# BaseBoard5.net
KiCad netlist of a schematic drawn in EAGLE
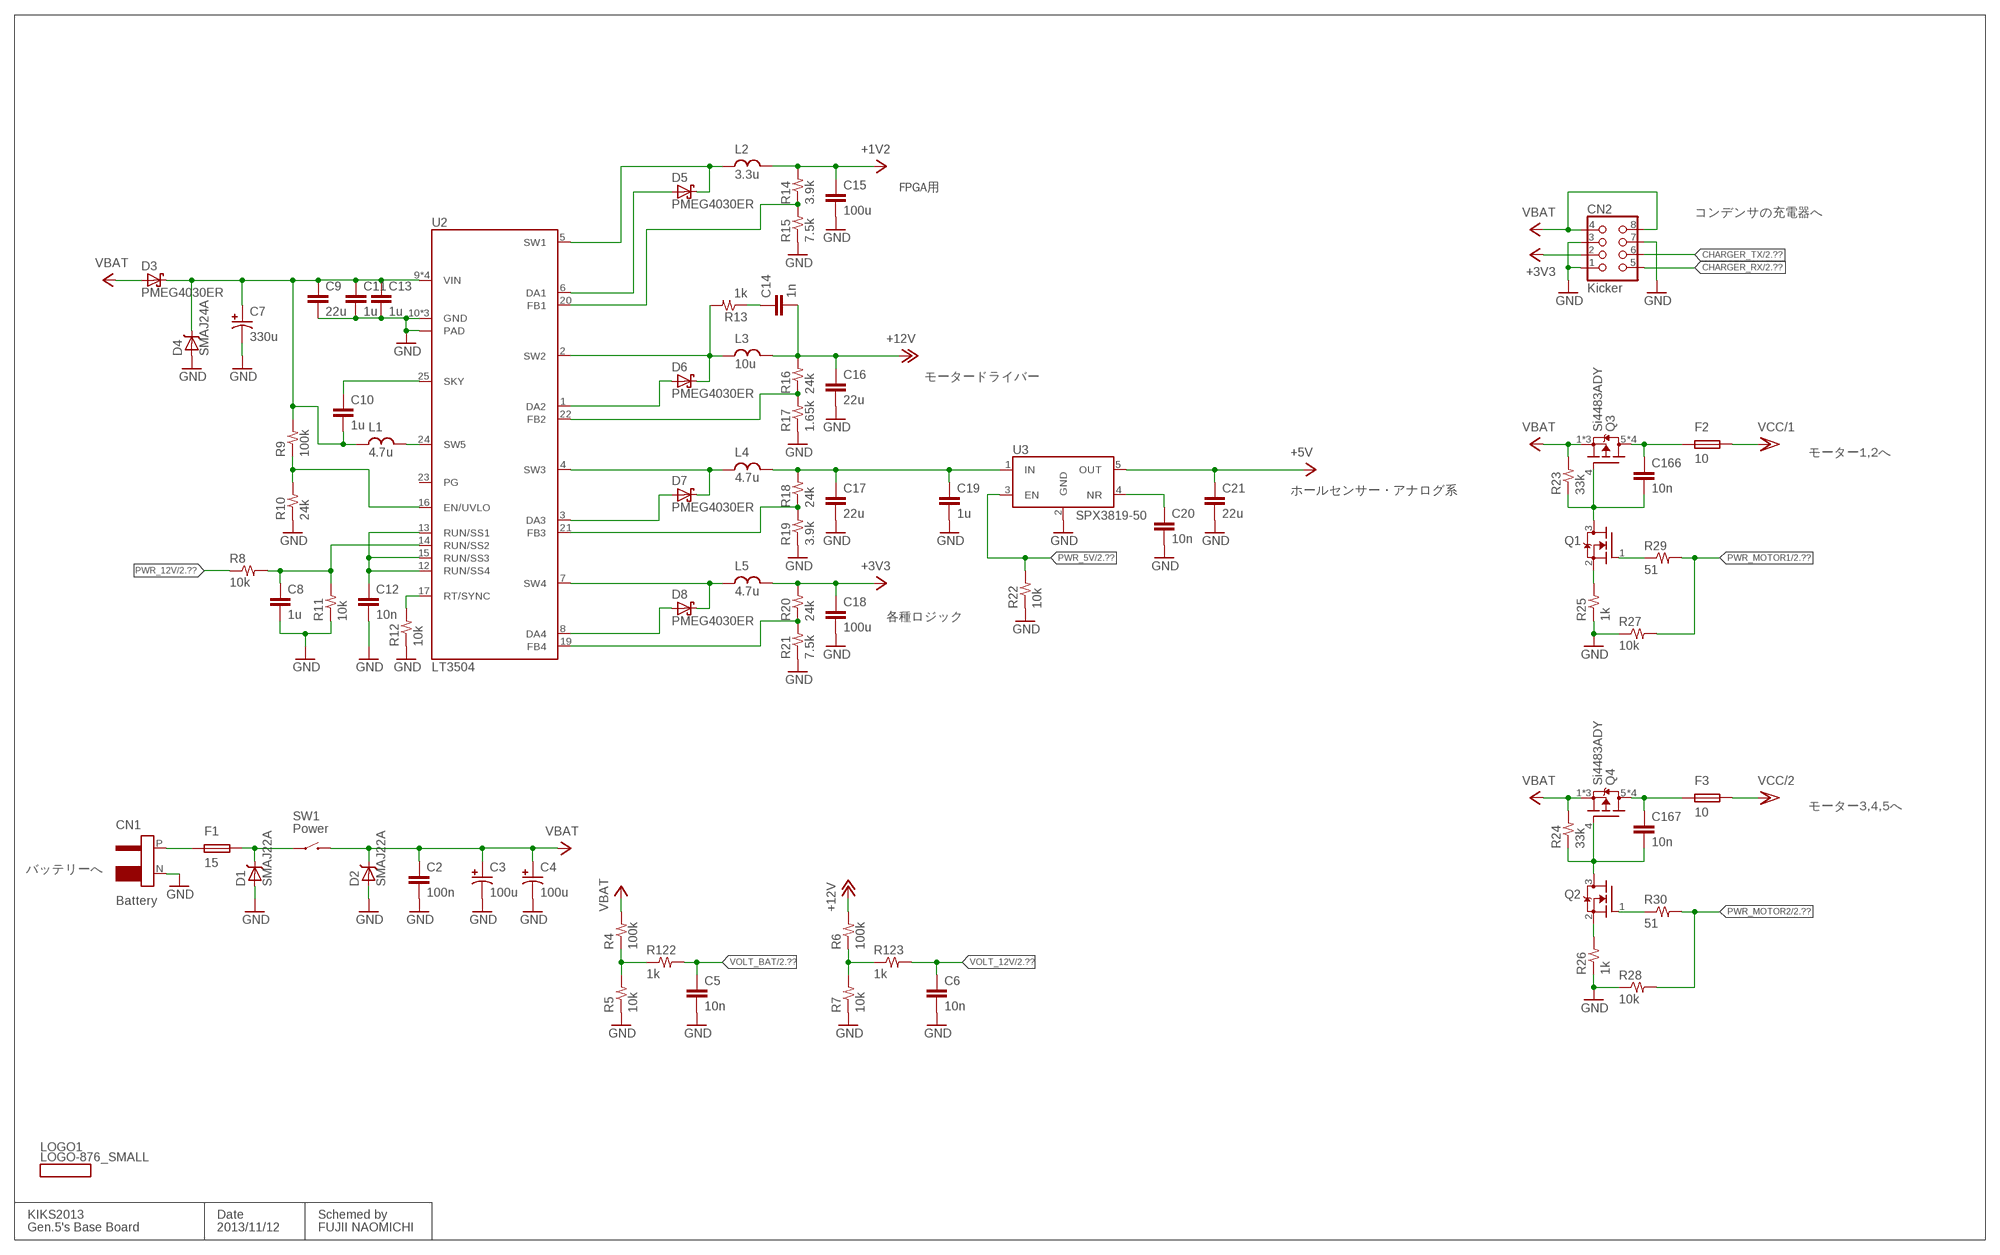
[diagram p0: schematic, sheet 1]
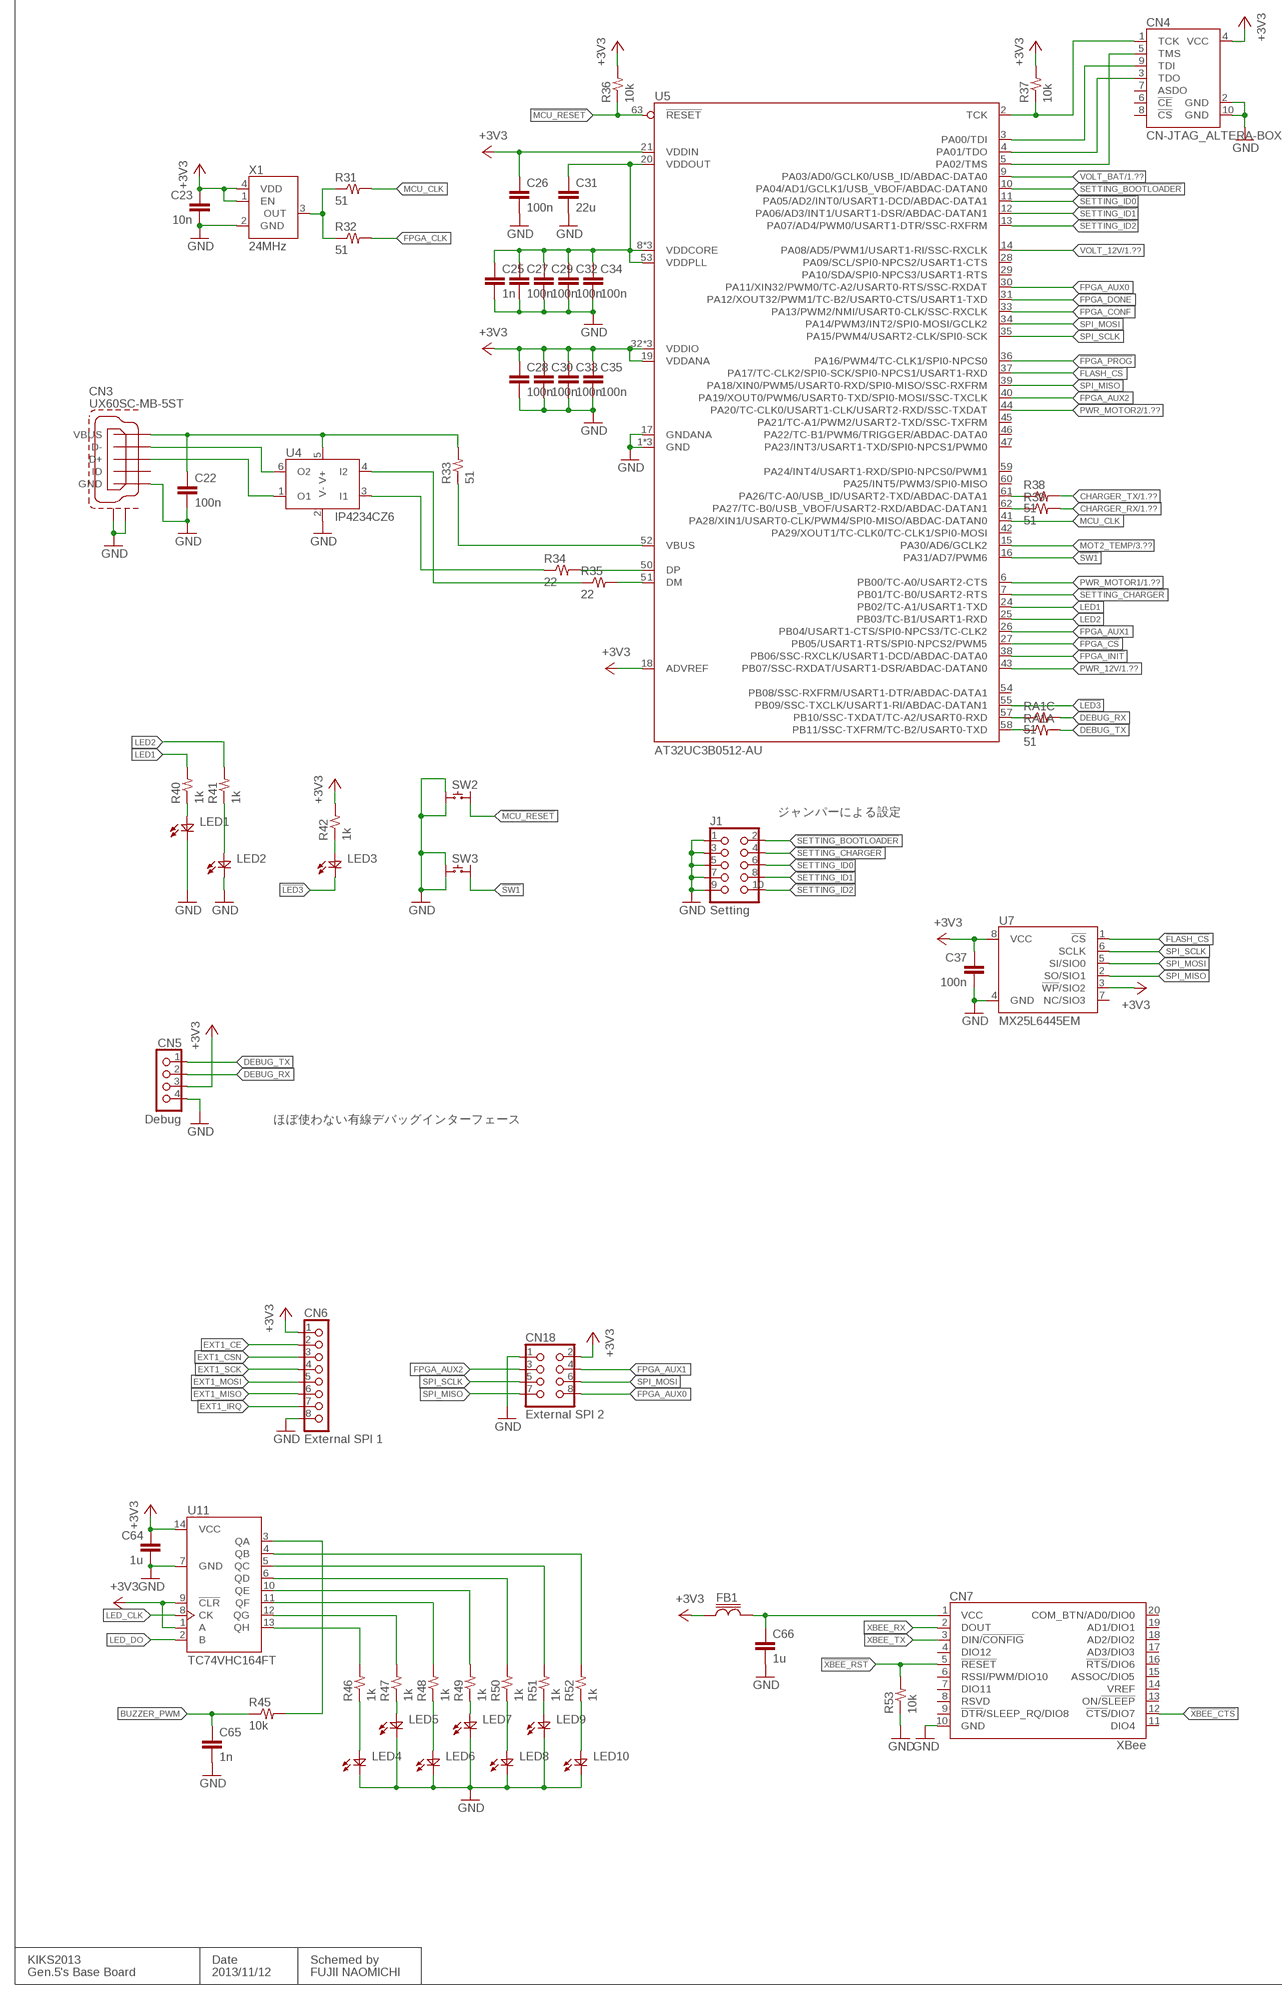
[diagram p1: schematic, sheet 2, part 1 of 2]
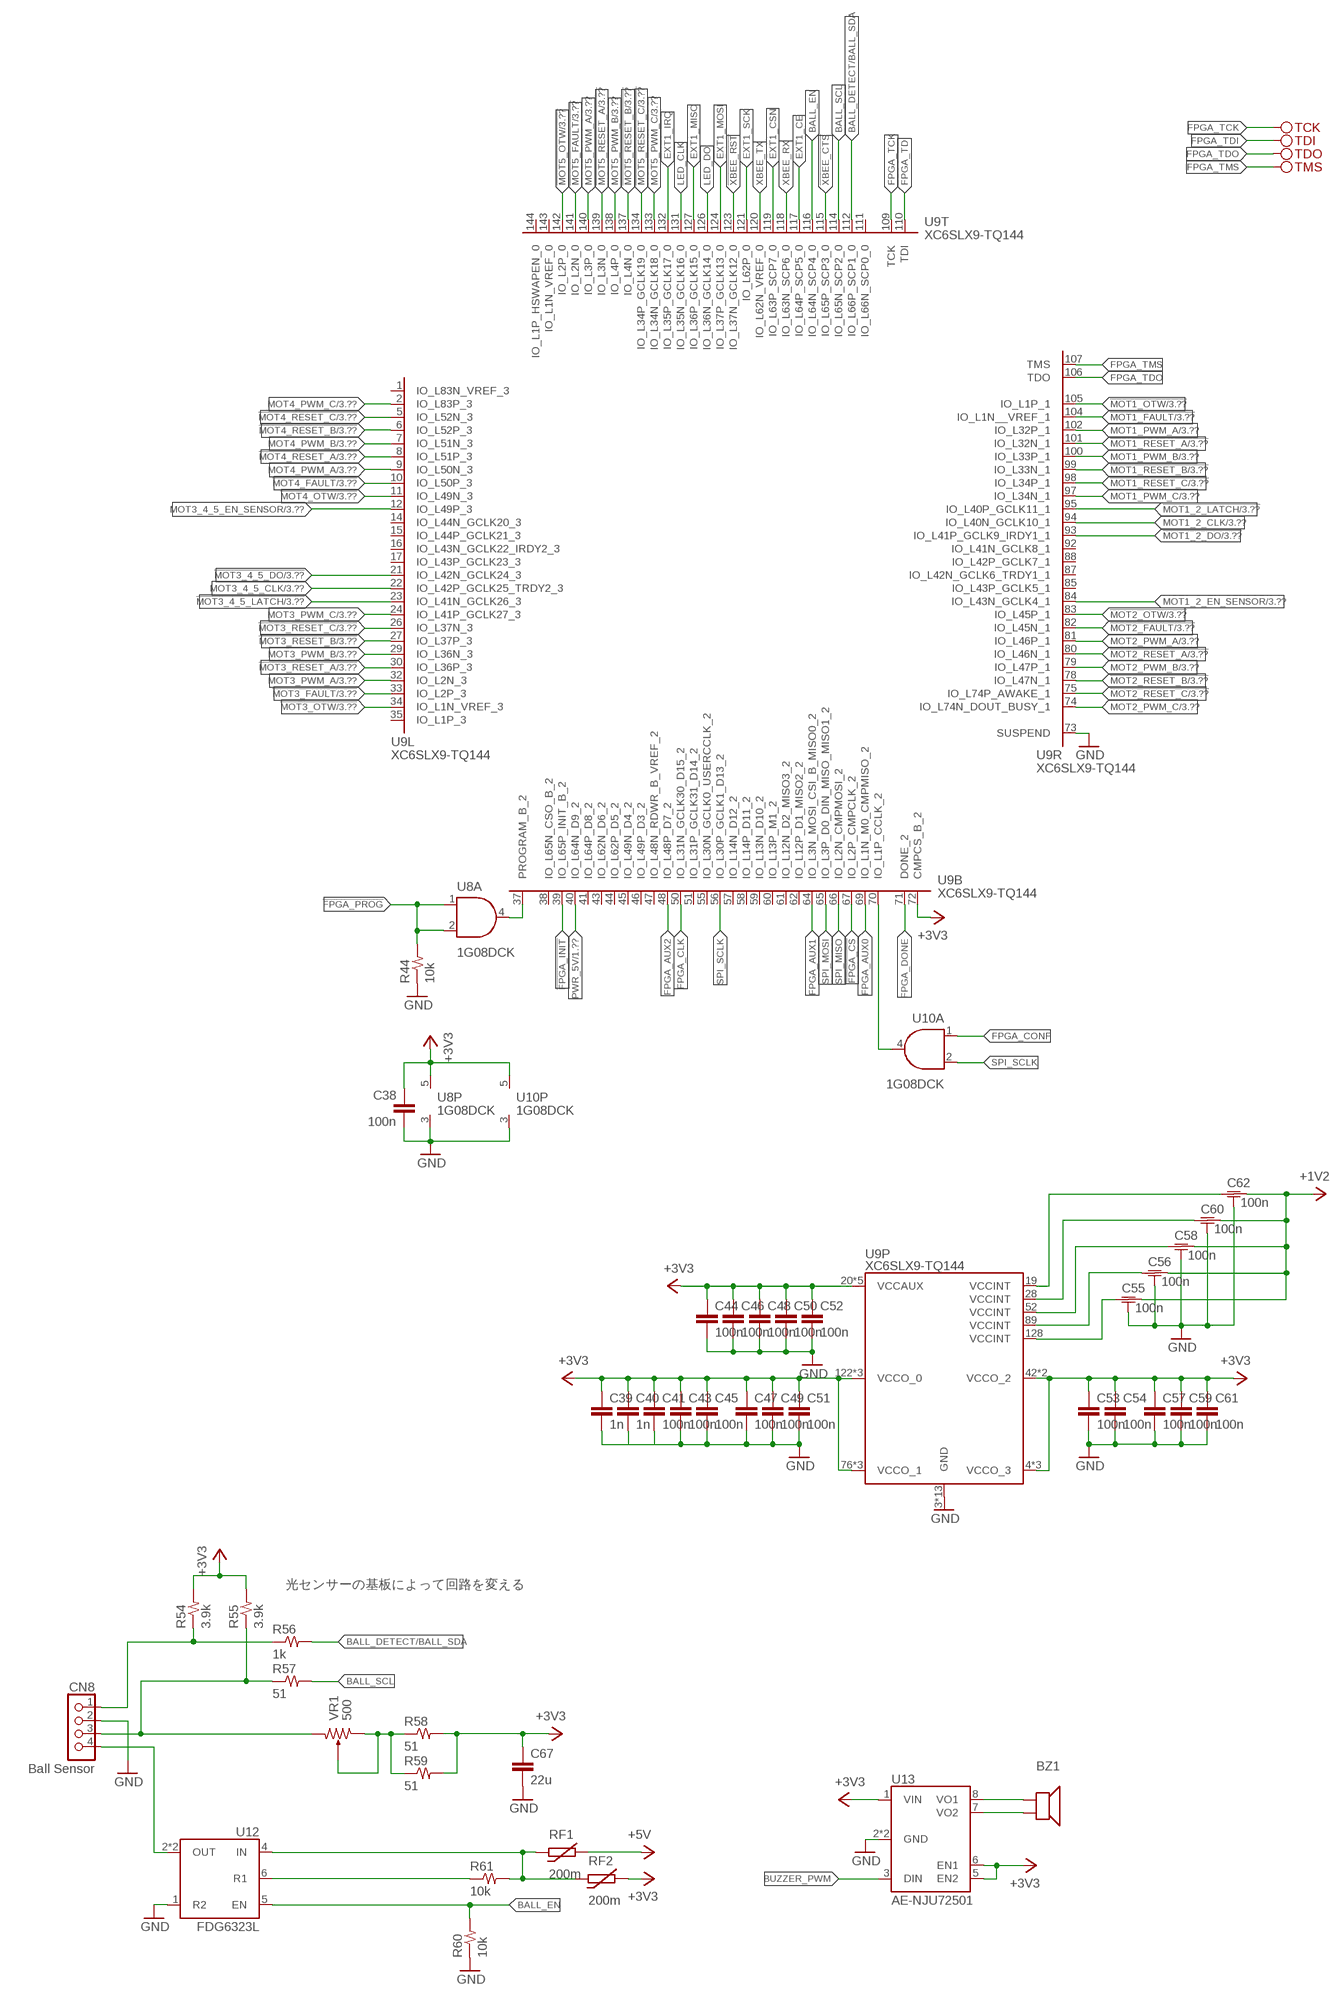
[diagram p2: schematic, sheet 2, part 2 of 2]
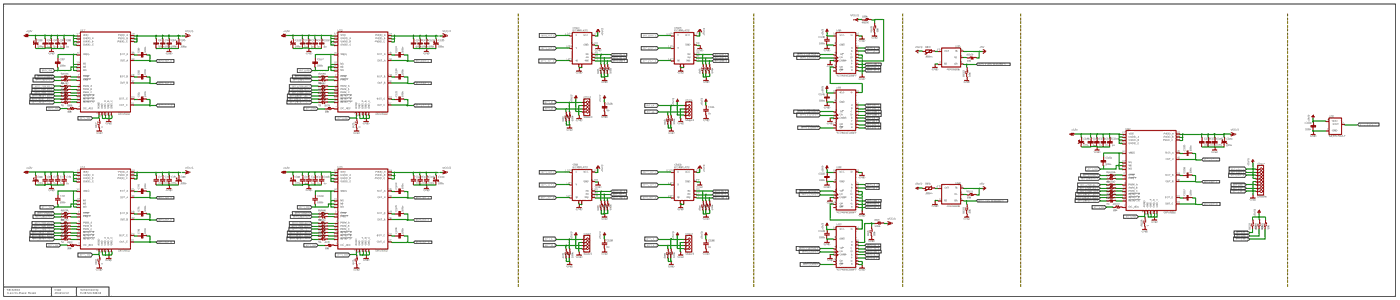
[diagram p3: schematic, sheet 3, overview]
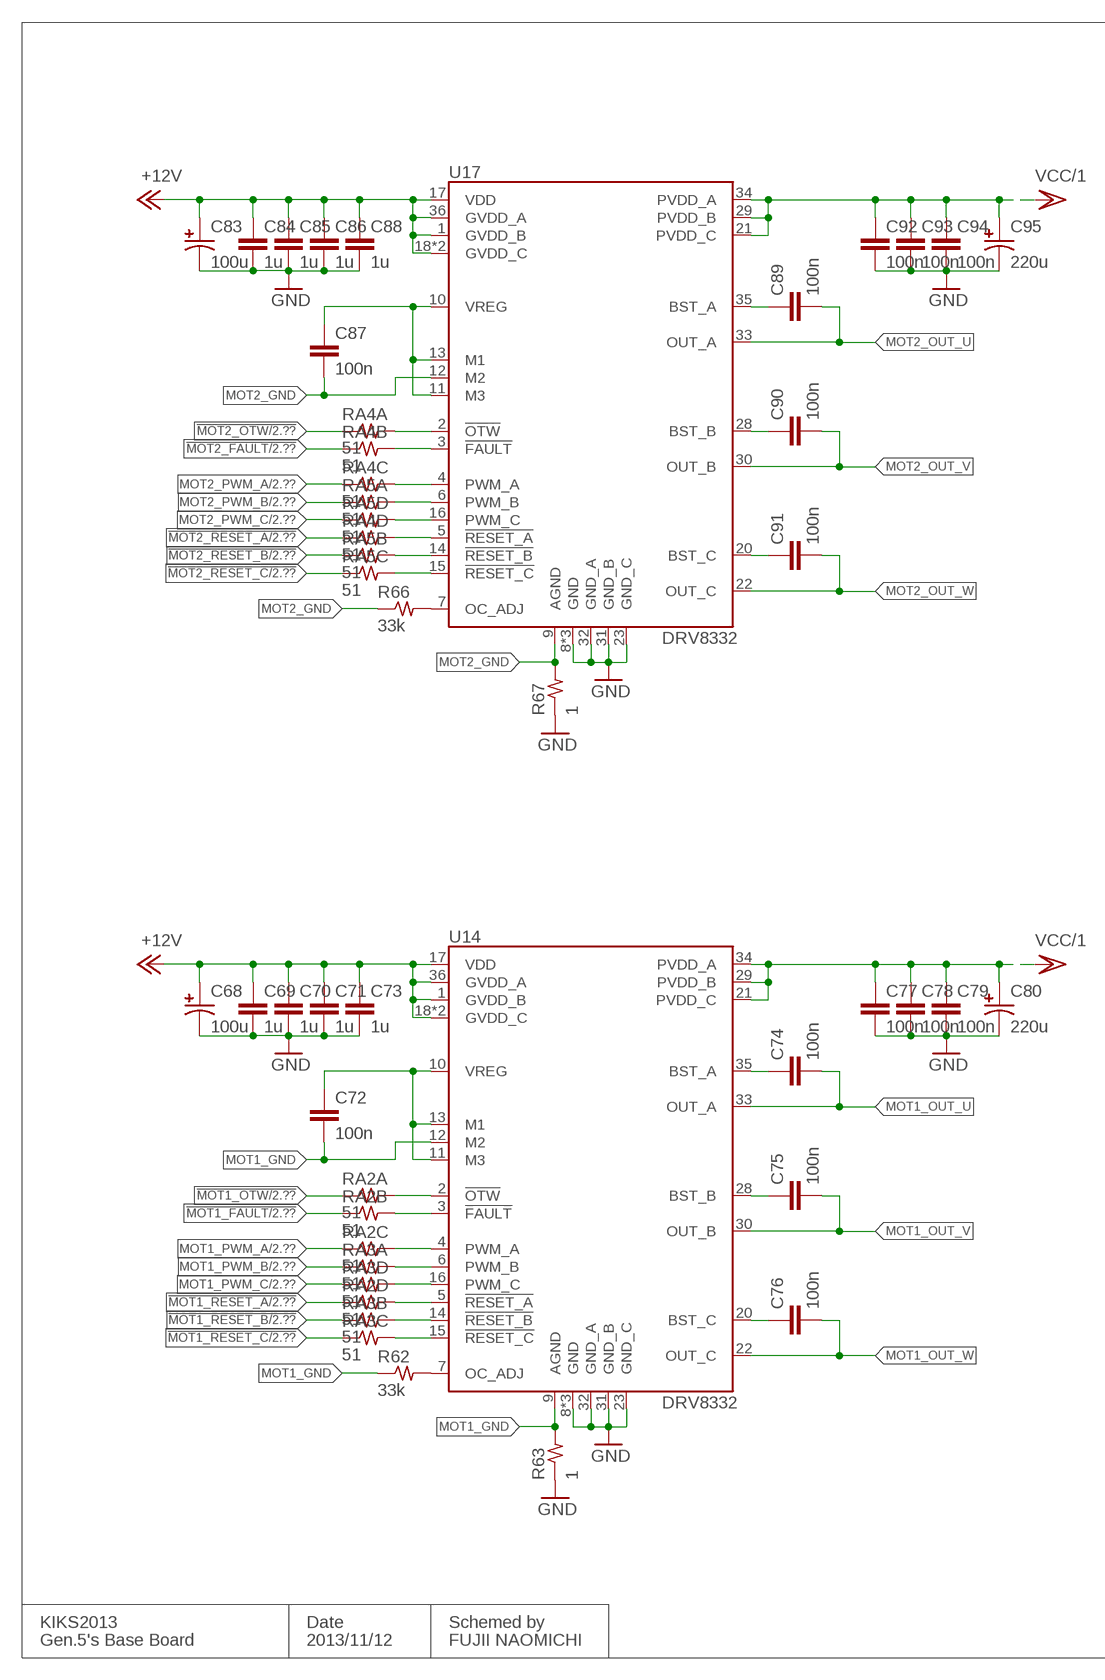
[diagram p4: schematic, sheet 3, part 1 of 4]
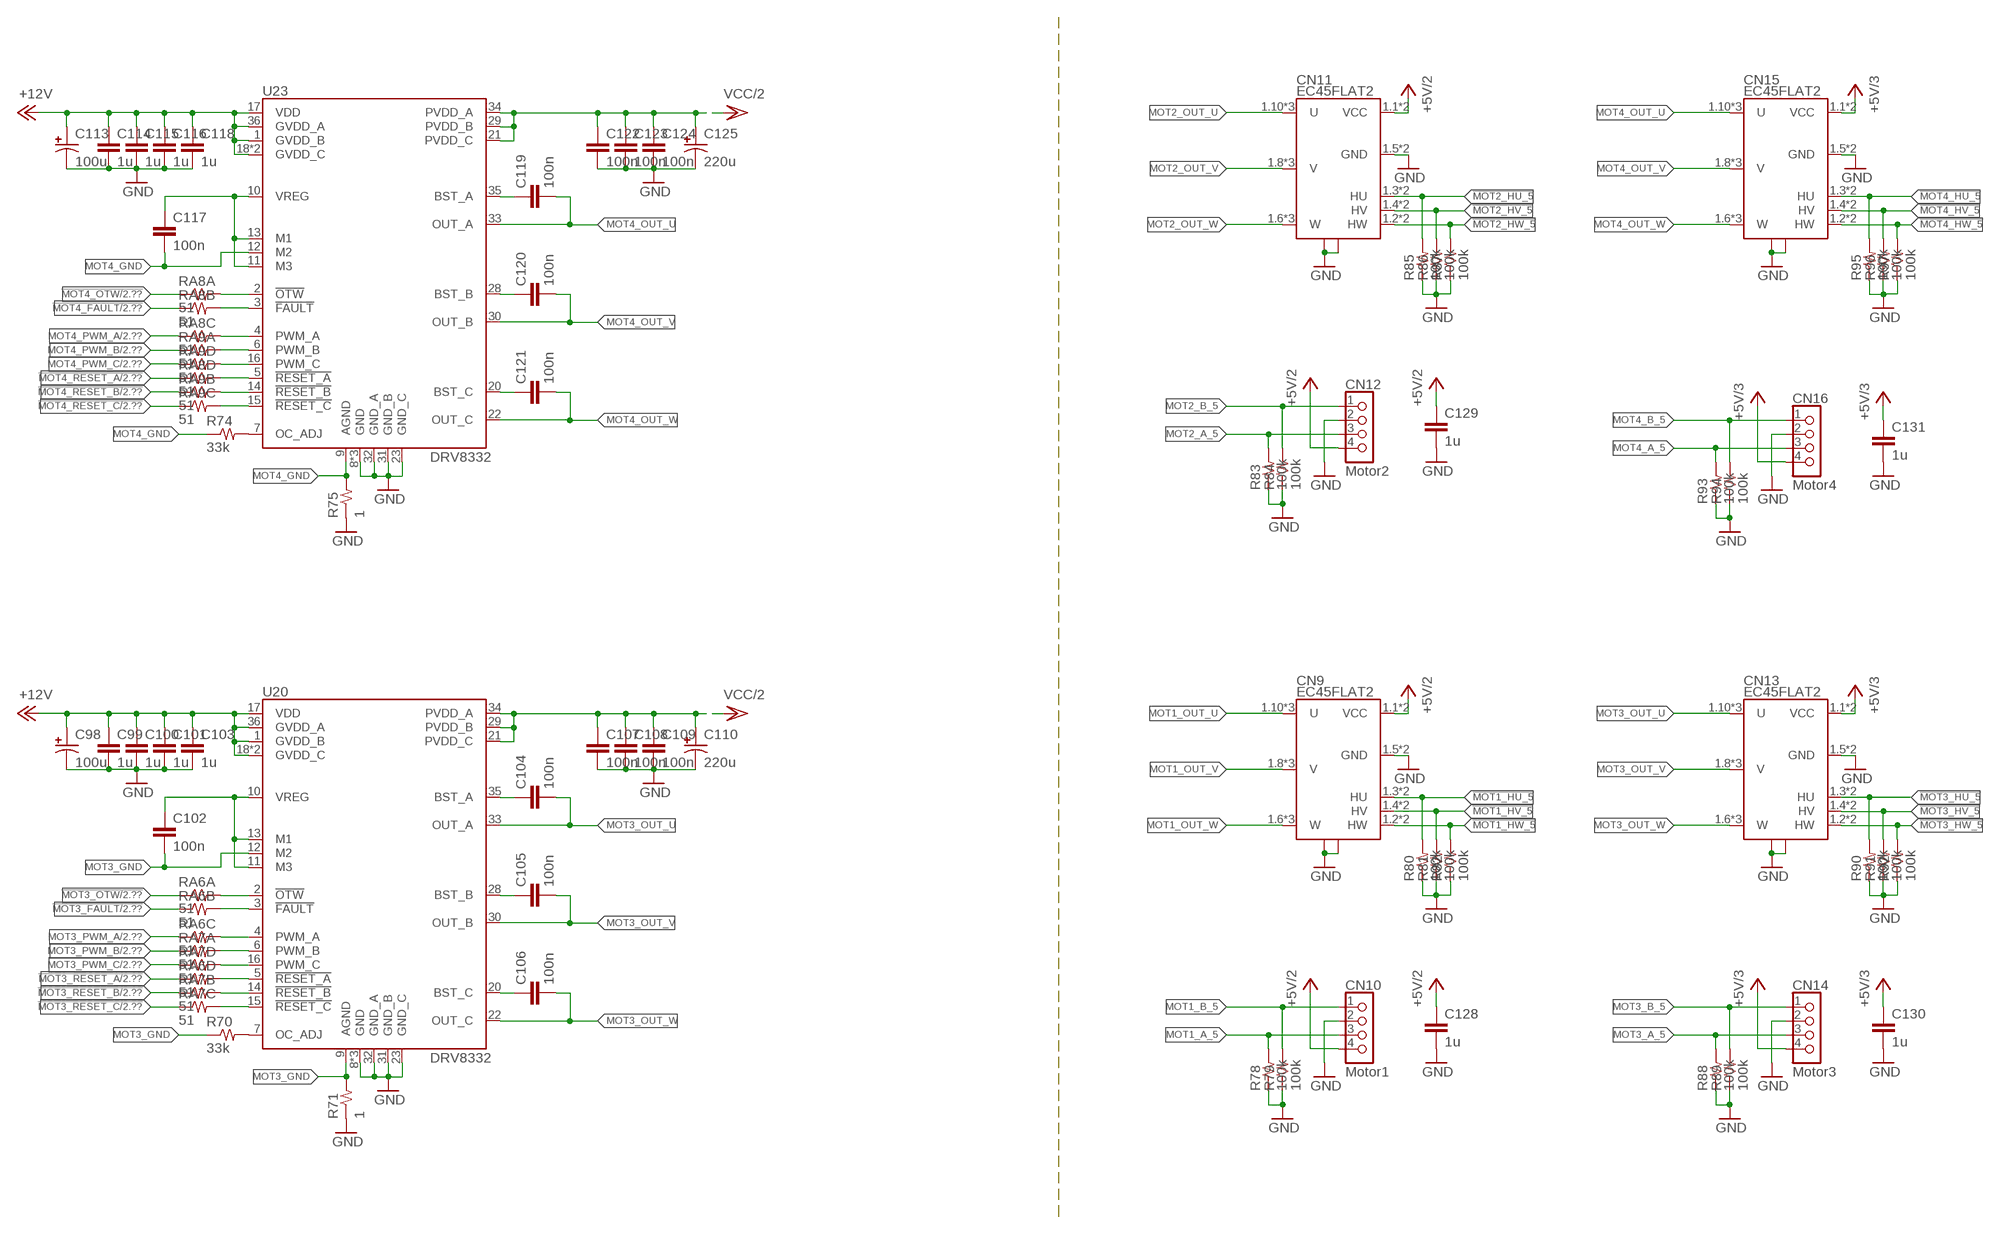
[diagram p5: schematic, sheet 3, part 2 of 4]
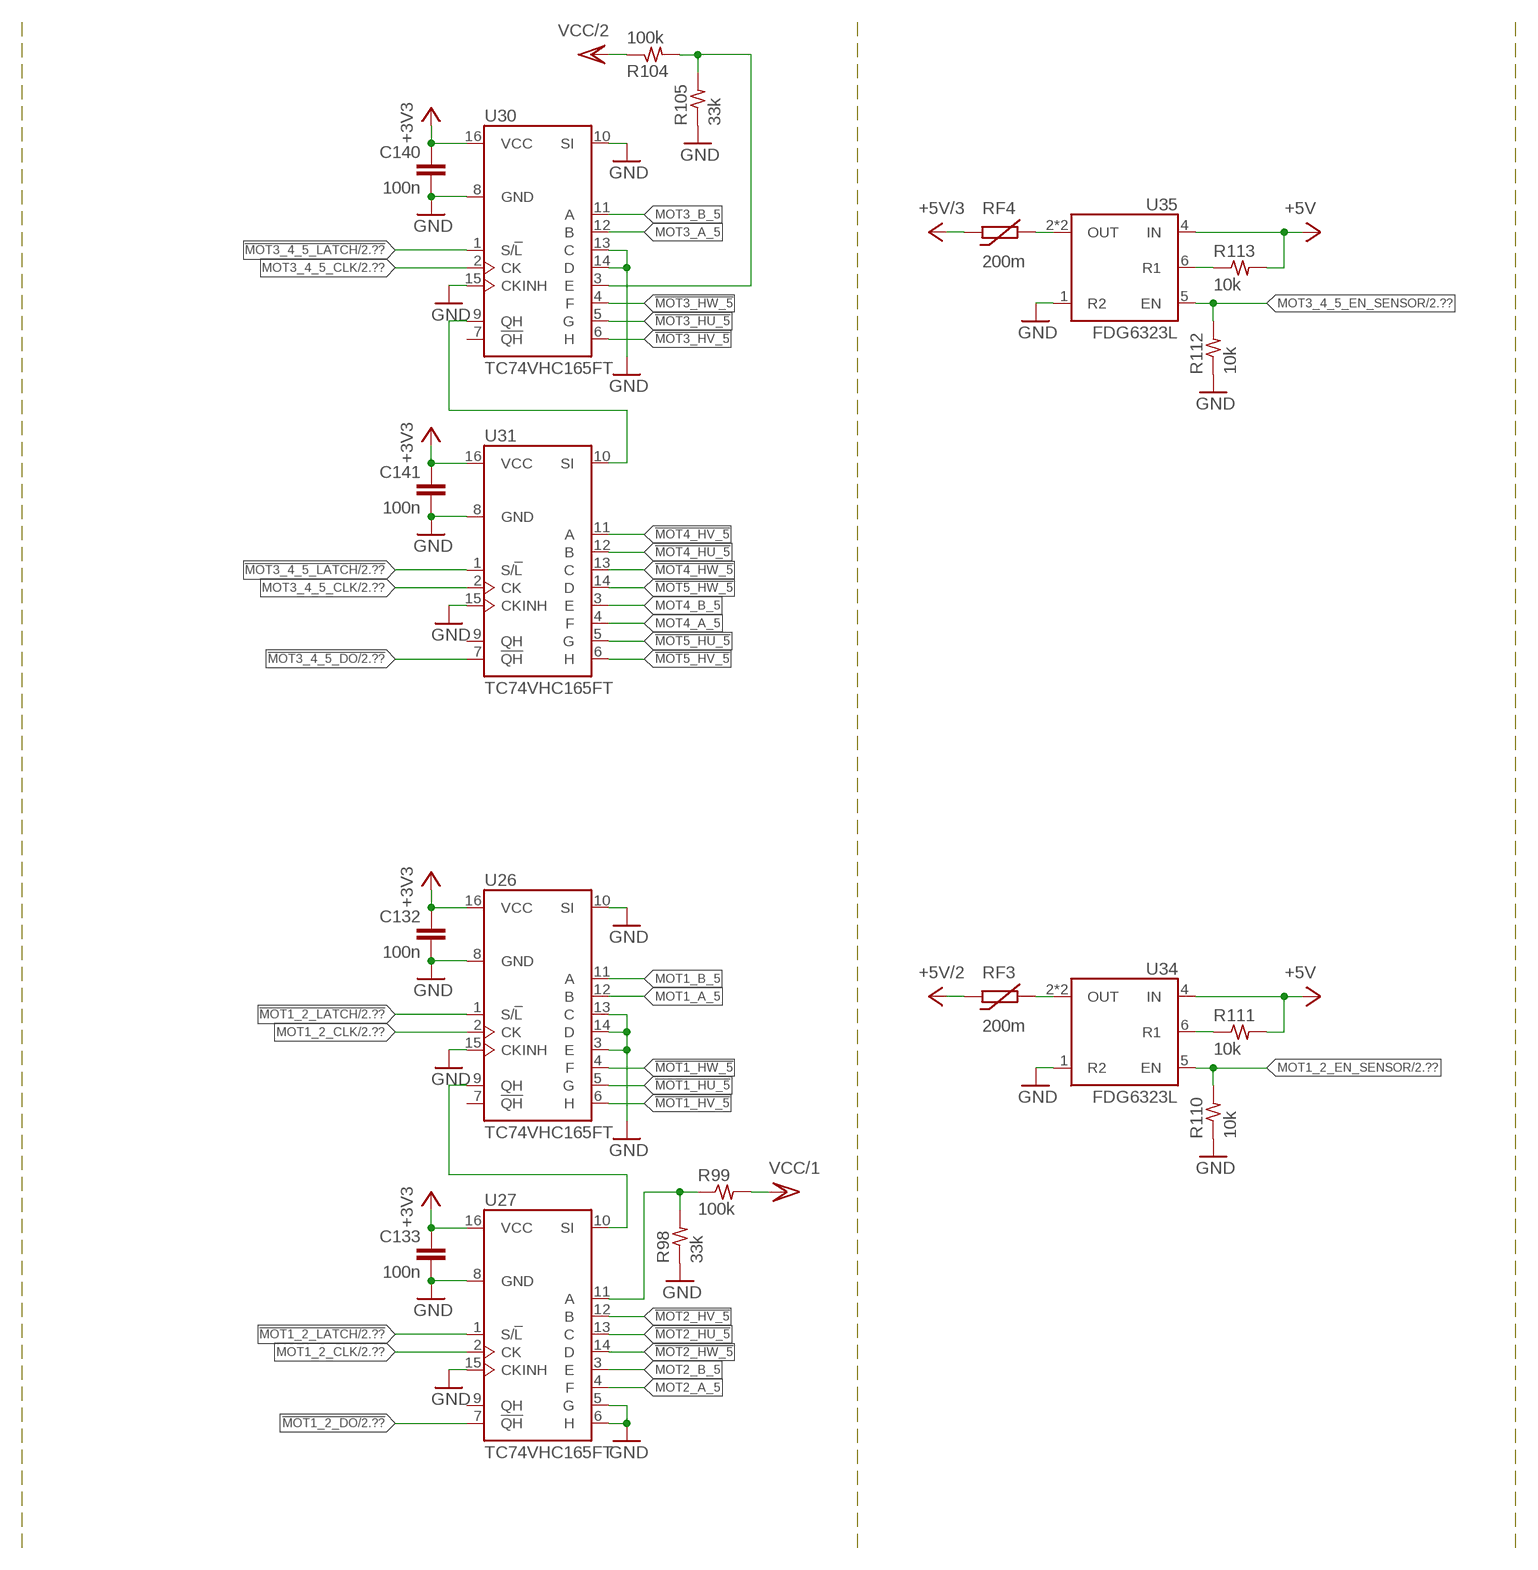
[diagram p6: schematic, sheet 3, part 3 of 4]
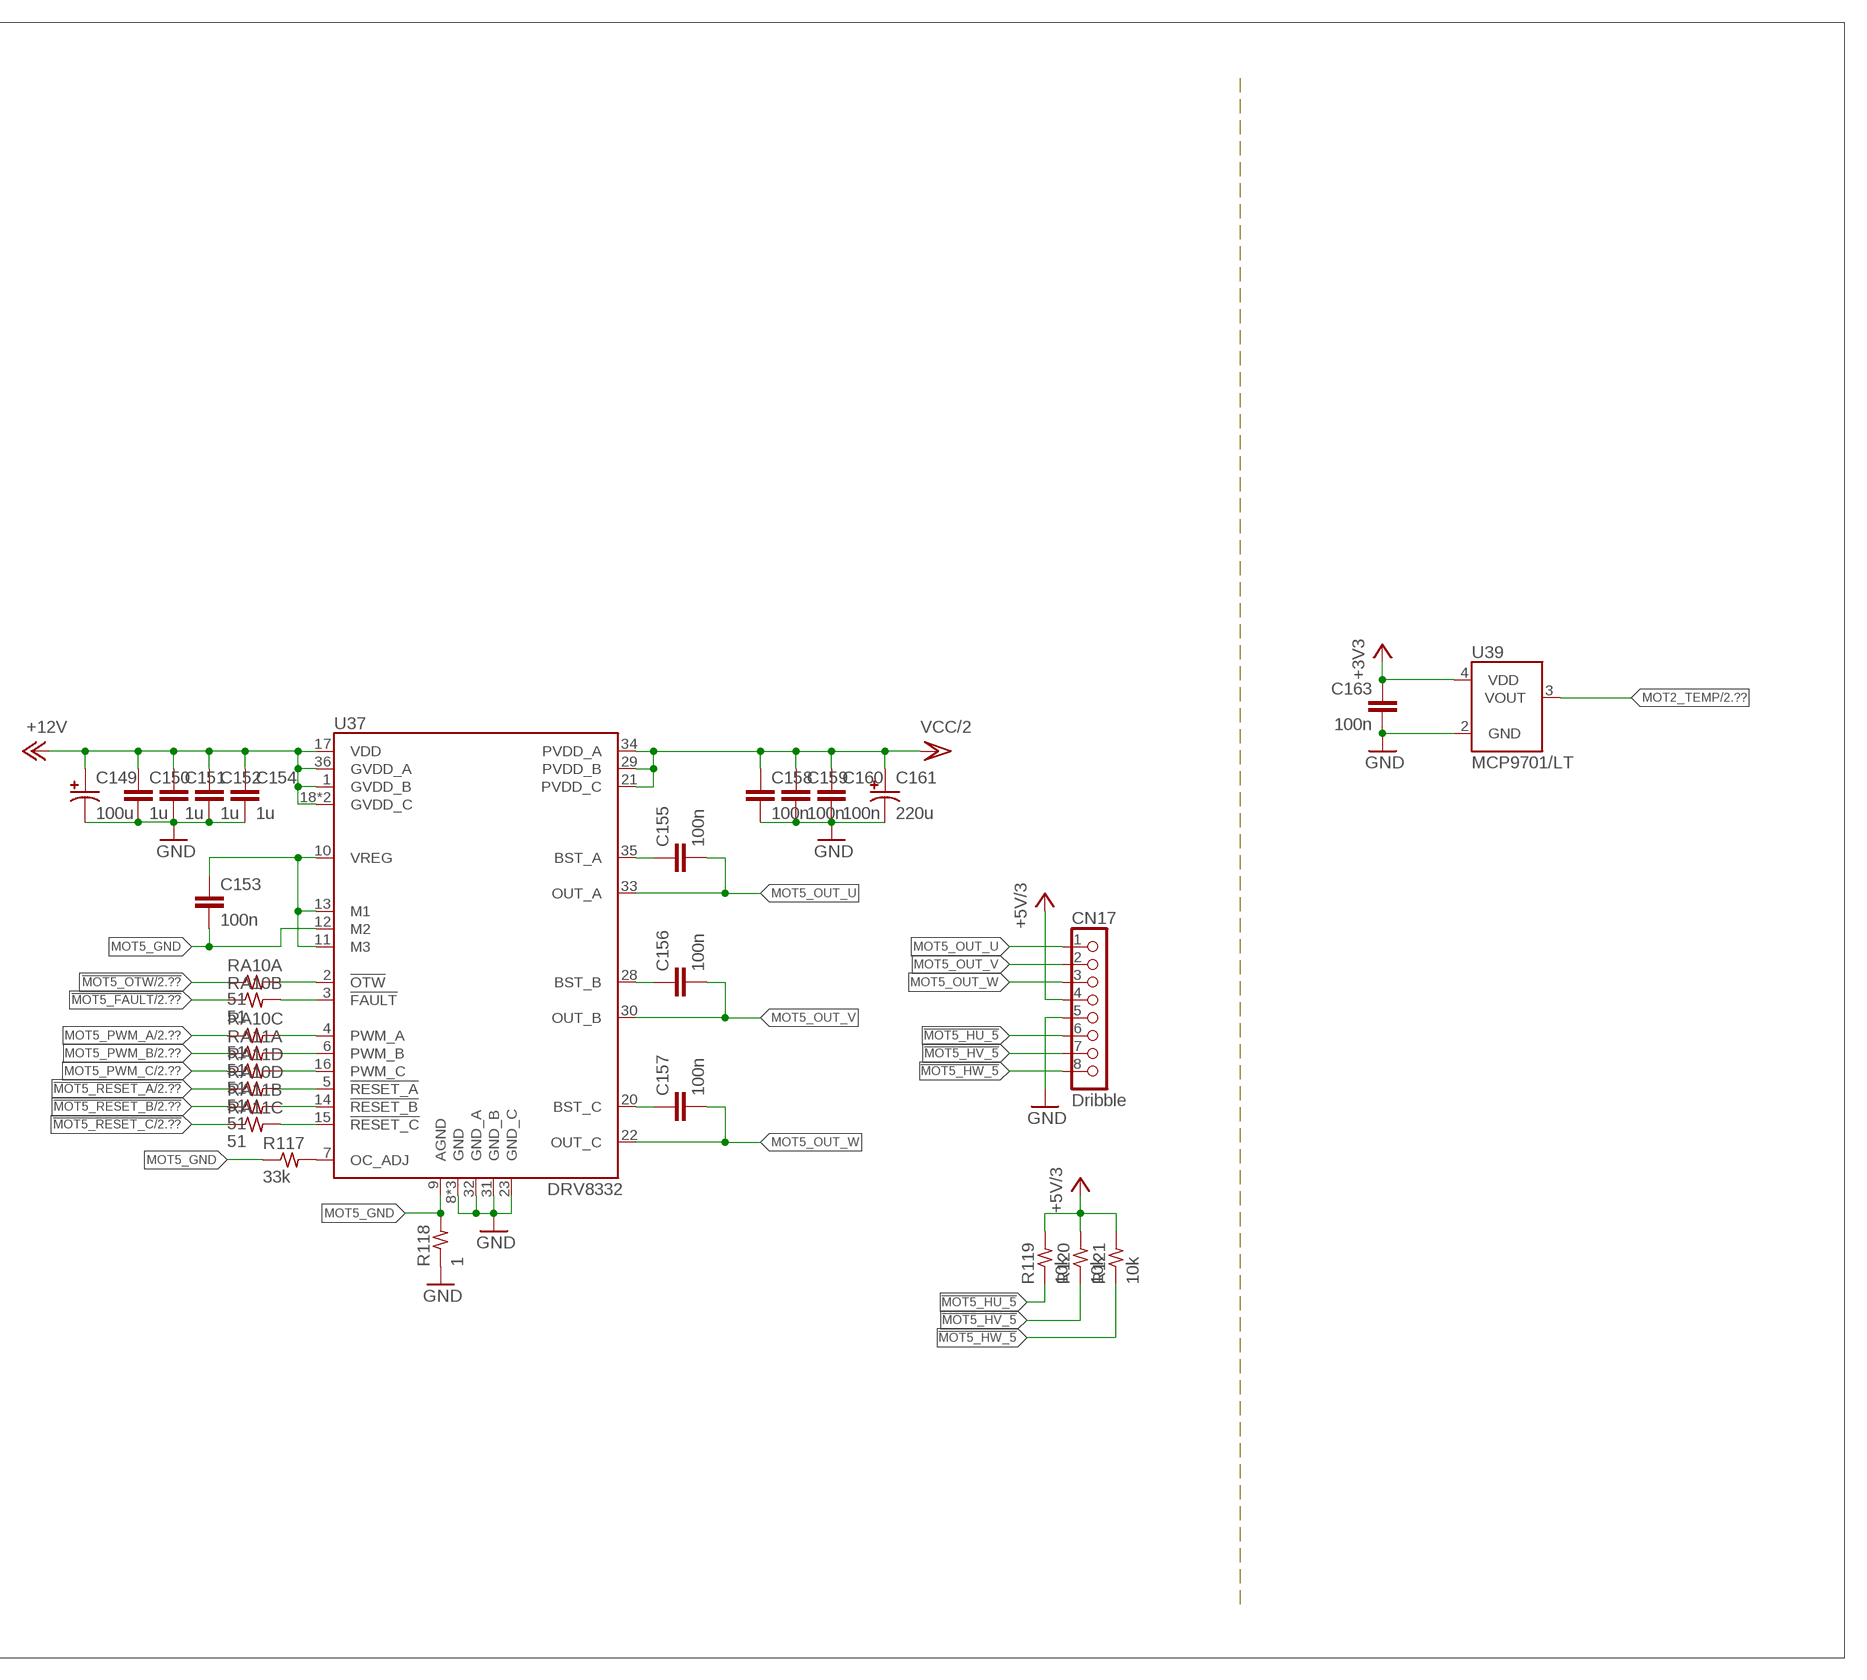
[diagram p7: schematic, sheet 3, part 4 of 4]

(export (version "E")
  (design (tool "Eeschema 10.0.6"))
  (components
    (comp (ref "BZ1")
      (value "PKLCS1212E4001")
      (footprint "eagle-import:PKLCS1212")
      (libsource (lib "eagle-import") (part "PKLCS1212E4001"))
    )
    (comp (ref "C22")
      (value "100n")
      (footprint "eagle-import:1005")
      (libsource (lib "eagle-import") (part "C1005"))
    )
    (comp (ref "C23")
      (value "10n")
      (footprint "eagle-import:1005")
      (libsource (lib "eagle-import") (part "C1005"))
    )
    (comp (ref "C25")
      (value "1n")
      (footprint "eagle-import:1005")
      (libsource (lib "eagle-import") (part "C1005"))
    )
    (comp (ref "C26")
      (value "100n")
      (footprint "eagle-import:1005")
      (libsource (lib "eagle-import") (part "C1005"))
    )
    (comp (ref "C27")
      (value "100n")
      (footprint "eagle-import:1005")
      (libsource (lib "eagle-import") (part "C1005"))
    )
    (comp (ref "C28")
      (value "100n")
      (footprint "eagle-import:1005")
      (libsource (lib "eagle-import") (part "C1005"))
    )
    (comp (ref "C29")
      (value "100n")
      (footprint "eagle-import:1005")
      (libsource (lib "eagle-import") (part "C1005"))
    )
    (comp (ref "C30")
      (value "100n")
      (footprint "eagle-import:1005")
      (libsource (lib "eagle-import") (part "C1005"))
    )
    (comp (ref "C31")
      (value "22u")
      (footprint "eagle-import:2012")
      (libsource (lib "eagle-import") (part "C2012"))
    )
    (comp (ref "C32")
      (value "100n")
      (footprint "eagle-import:1005")
      (libsource (lib "eagle-import") (part "C1005"))
    )
    (comp (ref "C33")
      (value "100n")
      (footprint "eagle-import:1005")
      (libsource (lib "eagle-import") (part "C1005"))
    )
    (comp (ref "C34")
      (value "100n")
      (footprint "eagle-import:1005")
      (libsource (lib "eagle-import") (part "C1005"))
    )
    (comp (ref "C35")
      (value "100n")
      (footprint "eagle-import:1005")
      (libsource (lib "eagle-import") (part "C1005"))
    )
    (comp (ref "C37")
      (value "100n")
      (footprint "eagle-import:1005")
      (libsource (lib "eagle-import") (part "C1005"))
    )
    (comp (ref "C38")
      (value "100n")
      (footprint "eagle-import:1005")
      (libsource (lib "eagle-import") (part "C1005"))
    )
    (comp (ref "C39")
      (value "1n")
      (footprint "eagle-import:1005")
      (libsource (lib "eagle-import") (part "C1005"))
    )
    (comp (ref "C40")
      (value "1n")
      (footprint "eagle-import:1005")
      (libsource (lib "eagle-import") (part "C1005"))
    )
    (comp (ref "C41")
      (value "100n")
      (footprint "eagle-import:1005")
      (libsource (lib "eagle-import") (part "C1005"))
    )
    (comp (ref "C43")
      (value "100n")
      (footprint "eagle-import:1005")
      (libsource (lib "eagle-import") (part "C1005"))
    )
    (comp (ref "C44")
      (value "100n")
      (footprint "eagle-import:1005")
      (libsource (lib "eagle-import") (part "C1005"))
    )
    (comp (ref "C45")
      (value "100n")
      (footprint "eagle-import:1005")
      (libsource (lib "eagle-import") (part "C1005"))
    )
    (comp (ref "C46")
      (value "100n")
      (footprint "eagle-import:1005")
      (libsource (lib "eagle-import") (part "C1005"))
    )
    (comp (ref "C47")
      (value "100n")
      (footprint "eagle-import:1005")
      (libsource (lib "eagle-import") (part "C1005"))
    )
    (comp (ref "C48")
      (value "100n")
      (footprint "eagle-import:1005")
      (libsource (lib "eagle-import") (part "C1005"))
    )
    (comp (ref "C49")
      (value "100n")
      (footprint "eagle-import:1005")
      (libsource (lib "eagle-import") (part "C1005"))
    )
    (comp (ref "C50")
      (value "100n")
      (footprint "eagle-import:1005")
      (libsource (lib "eagle-import") (part "C1005"))
    )
    (comp (ref "C51")
      (value "100n")
      (footprint "eagle-import:1005")
      (libsource (lib "eagle-import") (part "C1005"))
    )
    (comp (ref "C52")
      (value "100n")
      (footprint "eagle-import:1005")
      (libsource (lib "eagle-import") (part "C1005"))
    )
    (comp (ref "C53")
      (value "100n")
      (footprint "eagle-import:1005")
      (libsource (lib "eagle-import") (part "C1005"))
    )
    (comp (ref "C54")
      (value "100n")
      (footprint "eagle-import:1005")
      (libsource (lib "eagle-import") (part "C1005"))
    )
    (comp (ref "C55")
      (value "100n")
      (footprint "eagle-import:NFM18")
      (libsource (lib "eagle-import") (part "CT1608"))
    )
    (comp (ref "C56")
      (value "100n")
      (footprint "eagle-import:NFM18")
      (libsource (lib "eagle-import") (part "CT1608"))
    )
    (comp (ref "C57")
      (value "100n")
      (footprint "eagle-import:1005")
      (libsource (lib "eagle-import") (part "C1005"))
    )
    (comp (ref "C58")
      (value "100n")
      (footprint "eagle-import:NFM18")
      (libsource (lib "eagle-import") (part "CT1608"))
    )
    (comp (ref "C59")
      (value "100n")
      (footprint "eagle-import:1005")
      (libsource (lib "eagle-import") (part "C1005"))
    )
    (comp (ref "C60")
      (value "100n")
      (footprint "eagle-import:NFM18")
      (libsource (lib "eagle-import") (part "CT1608"))
    )
    (comp (ref "C61")
      (value "100n")
      (footprint "eagle-import:1005")
      (libsource (lib "eagle-import") (part "C1005"))
    )
    (comp (ref "C62")
      (value "100n")
      (footprint "eagle-import:NFM18")
      (libsource (lib "eagle-import") (part "CT1608"))
    )
    (comp (ref "C64")
      (value "1u")
      (footprint "eagle-import:1005")
      (libsource (lib "eagle-import") (part "C1005"))
    )
    (comp (ref "C65")
      (value "1n")
      (footprint "eagle-import:1005")
      (libsource (lib "eagle-import") (part "C1005"))
    )
    (comp (ref "C66")
      (value "1u")
      (footprint "eagle-import:1608")
      (libsource (lib "eagle-import") (part "C1608"))
    )
    (comp (ref "C67")
      (value "22u")
      (footprint "eagle-import:2012")
      (libsource (lib "eagle-import") (part "C2012"))
    )
    (comp (ref "CN3")
      (value "UX60SC-MB-5ST")
      (footprint "eagle-import:UX60SC-MB-5ST")
      (libsource (lib "eagle-import") (part "UX60SC-MB-5ST"))
    )
    (comp (ref "CN4")
      (value "CN-JTAG_ALTERA-BOX")
      (footprint "eagle-import:PIN2X5-BOX")
      (libsource (lib "eagle-import") (part "CN-JTAG_ALTERA-BOX"))
    )
    (comp (ref "CN5")
      (value "Debug")
      (footprint "eagle-import:70553-0003")
      (libsource (lib "eagle-import") (part "70553-0003"))
    )
    (comp (ref "CN6")
      (value "External SPI 1")
      (footprint "eagle-import:PIN1X8")
      (libsource (lib "eagle-import") (part "PIN1X8"))
    )
    (comp (ref "CN7")
      (value "XBee")
      (footprint "eagle-import:XBEE-TH")
      (libsource (lib "eagle-import") (part "XBEE-TH"))
    )
    (comp (ref "CN8")
      (value "Ball Sensor")
      (footprint "eagle-import:53375-04")
      (libsource (lib "eagle-import") (part "53375-0410"))
    )
    (comp (ref "CN18")
      (value "External SPI 2")
      (footprint "eagle-import:PIN2X4")
      (libsource (lib "eagle-import") (part "PIN2X4"))
    )
    (comp (ref "FB1")
      (value "FB1608")
      (footprint "eagle-import:1608")
      (libsource (lib "eagle-import") (part "FB1608"))
    )
    (comp (ref "J1")
      (value "Setting")
      (footprint "eagle-import:PIN2X5-2.0")
      (libsource (lib "eagle-import") (part "PIN2X5-2.0"))
    )
    (comp (ref "LED1")
      (value "LED1608")
      (footprint "eagle-import:1608")
      (libsource (lib "eagle-import") (part "LED1608"))
    )
    (comp (ref "LED2")
      (value "LED1608")
      (footprint "eagle-import:1608")
      (libsource (lib "eagle-import") (part "LED1608"))
    )
    (comp (ref "LED3")
      (value "LED1608")
      (footprint "eagle-import:1608")
      (libsource (lib "eagle-import") (part "LED1608"))
    )
    (comp (ref "LED4")
      (value "LED1608")
      (footprint "eagle-import:1608")
      (libsource (lib "eagle-import") (part "LED1608"))
    )
    (comp (ref "LED5")
      (value "LED1608")
      (footprint "eagle-import:1608")
      (libsource (lib "eagle-import") (part "LED1608"))
    )
    (comp (ref "LED6")
      (value "LED1608")
      (footprint "eagle-import:1608")
      (libsource (lib "eagle-import") (part "LED1608"))
    )
    (comp (ref "LED7")
      (value "LED1608")
      (footprint "eagle-import:1608")
      (libsource (lib "eagle-import") (part "LED1608"))
    )
    (comp (ref "LED8")
      (value "LED1608")
      (footprint "eagle-import:1608")
      (libsource (lib "eagle-import") (part "LED1608"))
    )
    (comp (ref "LED9")
      (value "LED1608")
      (footprint "eagle-import:1608")
      (libsource (lib "eagle-import") (part "LED1608"))
    )
    (comp (ref "LED10")
      (value "LED1608")
      (footprint "eagle-import:1608")
      (libsource (lib "eagle-import") (part "LED1608"))
    )
    (comp (ref "P1")
      (value "TCK")
      (footprint "eagle-import:PAD")
      (libsource (lib "eagle-import") (part "PAD"))
    )
    (comp (ref "P2")
      (value "TDI")
      (footprint "eagle-import:PAD")
      (libsource (lib "eagle-import") (part "PAD"))
    )
    (comp (ref "P3")
      (value "TDO")
      (footprint "eagle-import:PAD")
      (libsource (lib "eagle-import") (part "PAD"))
    )
    (comp (ref "P4")
      (value "TMS")
      (footprint "eagle-import:PAD")
      (libsource (lib "eagle-import") (part "PAD"))
    )
    (comp (ref "R31")
      (value "51")
      (footprint "eagle-import:1005")
      (libsource (lib "eagle-import") (part "R1005"))
    )
    (comp (ref "R32")
      (value "51")
      (footprint "eagle-import:1005")
      (libsource (lib "eagle-import") (part "R1005"))
    )
    (comp (ref "R33")
      (value "51")
      (footprint "eagle-import:1005")
      (libsource (lib "eagle-import") (part "R1005"))
    )
    (comp (ref "R34")
      (value "22")
      (footprint "eagle-import:1005")
      (libsource (lib "eagle-import") (part "R1005"))
    )
    (comp (ref "R35")
      (value "22")
      (footprint "eagle-import:1005")
      (libsource (lib "eagle-import") (part "R1005"))
    )
    (comp (ref "R36")
      (value "10k")
      (footprint "eagle-import:1005")
      (libsource (lib "eagle-import") (part "R1005"))
    )
    (comp (ref "R37")
      (value "10k")
      (footprint "eagle-import:1005")
      (libsource (lib "eagle-import") (part "R1005"))
    )
    (comp (ref "R38")
      (value "51")
      (footprint "eagle-import:1005")
      (libsource (lib "eagle-import") (part "R1005"))
    )
    (comp (ref "R39")
      (value "51")
      (footprint "eagle-import:1005")
      (libsource (lib "eagle-import") (part "R1005"))
    )
    (comp (ref "R40")
      (value "1k")
      (footprint "eagle-import:1005")
      (libsource (lib "eagle-import") (part "R1005"))
    )
    (comp (ref "R41")
      (value "1k")
      (footprint "eagle-import:1005")
      (libsource (lib "eagle-import") (part "R1005"))
    )
    (comp (ref "R42")
      (value "1k")
      (footprint "eagle-import:1005")
      (libsource (lib "eagle-import") (part "R1005"))
    )
    (comp (ref "R44")
      (value "10k")
      (footprint "eagle-import:1005")
      (libsource (lib "eagle-import") (part "R1005"))
    )
    (comp (ref "R45")
      (value "10k")
      (footprint "eagle-import:1005")
      (libsource (lib "eagle-import") (part "R1005"))
    )
    (comp (ref "R46")
      (value "1k")
      (footprint "eagle-import:1005")
      (libsource (lib "eagle-import") (part "R1005"))
    )
    (comp (ref "R47")
      (value "1k")
      (footprint "eagle-import:1005")
      (libsource (lib "eagle-import") (part "R1005"))
    )
    (comp (ref "R48")
      (value "1k")
      (footprint "eagle-import:1005")
      (libsource (lib "eagle-import") (part "R1005"))
    )
    (comp (ref "R49")
      (value "1k")
      (footprint "eagle-import:1005")
      (libsource (lib "eagle-import") (part "R1005"))
    )
    (comp (ref "R50")
      (value "1k")
      (footprint "eagle-import:1005")
      (libsource (lib "eagle-import") (part "R1005"))
    )
    (comp (ref "R51")
      (value "1k")
      (footprint "eagle-import:1005")
      (libsource (lib "eagle-import") (part "R1005"))
    )
    (comp (ref "R52")
      (value "1k")
      (footprint "eagle-import:1005")
      (libsource (lib "eagle-import") (part "R1005"))
    )
    (comp (ref "R53")
      (value "10k")
      (footprint "eagle-import:1005")
      (libsource (lib "eagle-import") (part "R1005"))
    )
    (comp (ref "R54")
      (value "3.9k")
      (footprint "eagle-import:1608")
      (libsource (lib "eagle-import") (part "R1608"))
    )
    (comp (ref "R55")
      (value "3.9k")
      (footprint "eagle-import:1608")
      (libsource (lib "eagle-import") (part "R1608"))
    )
    (comp (ref "R56")
      (value "1k")
      (footprint "eagle-import:1005")
      (libsource (lib "eagle-import") (part "R1005"))
    )
    (comp (ref "R57")
      (value "51")
      (footprint "eagle-import:1005")
      (libsource (lib "eagle-import") (part "R1005"))
    )
    (comp (ref "R58")
      (value "51")
      (footprint "eagle-import:1005")
      (libsource (lib "eagle-import") (part "R1005"))
    )
    (comp (ref "R59")
      (value "51")
      (footprint "eagle-import:1005")
      (libsource (lib "eagle-import") (part "R1005"))
    )
    (comp (ref "R60")
      (value "10k")
      (footprint "eagle-import:1005")
      (libsource (lib "eagle-import") (part "R1005"))
    )
    (comp (ref "R61")
      (value "10k")
      (footprint "eagle-import:1005")
      (libsource (lib "eagle-import") (part "R1005"))
    )
    (comp (ref "RA1")
      (value "51")
      (footprint "eagle-import:1005-A4")
      (libsource (lib "eagle-import") (part "RA4"))
    )
    (comp (ref "RF1")
      (value "200m")
      (footprint "eagle-import:2012")
      (libsource (lib "eagle-import") (part "RF2012"))
    )
    (comp (ref "RF2")
      (value "200m")
      (footprint "eagle-import:2012")
      (libsource (lib "eagle-import") (part "RF2012"))
    )
    (comp (ref "SW2")
      (value "EVQ-P2-RECTANGLE")
      (footprint "eagle-import:EVQ-P2_P9")
      (libsource (lib "eagle-import") (part "EVQ-?P2-RECTANGLE"))
    )
    (comp (ref "SW3")
      (value "EVQ-P2-RECTANGLE")
      (footprint "eagle-import:EVQ-P2_P9")
      (libsource (lib "eagle-import") (part "EVQ-?P2-RECTANGLE"))
    )
    (comp (ref "U4")
      (value "IP4234CZ6")
      (footprint "eagle-import:SOT23-6")
      (libsource (lib "eagle-import") (part "TPD2S017"))
    )
    (comp (ref "U5")
      (value "AT32UC3B0512-AU")
      (footprint "eagle-import:QFP64-0.5")
      (libsource (lib "eagle-import") (part "AT32UC3B0512-AU"))
    )
    (comp (ref "U7")
      (value "MX25L6445EM")
      (footprint "eagle-import:SOP8W")
      (libsource (lib "eagle-import") (part "MX25L6445EM"))
    )
    (comp (ref "U8")
      (value "1G08DCK")
      (footprint "eagle-import:SC70-5")
      (libsource (lib "eagle-import") (part "1G08DCK"))
    )
    (comp (ref "U9")
      (value "XC6SLX9-TQ144")
      (footprint "eagle-import:QFP144-0.5")
      (libsource (lib "eagle-import") (part "XC6SLX9-TQ144"))
    )
    (comp (ref "U10")
      (value "1G08DCK")
      (footprint "eagle-import:SC70-5")
      (libsource (lib "eagle-import") (part "1G08DCK"))
    )
    (comp (ref "U11")
      (value "TC74VHC164FT")
      (footprint "eagle-import:TSSOP14")
      (libsource (lib "eagle-import") (part "TC74VHC164FT"))
    )
    (comp (ref "U12")
      (value "FDG6323L")
      (footprint "eagle-import:SC70-6")
      (libsource (lib "eagle-import") (part "FDG6323L"))
    )
    (comp (ref "U13")
      (value "AE-NJU72501")
      (footprint "eagle-import:AE-NJU72501")
      (libsource (lib "eagle-import") (part "AE-NJU72501"))
    )
    (comp (ref "VR1")
      (value "500")
      (footprint "eagle-import:VR")
      (libsource (lib "eagle-import") (part "VR"))
    )
    (comp (ref "X1")
      (value "24MHz")
      (footprint "eagle-import:OSC2520")
      (libsource (lib "eagle-import") (part "ASDMB"))
    )
    (comp (ref "C2")
      (value "100n")
      (footprint "eagle-import:1608")
      (libsource (lib "eagle-import") (part "C1608"))
    )
    (comp (ref "C3")
      (value "100u")
      (footprint "eagle-import:ES-6.3")
      (libsource (lib "eagle-import") (part "CPOLS-6.3"))
    )
    (comp (ref "C4")
      (value "100u")
      (footprint "eagle-import:ES-6.3")
      (libsource (lib "eagle-import") (part "CPOLS-6.3"))
    )
    (comp (ref "C5")
      (value "10n")
      (footprint "eagle-import:1005")
      (libsource (lib "eagle-import") (part "C1005"))
    )
    (comp (ref "C6")
      (value "10n")
      (footprint "eagle-import:1005")
      (libsource (lib "eagle-import") (part "C1005"))
    )
    (comp (ref "C7")
      (value "330u")
      (footprint "eagle-import:ES2-8")
      (libsource (lib "eagle-import") (part "CPOLS2-8"))
    )
    (comp (ref "C8")
      (value "1u")
      (footprint "eagle-import:1005")
      (libsource (lib "eagle-import") (part "C1005"))
    )
    (comp (ref "C9")
      (value "22u")
      (footprint "eagle-import:3225")
      (libsource (lib "eagle-import") (part "C3225"))
    )
    (comp (ref "C10")
      (value "1u")
      (footprint "eagle-import:1608")
      (libsource (lib "eagle-import") (part "C1608"))
    )
    (comp (ref "C11")
      (value "1u")
      (footprint "eagle-import:1608")
      (libsource (lib "eagle-import") (part "C1608"))
    )
    (comp (ref "C12")
      (value "10n")
      (footprint "eagle-import:1005")
      (libsource (lib "eagle-import") (part "C1005"))
    )
    (comp (ref "C13")
      (value "1u")
      (footprint "eagle-import:1608")
      (libsource (lib "eagle-import") (part "C1608"))
    )
    (comp (ref "C14")
      (value "1n")
      (footprint "eagle-import:1005")
      (libsource (lib "eagle-import") (part "C1005"))
    )
    (comp (ref "C15")
      (value "100u")
      (footprint "eagle-import:3225")
      (libsource (lib "eagle-import") (part "C3225"))
    )
    (comp (ref "C16")
      (value "22u")
      (footprint "eagle-import:3225")
      (libsource (lib "eagle-import") (part "C3225"))
    )
    (comp (ref "C17")
      (value "22u")
      (footprint "eagle-import:3216")
      (libsource (lib "eagle-import") (part "C3216"))
    )
    (comp (ref "C18")
      (value "100u")
      (footprint "eagle-import:3225")
      (libsource (lib "eagle-import") (part "C3225"))
    )
    (comp (ref "C19")
      (value "1u")
      (footprint "eagle-import:1005")
      (libsource (lib "eagle-import") (part "C1005"))
    )
    (comp (ref "C20")
      (value "10n")
      (footprint "eagle-import:1005")
      (libsource (lib "eagle-import") (part "C1005"))
    )
    (comp (ref "C21")
      (value "22u")
      (footprint "eagle-import:3216")
      (libsource (lib "eagle-import") (part "C3216"))
    )
    (comp (ref "C166")
      (value "10n")
      (footprint "eagle-import:1005")
      (libsource (lib "eagle-import") (part "C1005"))
    )
    (comp (ref "C167")
      (value "10n")
      (footprint "eagle-import:1005")
      (libsource (lib "eagle-import") (part "C1005"))
    )
    (comp (ref "CN1")
      (value "Battery")
      (footprint "eagle-import:T-CON")
      (libsource (lib "eagle-import") (part "T-CON"))
    )
    (comp (ref "CN2")
      (value "Kicker")
      (footprint "eagle-import:43045-0800")
      (libsource (lib "eagle-import") (part "43045-0800"))
    )
    (comp (ref "D1")
      (value "SMAJ22A")
      (footprint "eagle-import:DO-214AC")
      (libsource (lib "eagle-import") (part "ZENER-DO-214AC"))
    )
    (comp (ref "D2")
      (value "SMAJ22A")
      (footprint "eagle-import:DO-214AC")
      (libsource (lib "eagle-import") (part "ZENER-DO-214AC"))
    )
    (comp (ref "D3")
      (value "PMEG4030ER")
      (footprint "eagle-import:SOD123W")
      (libsource (lib "eagle-import") (part "SBD-SDO123W"))
    )
    (comp (ref "D4")
      (value "SMAJ24A")
      (footprint "eagle-import:DO-214AC")
      (libsource (lib "eagle-import") (part "ZENER-DO-214AC"))
    )
    (comp (ref "D5")
      (value "PMEG4030ER")
      (footprint "eagle-import:SOD123W")
      (libsource (lib "eagle-import") (part "SBD-SDO123W"))
    )
    (comp (ref "D6")
      (value "PMEG4030ER")
      (footprint "eagle-import:SOD123W")
      (libsource (lib "eagle-import") (part "SBD-SDO123W"))
    )
    (comp (ref "D7")
      (value "PMEG4030ER")
      (footprint "eagle-import:SOD123W")
      (libsource (lib "eagle-import") (part "SBD-SDO123W"))
    )
    (comp (ref "D8")
      (value "PMEG4030ER")
      (footprint "eagle-import:SOD123W")
      (libsource (lib "eagle-import") (part "SBD-SDO123W"))
    )
    (comp (ref "F1")
      (value "15")
      (footprint "eagle-import:3216")
      (libsource (lib "eagle-import") (part "F3216"))
    )
    (comp (ref "F2")
      (value "10")
      (footprint "eagle-import:3216")
      (libsource (lib "eagle-import") (part "F3216"))
    )
    (comp (ref "F3")
      (value "10")
      (footprint "eagle-import:3216")
      (libsource (lib "eagle-import") (part "F3216"))
    )
    (comp (ref "L1")
      (value "4.7u")
      (footprint "eagle-import:L2520")
      (libsource (lib "eagle-import") (part "L2520"))
    )
    (comp (ref "L2")
      (value "3.3u")
      (footprint "eagle-import:L2520")
      (libsource (lib "eagle-import") (part "L2520"))
    )
    (comp (ref "L3")
      (value "10u")
      (footprint "eagle-import:L4040")
      (libsource (lib "eagle-import") (part "L40"))
    )
    (comp (ref "L4")
      (value "4.7u")
      (footprint "eagle-import:L2520")
      (libsource (lib "eagle-import") (part "L2520"))
    )
    (comp (ref "L5")
      (value "4.7u")
      (footprint "eagle-import:L2520")
      (libsource (lib "eagle-import") (part "L2520"))
    )
    (comp (ref "LOGO1")
      (value "LOGO-876_SMALL")
      (footprint "eagle-import:LOGO-876_SMALL")
      (libsource (lib "eagle-import") (part "LOGO-876_SMALL"))
    )
    (comp (ref "Q1")
      (value "MOS-N-SOT23")
      (footprint "eagle-import:SOT23-3")
      (libsource (lib "eagle-import") (part "MOS-N-SOT23"))
    )
    (comp (ref "Q2")
      (value "MOS-N-SOT23")
      (footprint "eagle-import:SOT23-3")
      (libsource (lib "eagle-import") (part "MOS-N-SOT23"))
    )
    (comp (ref "Q3")
      (value "Si4483ADY")
      (footprint "eagle-import:SOP8")
      (libsource (lib "eagle-import") (part "MOS-P-SOP8"))
    )
    (comp (ref "Q4")
      (value "Si4483ADY")
      (footprint "eagle-import:SOP8")
      (libsource (lib "eagle-import") (part "MOS-P-SOP8"))
    )
    (comp (ref "R4")
      (value "100k")
      (footprint "eagle-import:1608")
      (libsource (lib "eagle-import") (part "R1608"))
    )
    (comp (ref "R5")
      (value "10k")
      (footprint "eagle-import:1608")
      (libsource (lib "eagle-import") (part "R1608"))
    )
    (comp (ref "R6")
      (value "100k")
      (footprint "eagle-import:1608")
      (libsource (lib "eagle-import") (part "R1608"))
    )
    (comp (ref "R7")
      (value "10k")
      (footprint "eagle-import:1608")
      (libsource (lib "eagle-import") (part "R1608"))
    )
    (comp (ref "R8")
      (value "10k")
      (footprint "eagle-import:1005")
      (libsource (lib "eagle-import") (part "R1005"))
    )
    (comp (ref "R9")
      (value "100k")
      (footprint "eagle-import:1608")
      (libsource (lib "eagle-import") (part "R1608"))
    )
    (comp (ref "R10")
      (value "24k")
      (footprint "eagle-import:1608")
      (libsource (lib "eagle-import") (part "R1608"))
    )
    (comp (ref "R11")
      (value "10k")
      (footprint "eagle-import:1005")
      (libsource (lib "eagle-import") (part "R1005"))
    )
    (comp (ref "R12")
      (value "10k")
      (footprint "eagle-import:1005")
      (libsource (lib "eagle-import") (part "R1005"))
    )
    (comp (ref "R13")
      (value "1k")
      (footprint "eagle-import:1005")
      (libsource (lib "eagle-import") (part "R1005"))
    )
    (comp (ref "R14")
      (value "3.9k")
      (footprint "eagle-import:1608")
      (libsource (lib "eagle-import") (part "R1608"))
    )
    (comp (ref "R15")
      (value "7.5k")
      (footprint "eagle-import:1608")
      (libsource (lib "eagle-import") (part "R1608"))
    )
    (comp (ref "R16")
      (value "24k")
      (footprint "eagle-import:1608")
      (libsource (lib "eagle-import") (part "R1608"))
    )
    (comp (ref "R17")
      (value "1.65k")
      (footprint "eagle-import:1608")
      (libsource (lib "eagle-import") (part "R1608"))
    )
    (comp (ref "R18")
      (value "24k")
      (footprint "eagle-import:1608")
      (libsource (lib "eagle-import") (part "R1608"))
    )
    (comp (ref "R19")
      (value "3.9k")
      (footprint "eagle-import:1608")
      (libsource (lib "eagle-import") (part "R1608"))
    )
    (comp (ref "R20")
      (value "24k")
      (footprint "eagle-import:1608")
      (libsource (lib "eagle-import") (part "R1608"))
    )
    (comp (ref "R21")
      (value "7.5k")
      (footprint "eagle-import:1608")
      (libsource (lib "eagle-import") (part "R1608"))
    )
    (comp (ref "R22")
      (value "10k")
      (footprint "eagle-import:1005")
      (libsource (lib "eagle-import") (part "R1005"))
    )
    (comp (ref "R23")
      (value "33k")
      (footprint "eagle-import:1005")
      (libsource (lib "eagle-import") (part "R1005"))
    )
    (comp (ref "R24")
      (value "33k")
      (footprint "eagle-import:1005")
      (libsource (lib "eagle-import") (part "R1005"))
    )
    (comp (ref "R25")
      (value "1k")
      (footprint "eagle-import:1005")
      (libsource (lib "eagle-import") (part "R1005"))
    )
    (comp (ref "R26")
      (value "1k")
      (footprint "eagle-import:1005")
      (libsource (lib "eagle-import") (part "R1005"))
    )
    (comp (ref "R27")
      (value "10k")
      (footprint "eagle-import:1005")
      (libsource (lib "eagle-import") (part "R1005"))
    )
    (comp (ref "R28")
      (value "10k")
      (footprint "eagle-import:1005")
      (libsource (lib "eagle-import") (part "R1005"))
    )
    (comp (ref "R29")
      (value "51")
      (footprint "eagle-import:1005")
      (libsource (lib "eagle-import") (part "R1005"))
    )
    (comp (ref "R30")
      (value "51")
      (footprint "eagle-import:1005")
      (libsource (lib "eagle-import") (part "R1005"))
    )
    (comp (ref "R122")
      (value "1k")
      (footprint "eagle-import:1005")
      (libsource (lib "eagle-import") (part "R1005"))
    )
    (comp (ref "R123")
      (value "1k")
      (footprint "eagle-import:1005")
      (libsource (lib "eagle-import") (part "R1005"))
    )
    (comp (ref "SW1")
      (value "Power")
      (footprint "eagle-import:SLE6_10A4")
      (libsource (lib "eagle-import") (part "SLEA46"))
    )
    (comp (ref "U2")
      (value "LT3504")
      (footprint "eagle-import:QFN28-0.5-PAD")
      (libsource (lib "eagle-import") (part "LT3504"))
    )
    (comp (ref "U3")
      (value "SPX3819-50")
      (footprint "eagle-import:SOT23-5")
      (libsource (lib "eagle-import") (part "SPX3819-50"))
    )
    (comp (ref "C68")
      (value "100u")
      (footprint "eagle-import:E2.5-6.3")
      (libsource (lib "eagle-import") (part "CPOL2.5-6.3"))
    )
    (comp (ref "C69")
      (value "1u")
      (footprint "eagle-import:1608")
      (libsource (lib "eagle-import") (part "C1608"))
    )
    (comp (ref "C70")
      (value "1u")
      (footprint "eagle-import:1608")
      (libsource (lib "eagle-import") (part "C1608"))
    )
    (comp (ref "C71")
      (value "1u")
      (footprint "eagle-import:1608")
      (libsource (lib "eagle-import") (part "C1608"))
    )
    (comp (ref "C72")
      (value "100n")
      (footprint "eagle-import:1005")
      (libsource (lib "eagle-import") (part "C1005"))
    )
    (comp (ref "C73")
      (value "1u")
      (footprint "eagle-import:1608")
      (libsource (lib "eagle-import") (part "C1608"))
    )
    (comp (ref "C74")
      (value "100n")
      (footprint "eagle-import:1608")
      (libsource (lib "eagle-import") (part "C1608"))
    )
    (comp (ref "C75")
      (value "100n")
      (footprint "eagle-import:1608")
      (libsource (lib "eagle-import") (part "C1608"))
    )
    (comp (ref "C76")
      (value "100n")
      (footprint "eagle-import:1608")
      (libsource (lib "eagle-import") (part "C1608"))
    )
    (comp (ref "C77")
      (value "100n")
      (footprint "eagle-import:1608")
      (libsource (lib "eagle-import") (part "C1608"))
    )
    (comp (ref "C78")
      (value "100n")
      (footprint "eagle-import:1608")
      (libsource (lib "eagle-import") (part "C1608"))
    )
    (comp (ref "C79")
      (value "100n")
      (footprint "eagle-import:1608")
      (libsource (lib "eagle-import") (part "C1608"))
    )
    (comp (ref "C80")
      (value "220u")
      (footprint "eagle-import:E3.5-8")
      (libsource (lib "eagle-import") (part "CPOL3.5-8"))
    )
    (comp (ref "C83")
      (value "100u")
      (footprint "eagle-import:E2.5-6.3")
      (libsource (lib "eagle-import") (part "CPOL2.5-6.3"))
    )
    (comp (ref "C84")
      (value "1u")
      (footprint "eagle-import:1608")
      (libsource (lib "eagle-import") (part "C1608"))
    )
    (comp (ref "C85")
      (value "1u")
      (footprint "eagle-import:1608")
      (libsource (lib "eagle-import") (part "C1608"))
    )
    (comp (ref "C86")
      (value "1u")
      (footprint "eagle-import:1608")
      (libsource (lib "eagle-import") (part "C1608"))
    )
    (comp (ref "C87")
      (value "100n")
      (footprint "eagle-import:1005")
      (libsource (lib "eagle-import") (part "C1005"))
    )
    (comp (ref "C88")
      (value "1u")
      (footprint "eagle-import:1608")
      (libsource (lib "eagle-import") (part "C1608"))
    )
    (comp (ref "C89")
      (value "100n")
      (footprint "eagle-import:1608")
      (libsource (lib "eagle-import") (part "C1608"))
    )
    (comp (ref "C90")
      (value "100n")
      (footprint "eagle-import:1608")
      (libsource (lib "eagle-import") (part "C1608"))
    )
    (comp (ref "C91")
      (value "100n")
      (footprint "eagle-import:1608")
      (libsource (lib "eagle-import") (part "C1608"))
    )
    (comp (ref "C92")
      (value "100n")
      (footprint "eagle-import:1608")
      (libsource (lib "eagle-import") (part "C1608"))
    )
    (comp (ref "C93")
      (value "100n")
      (footprint "eagle-import:1608")
      (libsource (lib "eagle-import") (part "C1608"))
    )
    (comp (ref "C94")
      (value "100n")
      (footprint "eagle-import:1608")
      (libsource (lib "eagle-import") (part "C1608"))
    )
    (comp (ref "C95")
      (value "220u")
      (footprint "eagle-import:E3.5-8")
      (libsource (lib "eagle-import") (part "CPOL3.5-8"))
    )
    (comp (ref "C98")
      (value "100u")
      (footprint "eagle-import:E2.5-6.3")
      (libsource (lib "eagle-import") (part "CPOL2.5-6.3"))
    )
    (comp (ref "C99")
      (value "1u")
      (footprint "eagle-import:1608")
      (libsource (lib "eagle-import") (part "C1608"))
    )
    (comp (ref "C100")
      (value "1u")
      (footprint "eagle-import:1608")
      (libsource (lib "eagle-import") (part "C1608"))
    )
    (comp (ref "C101")
      (value "1u")
      (footprint "eagle-import:1608")
      (libsource (lib "eagle-import") (part "C1608"))
    )
    (comp (ref "C102")
      (value "100n")
      (footprint "eagle-import:1005")
      (libsource (lib "eagle-import") (part "C1005"))
    )
    (comp (ref "C103")
      (value "1u")
      (footprint "eagle-import:1608")
      (libsource (lib "eagle-import") (part "C1608"))
    )
    (comp (ref "C104")
      (value "100n")
      (footprint "eagle-import:1608")
      (libsource (lib "eagle-import") (part "C1608"))
    )
    (comp (ref "C105")
      (value "100n")
      (footprint "eagle-import:1608")
      (libsource (lib "eagle-import") (part "C1608"))
    )
    (comp (ref "C106")
      (value "100n")
      (footprint "eagle-import:1608")
      (libsource (lib "eagle-import") (part "C1608"))
    )
    (comp (ref "C107")
      (value "100n")
      (footprint "eagle-import:1608")
      (libsource (lib "eagle-import") (part "C1608"))
    )
    (comp (ref "C108")
      (value "100n")
      (footprint "eagle-import:1608")
      (libsource (lib "eagle-import") (part "C1608"))
    )
    (comp (ref "C109")
      (value "100n")
      (footprint "eagle-import:1608")
      (libsource (lib "eagle-import") (part "C1608"))
    )
    (comp (ref "C110")
      (value "220u")
      (footprint "eagle-import:E3.5-8")
      (libsource (lib "eagle-import") (part "CPOL3.5-8"))
    )
    (comp (ref "C113")
      (value "100u")
      (footprint "eagle-import:E2.5-6.3")
      (libsource (lib "eagle-import") (part "CPOL2.5-6.3"))
    )
    (comp (ref "C114")
      (value "1u")
      (footprint "eagle-import:1608")
      (libsource (lib "eagle-import") (part "C1608"))
    )
    (comp (ref "C115")
      (value "1u")
      (footprint "eagle-import:1608")
      (libsource (lib "eagle-import") (part "C1608"))
    )
    (comp (ref "C116")
      (value "1u")
      (footprint "eagle-import:1608")
      (libsource (lib "eagle-import") (part "C1608"))
    )
    (comp (ref "C117")
      (value "100n")
      (footprint "eagle-import:1005")
      (libsource (lib "eagle-import") (part "C1005"))
    )
    (comp (ref "C118")
      (value "1u")
      (footprint "eagle-import:1608")
      (libsource (lib "eagle-import") (part "C1608"))
    )
    (comp (ref "C119")
      (value "100n")
      (footprint "eagle-import:1608")
      (libsource (lib "eagle-import") (part "C1608"))
    )
    (comp (ref "C120")
      (value "100n")
      (footprint "eagle-import:1608")
      (libsource (lib "eagle-import") (part "C1608"))
    )
    (comp (ref "C121")
      (value "100n")
      (footprint "eagle-import:1608")
      (libsource (lib "eagle-import") (part "C1608"))
    )
    (comp (ref "C122")
      (value "100n")
      (footprint "eagle-import:1608")
      (libsource (lib "eagle-import") (part "C1608"))
    )
    (comp (ref "C123")
      (value "100n")
      (footprint "eagle-import:1608")
      (libsource (lib "eagle-import") (part "C1608"))
    )
    (comp (ref "C124")
      (value "100n")
      (footprint "eagle-import:1608")
      (libsource (lib "eagle-import") (part "C1608"))
    )
    (comp (ref "C125")
      (value "220u")
      (footprint "eagle-import:E3.5-8")
      (libsource (lib "eagle-import") (part "CPOL3.5-8"))
    )
    (comp (ref "C128")
      (value "1u")
      (footprint "eagle-import:1005")
      (libsource (lib "eagle-import") (part "C1005"))
    )
    (comp (ref "C129")
      (value "1u")
      (footprint "eagle-import:1005")
      (libsource (lib "eagle-import") (part "C1005"))
    )
    (comp (ref "C130")
      (value "1u")
      (footprint "eagle-import:1005")
      (libsource (lib "eagle-import") (part "C1005"))
    )
    (comp (ref "C131")
      (value "1u")
      (footprint "eagle-import:1005")
      (libsource (lib "eagle-import") (part "C1005"))
    )
    (comp (ref "C132")
      (value "100n")
      (footprint "eagle-import:1005")
      (libsource (lib "eagle-import") (part "C1005"))
    )
    (comp (ref "C133")
      (value "100n")
      (footprint "eagle-import:1005")
      (libsource (lib "eagle-import") (part "C1005"))
    )
    (comp (ref "C140")
      (value "100n")
      (footprint "eagle-import:1005")
      (libsource (lib "eagle-import") (part "C1005"))
    )
    (comp (ref "C141")
      (value "100n")
      (footprint "eagle-import:1005")
      (libsource (lib "eagle-import") (part "C1005"))
    )
    (comp (ref "C149")
      (value "100u")
      (footprint "eagle-import:E2.5-6.3")
      (libsource (lib "eagle-import") (part "CPOL2.5-6.3"))
    )
    (comp (ref "C150")
      (value "1u")
      (footprint "eagle-import:1608")
      (libsource (lib "eagle-import") (part "C1608"))
    )
    (comp (ref "C151")
      (value "1u")
      (footprint "eagle-import:1608")
      (libsource (lib "eagle-import") (part "C1608"))
    )
    (comp (ref "C152")
      (value "1u")
      (footprint "eagle-import:1608")
      (libsource (lib "eagle-import") (part "C1608"))
    )
    (comp (ref "C153")
      (value "100n")
      (footprint "eagle-import:1005")
      (libsource (lib "eagle-import") (part "C1005"))
    )
    (comp (ref "C154")
      (value "1u")
      (footprint "eagle-import:1608")
      (libsource (lib "eagle-import") (part "C1608"))
    )
    (comp (ref "C155")
      (value "100n")
      (footprint "eagle-import:1608")
      (libsource (lib "eagle-import") (part "C1608"))
    )
    (comp (ref "C156")
      (value "100n")
      (footprint "eagle-import:1608")
      (libsource (lib "eagle-import") (part "C1608"))
    )
    (comp (ref "C157")
      (value "100n")
      (footprint "eagle-import:1608")
      (libsource (lib "eagle-import") (part "C1608"))
    )
    (comp (ref "C158")
      (value "100n")
      (footprint "eagle-import:1608")
      (libsource (lib "eagle-import") (part "C1608"))
    )
    (comp (ref "C159")
      (value "100n")
      (footprint "eagle-import:1608")
      (libsource (lib "eagle-import") (part "C1608"))
    )
    (comp (ref "C160")
      (value "100n")
      (footprint "eagle-import:1608")
      (libsource (lib "eagle-import") (part "C1608"))
    )
    (comp (ref "C161")
      (value "220u")
      (footprint "eagle-import:E3.5-8")
      (libsource (lib "eagle-import") (part "CPOL3.5-8"))
    )
    (comp (ref "C163")
      (value "100n")
      (footprint "eagle-import:1005")
      (libsource (lib "eagle-import") (part "C1005"))
    )
    (comp (ref "CN9")
      (value "EC45FLAT2")
      (footprint "eagle-import:MOTOR_COMPLEX2")
      (libsource (lib "eagle-import") (part "EC45FLAT2"))
    )
    (comp (ref "CN10")
      (value "Motor1")
      (footprint "eagle-import:53375-04")
      (libsource (lib "eagle-import") (part "53375-0410"))
    )
    (comp (ref "CN11")
      (value "EC45FLAT2")
      (footprint "eagle-import:MOTOR_COMPLEX2")
      (libsource (lib "eagle-import") (part "EC45FLAT2"))
    )
    (comp (ref "CN12")
      (value "Motor2")
      (footprint "eagle-import:53375-04")
      (libsource (lib "eagle-import") (part "53375-0410"))
    )
    (comp (ref "CN13")
      (value "EC45FLAT2")
      (footprint "eagle-import:MOTOR_COMPLEX2")
      (libsource (lib "eagle-import") (part "EC45FLAT2"))
    )
    (comp (ref "CN14")
      (value "Motor3")
      (footprint "eagle-import:53375-04")
      (libsource (lib "eagle-import") (part "53375-0410"))
    )
    (comp (ref "CN15")
      (value "EC45FLAT2")
      (footprint "eagle-import:MOTOR_COMPLEX2")
      (libsource (lib "eagle-import") (part "EC45FLAT2"))
    )
    (comp (ref "CN16")
      (value "Motor4")
      (footprint "eagle-import:53375-04")
      (libsource (lib "eagle-import") (part "53375-0410"))
    )
    (comp (ref "CN17")
      (value "Dribble")
      (footprint "eagle-import:PIN1X8")
      (libsource (lib "eagle-import") (part "PIN1X8"))
    )
    (comp (ref "R62")
      (value "33k")
      (footprint "eagle-import:1608")
      (libsource (lib "eagle-import") (part "R1608"))
    )
    (comp (ref "R63")
      (value "1")
      (footprint "eagle-import:1005")
      (libsource (lib "eagle-import") (part "R1005"))
    )
    (comp (ref "R66")
      (value "33k")
      (footprint "eagle-import:1608")
      (libsource (lib "eagle-import") (part "R1608"))
    )
    (comp (ref "R67")
      (value "1")
      (footprint "eagle-import:1005")
      (libsource (lib "eagle-import") (part "R1005"))
    )
    (comp (ref "R70")
      (value "33k")
      (footprint "eagle-import:1608")
      (libsource (lib "eagle-import") (part "R1608"))
    )
    (comp (ref "R71")
      (value "1")
      (footprint "eagle-import:1005")
      (libsource (lib "eagle-import") (part "R1005"))
    )
    (comp (ref "R74")
      (value "33k")
      (footprint "eagle-import:1608")
      (libsource (lib "eagle-import") (part "R1608"))
    )
    (comp (ref "R75")
      (value "1")
      (footprint "eagle-import:1005")
      (libsource (lib "eagle-import") (part "R1005"))
    )
    (comp (ref "R78")
      (value "100k")
      (footprint "eagle-import:1005")
      (libsource (lib "eagle-import") (part "R1005"))
    )
    (comp (ref "R79")
      (value "100k")
      (footprint "eagle-import:1005")
      (libsource (lib "eagle-import") (part "R1005"))
    )
    (comp (ref "R80")
      (value "100k")
      (footprint "eagle-import:1005")
      (libsource (lib "eagle-import") (part "R1005"))
    )
    (comp (ref "R81")
      (value "100k")
      (footprint "eagle-import:1005")
      (libsource (lib "eagle-import") (part "R1005"))
    )
    (comp (ref "R82")
      (value "100k")
      (footprint "eagle-import:1005")
      (libsource (lib "eagle-import") (part "R1005"))
    )
    (comp (ref "R83")
      (value "100k")
      (footprint "eagle-import:1005")
      (libsource (lib "eagle-import") (part "R1005"))
    )
    (comp (ref "R84")
      (value "100k")
      (footprint "eagle-import:1005")
      (libsource (lib "eagle-import") (part "R1005"))
    )
    (comp (ref "R85")
      (value "100k")
      (footprint "eagle-import:1005")
      (libsource (lib "eagle-import") (part "R1005"))
    )
    (comp (ref "R86")
      (value "100k")
      (footprint "eagle-import:1005")
      (libsource (lib "eagle-import") (part "R1005"))
    )
    (comp (ref "R87")
      (value "100k")
      (footprint "eagle-import:1005")
      (libsource (lib "eagle-import") (part "R1005"))
    )
    (comp (ref "R88")
      (value "100k")
      (footprint "eagle-import:1005")
      (libsource (lib "eagle-import") (part "R1005"))
    )
    (comp (ref "R89")
      (value "100k")
      (footprint "eagle-import:1005")
      (libsource (lib "eagle-import") (part "R1005"))
    )
    (comp (ref "R90")
      (value "100k")
      (footprint "eagle-import:1005")
      (libsource (lib "eagle-import") (part "R1005"))
    )
    (comp (ref "R91")
      (value "100k")
      (footprint "eagle-import:1005")
      (libsource (lib "eagle-import") (part "R1005"))
    )
    (comp (ref "R92")
      (value "100k")
      (footprint "eagle-import:1005")
      (libsource (lib "eagle-import") (part "R1005"))
    )
    (comp (ref "R93")
      (value "100k")
      (footprint "eagle-import:1005")
      (libsource (lib "eagle-import") (part "R1005"))
    )
    (comp (ref "R94")
      (value "100k")
      (footprint "eagle-import:1005")
      (libsource (lib "eagle-import") (part "R1005"))
    )
    (comp (ref "R95")
      (value "100k")
      (footprint "eagle-import:1005")
      (libsource (lib "eagle-import") (part "R1005"))
    )
    (comp (ref "R96")
      (value "100k")
      (footprint "eagle-import:1005")
      (libsource (lib "eagle-import") (part "R1005"))
    )
    (comp (ref "R97")
      (value "100k")
      (footprint "eagle-import:1005")
      (libsource (lib "eagle-import") (part "R1005"))
    )
    (comp (ref "R98")
      (value "33k")
      (footprint "eagle-import:1005")
      (libsource (lib "eagle-import") (part "R1005"))
    )
    (comp (ref "R99")
      (value "100k")
      (footprint "eagle-import:1005")
      (libsource (lib "eagle-import") (part "R1005"))
    )
    (comp (ref "R104")
      (value "100k")
      (footprint "eagle-import:1005")
      (libsource (lib "eagle-import") (part "R1005"))
    )
    (comp (ref "R105")
      (value "33k")
      (footprint "eagle-import:1005")
      (libsource (lib "eagle-import") (part "R1005"))
    )
    (comp (ref "R110")
      (value "10k")
      (footprint "eagle-import:1005")
      (libsource (lib "eagle-import") (part "R1005"))
    )
    (comp (ref "R111")
      (value "10k")
      (footprint "eagle-import:1005")
      (libsource (lib "eagle-import") (part "R1005"))
    )
    (comp (ref "R112")
      (value "10k")
      (footprint "eagle-import:1005")
      (libsource (lib "eagle-import") (part "R1005"))
    )
    (comp (ref "R113")
      (value "10k")
      (footprint "eagle-import:1005")
      (libsource (lib "eagle-import") (part "R1005"))
    )
    (comp (ref "R117")
      (value "33k")
      (footprint "eagle-import:1608")
      (libsource (lib "eagle-import") (part "R1608"))
    )
    (comp (ref "R118")
      (value "1")
      (footprint "eagle-import:1005")
      (libsource (lib "eagle-import") (part "R1005"))
    )
    (comp (ref "R119")
      (value "10k")
      (footprint "eagle-import:1005")
      (libsource (lib "eagle-import") (part "R1005"))
    )
    (comp (ref "R120")
      (value "10k")
      (footprint "eagle-import:1005")
      (libsource (lib "eagle-import") (part "R1005"))
    )
    (comp (ref "R121")
      (value "10k")
      (footprint "eagle-import:1005")
      (libsource (lib "eagle-import") (part "R1005"))
    )
    (comp (ref "RA2")
      (value "51")
      (footprint "eagle-import:1005-A4")
      (libsource (lib "eagle-import") (part "RA4"))
    )
    (comp (ref "RA3")
      (value "51")
      (footprint "eagle-import:1005-A4")
      (libsource (lib "eagle-import") (part "RA4"))
    )
    (comp (ref "RA4")
      (value "51")
      (footprint "eagle-import:1005-A4")
      (libsource (lib "eagle-import") (part "RA4"))
    )
    (comp (ref "RA5")
      (value "51")
      (footprint "eagle-import:1005-A4")
      (libsource (lib "eagle-import") (part "RA4"))
    )
    (comp (ref "RA6")
      (value "51")
      (footprint "eagle-import:1005-A4")
      (libsource (lib "eagle-import") (part "RA4"))
    )
    (comp (ref "RA7")
      (value "51")
      (footprint "eagle-import:1005-A4")
      (libsource (lib "eagle-import") (part "RA4"))
    )
    (comp (ref "RA8")
      (value "51")
      (footprint "eagle-import:1005-A4")
      (libsource (lib "eagle-import") (part "RA4"))
    )
    (comp (ref "RA9")
      (value "51")
      (footprint "eagle-import:1005-A4")
      (libsource (lib "eagle-import") (part "RA4"))
    )
    (comp (ref "RA10")
      (value "51")
      (footprint "eagle-import:1005-A4")
      (libsource (lib "eagle-import") (part "RA4"))
    )
    (comp (ref "RA11")
      (value "51")
      (footprint "eagle-import:1005-A4")
      (libsource (lib "eagle-import") (part "RA4"))
    )
    (comp (ref "RF3")
      (value "200m")
      (footprint "eagle-import:2012")
      (libsource (lib "eagle-import") (part "RF2012"))
    )
    (comp (ref "RF4")
      (value "200m")
      (footprint "eagle-import:2012")
      (libsource (lib "eagle-import") (part "RF2012"))
    )
    (comp (ref "U14")
      (value "DRV8332")
      (footprint "eagle-import:HSSOP36")
      (libsource (lib "eagle-import") (part "DRV8332"))
    )
    (comp (ref "U17")
      (value "DRV8332")
      (footprint "eagle-import:HSSOP36")
      (libsource (lib "eagle-import") (part "DRV8332"))
    )
    (comp (ref "U20")
      (value "DRV8332")
      (footprint "eagle-import:HSSOP36")
      (libsource (lib "eagle-import") (part "DRV8332"))
    )
    (comp (ref "U23")
      (value "DRV8332")
      (footprint "eagle-import:HSSOP36")
      (libsource (lib "eagle-import") (part "DRV8332"))
    )
    (comp (ref "U26")
      (value "TC74VHC165FT")
      (footprint "eagle-import:TSSOP16")
      (libsource (lib "eagle-import") (part "TC74VHC165FT"))
    )
    (comp (ref "U27")
      (value "TC74VHC165FT")
      (footprint "eagle-import:TSSOP16")
      (libsource (lib "eagle-import") (part "TC74VHC165FT"))
    )
    (comp (ref "U30")
      (value "TC74VHC165FT")
      (footprint "eagle-import:TSSOP16")
      (libsource (lib "eagle-import") (part "TC74VHC165FT"))
    )
    (comp (ref "U31")
      (value "TC74VHC165FT")
      (footprint "eagle-import:TSSOP16")
      (libsource (lib "eagle-import") (part "TC74VHC165FT"))
    )
    (comp (ref "U34")
      (value "FDG6323L")
      (footprint "eagle-import:SC70-6")
      (libsource (lib "eagle-import") (part "FDG6323L"))
    )
    (comp (ref "U35")
      (value "FDG6323L")
      (footprint "eagle-import:SC70-6")
      (libsource (lib "eagle-import") (part "FDG6323L"))
    )
    (comp (ref "U37")
      (value "DRV8332")
      (footprint "eagle-import:HSSOP36")
      (libsource (lib "eagle-import") (part "DRV8332"))
    )
    (comp (ref "U39")
      (value "MCP9701/LT")
      (footprint "eagle-import:SC70-5")
      (libsource (lib "eagle-import") (part "MCP970/LT1"))
    )
  )
  (nets
    (net (code "1") (name "+1V2") (class "Default")
      (node (ref "C15") (pin "1") (pinfunction "1_1") (pintype "passive"))
      (node (ref "C55") (pin "2") (pinfunction "2_2") (pintype "passive"))
      (node (ref "C56") (pin "2") (pinfunction "2_2") (pintype "passive"))
      (node (ref "C58") (pin "2") (pinfunction "2_2") (pintype "passive"))
      (node (ref "C60") (pin "2") (pinfunction "2_2") (pintype "passive"))
      (node (ref "C62") (pin "2") (pinfunction "2_2") (pintype "passive"))
      (node (ref "L2") (pin "2") (pinfunction "2_2") (pintype "passive"))
      (node (ref "R14") (pin "2") (pinfunction "2_2") (pintype "passive"))
    )
    (net (code "2") (name "+3V3") (class "Default")
      (node (ref "C132") (pin "1") (pinfunction "1_1") (pintype "passive"))
      (node (ref "C133") (pin "1") (pinfunction "1_1") (pintype "passive"))
      (node (ref "C140") (pin "1") (pinfunction "1_1") (pintype "passive"))
      (node (ref "C141") (pin "1") (pinfunction "1_1") (pintype "passive"))
      (node (ref "C163") (pin "1") (pinfunction "1_1") (pintype "passive"))
      (node (ref "C18") (pin "1") (pinfunction "1_1") (pintype "passive"))
      (node (ref "C23") (pin "1") (pinfunction "1_1") (pintype "passive"))
      (node (ref "C26") (pin "1") (pinfunction "1_1") (pintype "passive"))
      (node (ref "C28") (pin "1") (pinfunction "1_1") (pintype "passive"))
      (node (ref "C30") (pin "1") (pinfunction "1_1") (pintype "passive"))
      (node (ref "C33") (pin "1") (pinfunction "1_1") (pintype "passive"))
      (node (ref "C35") (pin "1") (pinfunction "1_1") (pintype "passive"))
      (node (ref "C37") (pin "1") (pinfunction "1_1") (pintype "passive"))
      (node (ref "C38") (pin "1") (pinfunction "1_1") (pintype "passive"))
      (node (ref "C39") (pin "1") (pinfunction "1_1") (pintype "passive"))
      (node (ref "C40") (pin "1") (pinfunction "1_1") (pintype "passive"))
      (node (ref "C41") (pin "1") (pinfunction "1_1") (pintype "passive"))
      (node (ref "C43") (pin "1") (pinfunction "1_1") (pintype "passive"))
      (node (ref "C44") (pin "1") (pinfunction "1_1") (pintype "passive"))
      (node (ref "C45") (pin "1") (pinfunction "1_1") (pintype "passive"))
      (node (ref "C46") (pin "1") (pinfunction "1_1") (pintype "passive"))
      (node (ref "C47") (pin "1") (pinfunction "1_1") (pintype "passive"))
      (node (ref "C48") (pin "1") (pinfunction "1_1") (pintype "passive"))
      (node (ref "C49") (pin "1") (pinfunction "1_1") (pintype "passive"))
      (node (ref "C50") (pin "1") (pinfunction "1_1") (pintype "passive"))
      (node (ref "C51") (pin "1") (pinfunction "1_1") (pintype "passive"))
      (node (ref "C52") (pin "1") (pinfunction "1_1") (pintype "passive"))
      (node (ref "C53") (pin "1") (pinfunction "1_1") (pintype "passive"))
      (node (ref "C54") (pin "1") (pinfunction "1_1") (pintype "passive"))
      (node (ref "C57") (pin "1") (pinfunction "1_1") (pintype "passive"))
      (node (ref "C59") (pin "1") (pinfunction "1_1") (pintype "passive"))
      (node (ref "C61") (pin "1") (pinfunction "1_1") (pintype "passive"))
      (node (ref "C64") (pin "1") (pinfunction "1_1") (pintype "passive"))
      (node (ref "C67") (pin "1") (pinfunction "1_1") (pintype "passive"))
      (node (ref "CN18") (pin "2") (pinfunction "2_2") (pintype "passive"))
      (node (ref "CN2") (pin "2") (pinfunction "2_2") (pintype "passive"))
      (node (ref "CN4") (pin "4") (pinfunction "VCC_4") (pintype "passive"))
      (node (ref "CN5") (pin "3") (pinfunction "3_3") (pintype "passive"))
      (node (ref "CN6") (pin "1") (pinfunction "1_1") (pintype "passive"))
      (node (ref "FB1") (pin "1") (pinfunction "1_1") (pintype "passive"))
      (node (ref "L5") (pin "2") (pinfunction "2_2") (pintype "passive"))
      (node (ref "R20") (pin "2") (pinfunction "2_2") (pintype "passive"))
      (node (ref "R36") (pin "2") (pinfunction "2_2") (pintype "passive"))
      (node (ref "R37") (pin "2") (pinfunction "2_2") (pintype "passive"))
      (node (ref "R42") (pin "2") (pinfunction "2_2") (pintype "passive"))
      (node (ref "R54") (pin "2") (pinfunction "2_2") (pintype "passive"))
      (node (ref "R55") (pin "2") (pinfunction "2_2") (pintype "passive"))
      (node (ref "R58") (pin "2") (pinfunction "2_2") (pintype "passive"))
      (node (ref "R59") (pin "2") (pinfunction "2_2") (pintype "passive"))
      (node (ref "RF2") (pin "2") (pinfunction "2_2") (pintype "passive"))
      (node (ref "U10") (pin "5") (pinfunction "VCC_5") (pintype "bidirectional"))
      (node (ref "U11") (pin "1") (pinfunction "A_1") (pintype "bidirectional"))
      (node (ref "U11") (pin "14") (pinfunction "VCC_14") (pintype "bidirectional"))
      (node (ref "U11") (pin "9") (pinfunction "~{CLR}_9") (pintype "bidirectional"))
      (node (ref "U13") (pin "1") (pinfunction "VIN_1") (pintype "bidirectional"))
      (node (ref "U13") (pin "5") (pinfunction "EN2_5") (pintype "bidirectional"))
      (node (ref "U13") (pin "6") (pinfunction "EN1_6") (pintype "bidirectional"))
      (node (ref "U26") (pin "16") (pinfunction "VCC_16") (pintype "bidirectional"))
      (node (ref "U27") (pin "16") (pinfunction "VCC_16") (pintype "bidirectional"))
      (node (ref "U30") (pin "16") (pinfunction "VCC_16") (pintype "bidirectional"))
      (node (ref "U31") (pin "16") (pinfunction "VCC_16") (pintype "bidirectional"))
      (node (ref "U39") (pin "4") (pinfunction "VDD_4") (pintype "bidirectional"))
      (node (ref "U5") (pin "18") (pinfunction "ADVREF_18") (pintype "bidirectional"))
      (node (ref "U5") (pin "19") (pinfunction "VDDANA_19") (pintype "bidirectional"))
      (node (ref "U5") (pin "21") (pinfunction "VDDIN_21") (pintype "bidirectional"))
      (node (ref "U5") (pin "32") (pinfunction "VDDIO_32") (pintype "bidirectional"))
      (node (ref "U5") (pin "48") (pinfunction "VDDIO_48") (pintype "bidirectional"))
      (node (ref "U5") (pin "64") (pinfunction "VDDIO_64") (pintype "bidirectional"))
      (node (ref "U7") (pin "3") (pinfunction "~{WP}/SIO2_3") (pintype "bidirectional"))
      (node (ref "U7") (pin "8") (pinfunction "VCC_8") (pintype "bidirectional"))
      (node (ref "U8") (pin "5") (pinfunction "VCC_5") (pintype "bidirectional"))
      (node (ref "U9") (pin "103") (pinfunction "VCCO_1_103") (pintype "bidirectional"))
      (node (ref "U9") (pin "122") (pinfunction "VCCO_0_122") (pintype "bidirectional"))
      (node (ref "U9") (pin "125") (pinfunction "VCCO_0_125") (pintype "bidirectional"))
      (node (ref "U9") (pin "129") (pinfunction "VCCAUX_129") (pintype "bidirectional"))
      (node (ref "U9") (pin "135") (pinfunction "VCCO_0_135") (pintype "bidirectional"))
      (node (ref "U9") (pin "18") (pinfunction "VCCO_3_18") (pintype "bidirectional"))
      (node (ref "U9") (pin "20") (pinfunction "VCCAUX_20") (pintype "bidirectional"))
      (node (ref "U9") (pin "31") (pinfunction "VCCO_3_31") (pintype "bidirectional"))
      (node (ref "U9") (pin "36") (pinfunction "VCCAUX_36") (pintype "bidirectional"))
      (node (ref "U9") (pin "4") (pinfunction "VCCO_3_4") (pintype "bidirectional"))
      (node (ref "U9") (pin "42") (pinfunction "VCCO_2_42") (pintype "bidirectional"))
      (node (ref "U9") (pin "53") (pinfunction "VCCAUX_53") (pintype "bidirectional"))
      (node (ref "U9") (pin "63") (pinfunction "VCCO_2_63") (pintype "bidirectional"))
      (node (ref "U9") (pin "72") (pinfunction "CMPCS_B_2_72") (pintype "bidirectional"))
      (node (ref "U9") (pin "76") (pinfunction "VCCO_1_76") (pintype "bidirectional"))
      (node (ref "U9") (pin "86") (pinfunction "VCCO_1_86") (pintype "bidirectional"))
      (node (ref "U9") (pin "90") (pinfunction "VCCAUX_90") (pintype "bidirectional"))
      (node (ref "X1") (pin "1") (pinfunction "EN_1") (pintype "bidirectional"))
      (node (ref "X1") (pin "4") (pinfunction "VDD_4") (pintype "bidirectional"))
    )
    (net (code "3") (name "+5V") (class "Default")
      (node (ref "C21") (pin "1") (pinfunction "1_1") (pintype "passive"))
      (node (ref "R111") (pin "2") (pinfunction "2_2") (pintype "passive"))
      (node (ref "R113") (pin "2") (pinfunction "2_2") (pintype "passive"))
      (node (ref "RF1") (pin "2") (pinfunction "2_2") (pintype "passive"))
      (node (ref "U3") (pin "5") (pinfunction "OUT_5") (pintype "bidirectional"))
      (node (ref "U34") (pin "4") (pinfunction "IN_4") (pintype "bidirectional"))
      (node (ref "U35") (pin "4") (pinfunction "IN_4") (pintype "bidirectional"))
    )
    (net (code "4") (name "+5V{slash}2") (class "Default")
      (node (ref "C128") (pin "1") (pinfunction "1_1") (pintype "passive"))
      (node (ref "C129") (pin "1") (pinfunction "1_1") (pintype "passive"))
      (node (ref "CN10") (pin "4") (pinfunction "4_4") (pintype "passive"))
      (node (ref "CN11") (pin "1.1") (pinfunction "VCC_1.1") (pintype "bidirectional"))
      (node (ref "CN11") (pin "2.8") (pinfunction "VCC_2.8") (pintype "bidirectional"))
      (node (ref "CN12") (pin "4") (pinfunction "4_4") (pintype "passive"))
      (node (ref "CN9") (pin "1.1") (pinfunction "VCC_1.1") (pintype "bidirectional"))
      (node (ref "CN9") (pin "2.8") (pinfunction "VCC_2.8") (pintype "bidirectional"))
      (node (ref "RF3") (pin "1") (pinfunction "1_1") (pintype "passive"))
    )
    (net (code "5") (name "+5V{slash}3") (class "Default")
      (node (ref "C130") (pin "1") (pinfunction "1_1") (pintype "passive"))
      (node (ref "C131") (pin "1") (pinfunction "1_1") (pintype "passive"))
      (node (ref "CN13") (pin "1.1") (pinfunction "VCC_1.1") (pintype "bidirectional"))
      (node (ref "CN13") (pin "2.8") (pinfunction "VCC_2.8") (pintype "bidirectional"))
      (node (ref "CN14") (pin "4") (pinfunction "4_4") (pintype "passive"))
      (node (ref "CN15") (pin "1.1") (pinfunction "VCC_1.1") (pintype "bidirectional"))
      (node (ref "CN15") (pin "2.8") (pinfunction "VCC_2.8") (pintype "bidirectional"))
      (node (ref "CN16") (pin "4") (pinfunction "4_4") (pintype "passive"))
      (node (ref "CN17") (pin "4") (pinfunction "4_4") (pintype "passive"))
      (node (ref "R119") (pin "2") (pinfunction "2_2") (pintype "passive"))
      (node (ref "R120") (pin "2") (pinfunction "2_2") (pintype "passive"))
      (node (ref "R121") (pin "2") (pinfunction "2_2") (pintype "passive"))
      (node (ref "RF4") (pin "1") (pinfunction "1_1") (pintype "passive"))
    )
    (net (code "6") (name "+12V") (class "Default")
      (node (ref "C100") (pin "1") (pinfunction "1_1") (pintype "passive"))
      (node (ref "C101") (pin "1") (pinfunction "1_1") (pintype "passive"))
      (node (ref "C103") (pin "1") (pinfunction "1_1") (pintype "passive"))
      (node (ref "C113") (pin "P") (pinfunction "P_P") (pintype "passive"))
      (node (ref "C114") (pin "1") (pinfunction "1_1") (pintype "passive"))
      (node (ref "C115") (pin "1") (pinfunction "1_1") (pintype "passive"))
      (node (ref "C116") (pin "1") (pinfunction "1_1") (pintype "passive"))
      (node (ref "C118") (pin "1") (pinfunction "1_1") (pintype "passive"))
      (node (ref "C14") (pin "2") (pinfunction "2_2") (pintype "passive"))
      (node (ref "C149") (pin "P") (pinfunction "P_P") (pintype "passive"))
      (node (ref "C150") (pin "1") (pinfunction "1_1") (pintype "passive"))
      (node (ref "C151") (pin "1") (pinfunction "1_1") (pintype "passive"))
      (node (ref "C152") (pin "1") (pinfunction "1_1") (pintype "passive"))
      (node (ref "C154") (pin "1") (pinfunction "1_1") (pintype "passive"))
      (node (ref "C16") (pin "1") (pinfunction "1_1") (pintype "passive"))
      (node (ref "C68") (pin "P") (pinfunction "P_P") (pintype "passive"))
      (node (ref "C69") (pin "1") (pinfunction "1_1") (pintype "passive"))
      (node (ref "C70") (pin "1") (pinfunction "1_1") (pintype "passive"))
      (node (ref "C71") (pin "1") (pinfunction "1_1") (pintype "passive"))
      (node (ref "C73") (pin "1") (pinfunction "1_1") (pintype "passive"))
      (node (ref "C83") (pin "P") (pinfunction "P_P") (pintype "passive"))
      (node (ref "C84") (pin "1") (pinfunction "1_1") (pintype "passive"))
      (node (ref "C85") (pin "1") (pinfunction "1_1") (pintype "passive"))
      (node (ref "C86") (pin "1") (pinfunction "1_1") (pintype "passive"))
      (node (ref "C88") (pin "1") (pinfunction "1_1") (pintype "passive"))
      (node (ref "C98") (pin "P") (pinfunction "P_P") (pintype "passive"))
      (node (ref "C99") (pin "1") (pinfunction "1_1") (pintype "passive"))
      (node (ref "L3") (pin "2") (pinfunction "2_2") (pintype "passive"))
      (node (ref "R16") (pin "2") (pinfunction "2_2") (pintype "passive"))
      (node (ref "R6") (pin "2") (pinfunction "2_2") (pintype "passive"))
      (node (ref "U14") (pin "1") (pinfunction "GVDD_B_1") (pintype "bidirectional"))
      (node (ref "U14") (pin "17") (pinfunction "VDD_17") (pintype "bidirectional"))
      (node (ref "U14") (pin "18") (pinfunction "GVDD_C_18") (pintype "bidirectional"))
      (node (ref "U14") (pin "19") (pinfunction "GVDD_C_19") (pintype "bidirectional"))
      (node (ref "U14") (pin "36") (pinfunction "GVDD_A_36") (pintype "bidirectional"))
      (node (ref "U17") (pin "1") (pinfunction "GVDD_B_1") (pintype "bidirectional"))
      (node (ref "U17") (pin "17") (pinfunction "VDD_17") (pintype "bidirectional"))
      (node (ref "U17") (pin "18") (pinfunction "GVDD_C_18") (pintype "bidirectional"))
      (node (ref "U17") (pin "19") (pinfunction "GVDD_C_19") (pintype "bidirectional"))
      (node (ref "U17") (pin "36") (pinfunction "GVDD_A_36") (pintype "bidirectional"))
      (node (ref "U20") (pin "1") (pinfunction "GVDD_B_1") (pintype "bidirectional"))
      (node (ref "U20") (pin "17") (pinfunction "VDD_17") (pintype "bidirectional"))
      (node (ref "U20") (pin "18") (pinfunction "GVDD_C_18") (pintype "bidirectional"))
      (node (ref "U20") (pin "19") (pinfunction "GVDD_C_19") (pintype "bidirectional"))
      (node (ref "U20") (pin "36") (pinfunction "GVDD_A_36") (pintype "bidirectional"))
      (node (ref "U23") (pin "1") (pinfunction "GVDD_B_1") (pintype "bidirectional"))
      (node (ref "U23") (pin "17") (pinfunction "VDD_17") (pintype "bidirectional"))
      (node (ref "U23") (pin "18") (pinfunction "GVDD_C_18") (pintype "bidirectional"))
      (node (ref "U23") (pin "19") (pinfunction "GVDD_C_19") (pintype "bidirectional"))
      (node (ref "U23") (pin "36") (pinfunction "GVDD_A_36") (pintype "bidirectional"))
      (node (ref "U37") (pin "1") (pinfunction "GVDD_B_1") (pintype "bidirectional"))
      (node (ref "U37") (pin "17") (pinfunction "VDD_17") (pintype "bidirectional"))
      (node (ref "U37") (pin "18") (pinfunction "GVDD_C_18") (pintype "bidirectional"))
      (node (ref "U37") (pin "19") (pinfunction "GVDD_C_19") (pintype "bidirectional"))
      (node (ref "U37") (pin "36") (pinfunction "GVDD_A_36") (pintype "bidirectional"))
    )
    (net (code "7") (name "BALL_DETECT{slash}BALL_SDA") (class "Default")
      (node (ref "R56") (pin "2") (pinfunction "2_2") (pintype "passive"))
      (node (ref "U9") (pin "112") (pinfunction "IO_L66P_SCP1_0_112") (pintype "bidirectional"))
    )
    (net (code "8") (name "BALL_EN") (class "Default")
      (node (ref "R60") (pin "2") (pinfunction "2_2") (pintype "passive"))
      (node (ref "U12") (pin "5") (pinfunction "EN_5") (pintype "bidirectional"))
      (node (ref "U9") (pin "116") (pinfunction "IO_L64N_SCP4_0_116") (pintype "bidirectional"))
    )
    (net (code "9") (name "BALL_SCL") (class "Default")
      (node (ref "R57") (pin "2") (pinfunction "2_2") (pintype "passive"))
      (node (ref "U9") (pin "114") (pinfunction "IO_L65N_SCP2_0_114") (pintype "bidirectional"))
    )
    (net (code "10") (name "BUZZER_PWM") (class "Default")
      (node (ref "C65") (pin "1") (pinfunction "1_1") (pintype "passive"))
      (node (ref "R45") (pin "1") (pinfunction "1_1") (pintype "passive"))
      (node (ref "U13") (pin "3") (pinfunction "DIN_3") (pintype "bidirectional"))
    )
    (net (code "11") (name "CHARGER_RX") (class "Default")
      (node (ref "CN2") (pin "5") (pinfunction "5_5") (pintype "passive"))
      (node (ref "R39") (pin "2") (pinfunction "2_2") (pintype "passive"))
    )
    (net (code "12") (name "CHARGER_TX") (class "Default")
      (node (ref "CN2") (pin "6") (pinfunction "6_6") (pintype "passive"))
      (node (ref "R38") (pin "2") (pinfunction "2_2") (pintype "passive"))
    )
    (net (code "13") (name "DEBUG_RX") (class "Default")
      (node (ref "CN5") (pin "2") (pinfunction "2_2") (pintype "passive"))
      (node (ref "RA1") (pin "C2") (pinfunction "2_C2") (pintype "passive"))
    )
    (net (code "14") (name "DEBUG_TX") (class "Default")
      (node (ref "CN5") (pin "1") (pinfunction "1_1") (pintype "passive"))
      (node (ref "RA1") (pin "A2") (pinfunction "2_A2") (pintype "passive"))
    )
    (net (code "15") (name "EXT1_CE") (class "Default")
      (node (ref "CN6") (pin "2") (pinfunction "2_2") (pintype "passive"))
      (node (ref "U9") (pin "117") (pinfunction "IO_L64P_SCP5_0_117") (pintype "bidirectional"))
    )
    (net (code "16") (name "EXT1_CSN") (class "Default")
      (node (ref "CN6") (pin "3") (pinfunction "3_3") (pintype "passive"))
      (node (ref "U9") (pin "119") (pinfunction "IO_L63P_SCP7_0_119") (pintype "bidirectional"))
    )
    (net (code "17") (name "EXT1_IRQ") (class "Default")
      (node (ref "CN6") (pin "7") (pinfunction "7_7") (pintype "passive"))
      (node (ref "U9") (pin "132") (pinfunction "IO_L35P_GCLK17_0_132") (pintype "bidirectional"))
    )
    (net (code "18") (name "EXT1_MISO") (class "Default")
      (node (ref "CN6") (pin "6") (pinfunction "6_6") (pintype "passive"))
      (node (ref "U9") (pin "127") (pinfunction "IO_L36P_GCLK15_0_127") (pintype "bidirectional"))
    )
    (net (code "19") (name "EXT1_MOSI") (class "Default")
      (node (ref "CN6") (pin "5") (pinfunction "5_5") (pintype "passive"))
      (node (ref "U9") (pin "124") (pinfunction "IO_L37P_GCLK13_0_124") (pintype "bidirectional"))
    )
    (net (code "20") (name "EXT1_SCK") (class "Default")
      (node (ref "CN6") (pin "4") (pinfunction "4_4") (pintype "passive"))
      (node (ref "U9") (pin "121") (pinfunction "IO_L62P_0_121") (pintype "bidirectional"))
    )
    (net (code "21") (name "FPGA_AUX0") (class "Default")
      (node (ref "CN18") (pin "8") (pinfunction "8_8") (pintype "passive"))
      (node (ref "U5") (pin "30") (pinfunction "PA11/XIN32/PWM0/TC-A2/USART0-RTS/SSC-RXDAT_30") (pintype "bidirectional"))
      (node (ref "U9") (pin "69") (pinfunction "IO_L1N_M0_CMPMISO_2_69") (pintype "bidirectional"))
    )
    (net (code "22") (name "FPGA_AUX1") (class "Default")
      (node (ref "CN18") (pin "4") (pinfunction "4_4") (pintype "passive"))
      (node (ref "U5") (pin "26") (pinfunction "PB04/USART1-CTS/SPI0-NPCS3/TC-CLK2_26") (pintype "bidirectional"))
      (node (ref "U9") (pin "64") (pinfunction "IO_L3N_MOSI_CSI_B_MISO0_2_64") (pintype "bidirectional"))
    )
    (net (code "23") (name "FPGA_AUX2") (class "Default")
      (node (ref "CN18") (pin "3") (pinfunction "3_3") (pintype "passive"))
      (node (ref "U5") (pin "40") (pinfunction "PA19/XOUT0/PWM6/USART0-TXD/SPI0-MOSI/SSC-TXCLK_40") (pintype "bidirectional"))
      (node (ref "U9") (pin "48") (pinfunction "IO_L48P_D7_2_48") (pintype "bidirectional"))
    )
    (net (code "24") (name "FPGA_CLK") (class "Default")
      (node (ref "R32") (pin "2") (pinfunction "2_2") (pintype "passive"))
      (node (ref "U9") (pin "50") (pinfunction "IO_L31N_GCLK30_D15_2_50") (pintype "bidirectional"))
    )
    (net (code "25") (name "FPGA_CONF") (class "Default")
      (node (ref "U10") (pin "1") (pinfunction "A_1") (pintype "bidirectional"))
      (node (ref "U5") (pin "33") (pinfunction "PA13/PWM2/NMI/USART0-CLK/SSC-RXCLK_33") (pintype "bidirectional"))
    )
    (net (code "26") (name "FPGA_DONE") (class "Default")
      (node (ref "U5") (pin "31") (pinfunction "PA12/XOUT32/PWM1/TC-B2/USART0-CTS/USART1-TXD_31") (pintype "bidirectional"))
      (node (ref "U9") (pin "71") (pinfunction "DONE_2_71") (pintype "bidirectional"))
    )
    (net (code "27") (name "FPGA_TCK") (class "Default")
      (node (ref "P1") (pin "1") (pinfunction "P$1_1") (pintype "passive"))
      (node (ref "U9") (pin "109") (pinfunction "TCK_109") (pintype "bidirectional"))
    )
    (net (code "28") (name "FPGA_TDI") (class "Default")
      (node (ref "P2") (pin "1") (pinfunction "P$1_1") (pintype "passive"))
      (node (ref "U9") (pin "110") (pinfunction "TDI_110") (pintype "bidirectional"))
    )
    (net (code "29") (name "FPGA_TDO") (class "Default")
      (node (ref "P3") (pin "1") (pinfunction "P$1_1") (pintype "passive"))
      (node (ref "U9") (pin "106") (pinfunction "TDO_106") (pintype "bidirectional"))
    )
    (net (code "30") (name "FPGA_TMS") (class "Default")
      (node (ref "P4") (pin "1") (pinfunction "P$1_1") (pintype "passive"))
      (node (ref "U9") (pin "107") (pinfunction "TMS_107") (pintype "bidirectional"))
    )
    (net (code "31") (name "GND") (class "Default")
      (node (ref "C100") (pin "2") (pinfunction "2_2") (pintype "passive"))
      (node (ref "C101") (pin "2") (pinfunction "2_2") (pintype "passive"))
      (node (ref "C103") (pin "2") (pinfunction "2_2") (pintype "passive"))
      (node (ref "C107") (pin "2") (pinfunction "2_2") (pintype "passive"))
      (node (ref "C108") (pin "2") (pinfunction "2_2") (pintype "passive"))
      (node (ref "C109") (pin "2") (pinfunction "2_2") (pintype "passive"))
      (node (ref "C11") (pin "2") (pinfunction "2_2") (pintype "passive"))
      (node (ref "C110") (pin "N") (pinfunction "N_N") (pintype "passive"))
      (node (ref "C113") (pin "N") (pinfunction "N_N") (pintype "passive"))
      (node (ref "C114") (pin "2") (pinfunction "2_2") (pintype "passive"))
      (node (ref "C115") (pin "2") (pinfunction "2_2") (pintype "passive"))
      (node (ref "C116") (pin "2") (pinfunction "2_2") (pintype "passive"))
      (node (ref "C118") (pin "2") (pinfunction "2_2") (pintype "passive"))
      (node (ref "C12") (pin "2") (pinfunction "2_2") (pintype "passive"))
      (node (ref "C122") (pin "2") (pinfunction "2_2") (pintype "passive"))
      (node (ref "C123") (pin "2") (pinfunction "2_2") (pintype "passive"))
      (node (ref "C124") (pin "2") (pinfunction "2_2") (pintype "passive"))
      (node (ref "C125") (pin "N") (pinfunction "N_N") (pintype "passive"))
      (node (ref "C128") (pin "2") (pinfunction "2_2") (pintype "passive"))
      (node (ref "C129") (pin "2") (pinfunction "2_2") (pintype "passive"))
      (node (ref "C13") (pin "2") (pinfunction "2_2") (pintype "passive"))
      (node (ref "C130") (pin "2") (pinfunction "2_2") (pintype "passive"))
      (node (ref "C131") (pin "2") (pinfunction "2_2") (pintype "passive"))
      (node (ref "C132") (pin "2") (pinfunction "2_2") (pintype "passive"))
      (node (ref "C133") (pin "2") (pinfunction "2_2") (pintype "passive"))
      (node (ref "C140") (pin "2") (pinfunction "2_2") (pintype "passive"))
      (node (ref "C141") (pin "2") (pinfunction "2_2") (pintype "passive"))
      (node (ref "C149") (pin "N") (pinfunction "N_N") (pintype "passive"))
      (node (ref "C15") (pin "2") (pinfunction "2_2") (pintype "passive"))
      (node (ref "C150") (pin "2") (pinfunction "2_2") (pintype "passive"))
      (node (ref "C151") (pin "2") (pinfunction "2_2") (pintype "passive"))
      (node (ref "C152") (pin "2") (pinfunction "2_2") (pintype "passive"))
      (node (ref "C154") (pin "2") (pinfunction "2_2") (pintype "passive"))
      (node (ref "C158") (pin "2") (pinfunction "2_2") (pintype "passive"))
      (node (ref "C159") (pin "2") (pinfunction "2_2") (pintype "passive"))
      (node (ref "C16") (pin "2") (pinfunction "2_2") (pintype "passive"))
      (node (ref "C160") (pin "2") (pinfunction "2_2") (pintype "passive"))
      (node (ref "C161") (pin "N") (pinfunction "N_N") (pintype "passive"))
      (node (ref "C163") (pin "2") (pinfunction "2_2") (pintype "passive"))
      (node (ref "C17") (pin "2") (pinfunction "2_2") (pintype "passive"))
      (node (ref "C18") (pin "2") (pinfunction "2_2") (pintype "passive"))
      (node (ref "C19") (pin "2") (pinfunction "2_2") (pintype "passive"))
      (node (ref "C2") (pin "2") (pinfunction "2_2") (pintype "passive"))
      (node (ref "C20") (pin "2") (pinfunction "2_2") (pintype "passive"))
      (node (ref "C21") (pin "2") (pinfunction "2_2") (pintype "passive"))
      (node (ref "C22") (pin "2") (pinfunction "2_2") (pintype "passive"))
      (node (ref "C23") (pin "2") (pinfunction "2_2") (pintype "passive"))
      (node (ref "C25") (pin "2") (pinfunction "2_2") (pintype "passive"))
      (node (ref "C26") (pin "2") (pinfunction "2_2") (pintype "passive"))
      (node (ref "C27") (pin "2") (pinfunction "2_2") (pintype "passive"))
      (node (ref "C28") (pin "2") (pinfunction "2_2") (pintype "passive"))
      (node (ref "C29") (pin "2") (pinfunction "2_2") (pintype "passive"))
      (node (ref "C3") (pin "N") (pinfunction "N_N") (pintype "passive"))
      (node (ref "C30") (pin "2") (pinfunction "2_2") (pintype "passive"))
      (node (ref "C31") (pin "2") (pinfunction "2_2") (pintype "passive"))
      (node (ref "C32") (pin "2") (pinfunction "2_2") (pintype "passive"))
      (node (ref "C33") (pin "2") (pinfunction "2_2") (pintype "passive"))
      (node (ref "C34") (pin "2") (pinfunction "2_2") (pintype "passive"))
      (node (ref "C35") (pin "2") (pinfunction "2_2") (pintype "passive"))
      (node (ref "C37") (pin "2") (pinfunction "2_2") (pintype "passive"))
      (node (ref "C38") (pin "2") (pinfunction "2_2") (pintype "passive"))
      (node (ref "C39") (pin "2") (pinfunction "2_2") (pintype "passive"))
      (node (ref "C4") (pin "N") (pinfunction "N_N") (pintype "passive"))
      (node (ref "C40") (pin "2") (pinfunction "2_2") (pintype "passive"))
      (node (ref "C41") (pin "2") (pinfunction "2_2") (pintype "passive"))
      (node (ref "C43") (pin "2") (pinfunction "2_2") (pintype "passive"))
      (node (ref "C44") (pin "2") (pinfunction "2_2") (pintype "passive"))
      (node (ref "C45") (pin "2") (pinfunction "2_2") (pintype "passive"))
      (node (ref "C46") (pin "2") (pinfunction "2_2") (pintype "passive"))
      (node (ref "C47") (pin "2") (pinfunction "2_2") (pintype "passive"))
      (node (ref "C48") (pin "2") (pinfunction "2_2") (pintype "passive"))
      (node (ref "C49") (pin "2") (pinfunction "2_2") (pintype "passive"))
      (node (ref "C5") (pin "2") (pinfunction "2_2") (pintype "passive"))
      (node (ref "C50") (pin "2") (pinfunction "2_2") (pintype "passive"))
      (node (ref "C51") (pin "2") (pinfunction "2_2") (pintype "passive"))
      (node (ref "C52") (pin "2") (pinfunction "2_2") (pintype "passive"))
      (node (ref "C53") (pin "2") (pinfunction "2_2") (pintype "passive"))
      (node (ref "C54") (pin "2") (pinfunction "2_2") (pintype "passive"))
      (node (ref "C55") (pin "GND") (pinfunction "GND_GND") (pintype "passive"))
      (node (ref "C56") (pin "GND") (pinfunction "GND_GND") (pintype "passive"))
      (node (ref "C57") (pin "2") (pinfunction "2_2") (pintype "passive"))
      (node (ref "C58") (pin "GND") (pinfunction "GND_GND") (pintype "passive"))
      (node (ref "C59") (pin "2") (pinfunction "2_2") (pintype "passive"))
      (node (ref "C6") (pin "2") (pinfunction "2_2") (pintype "passive"))
      (node (ref "C60") (pin "GND") (pinfunction "GND_GND") (pintype "passive"))
      (node (ref "C61") (pin "2") (pinfunction "2_2") (pintype "passive"))
      (node (ref "C62") (pin "GND") (pinfunction "GND_GND") (pintype "passive"))
      (node (ref "C64") (pin "2") (pinfunction "2_2") (pintype "passive"))
      (node (ref "C65") (pin "2") (pinfunction "2_2") (pintype "passive"))
      (node (ref "C66") (pin "2") (pinfunction "2_2") (pintype "passive"))
      (node (ref "C67") (pin "2") (pinfunction "2_2") (pintype "passive"))
      (node (ref "C68") (pin "N") (pinfunction "N_N") (pintype "passive"))
      (node (ref "C69") (pin "2") (pinfunction "2_2") (pintype "passive"))
      (node (ref "C7") (pin "N") (pinfunction "N_N") (pintype "passive"))
      (node (ref "C70") (pin "2") (pinfunction "2_2") (pintype "passive"))
      (node (ref "C71") (pin "2") (pinfunction "2_2") (pintype "passive"))
      (node (ref "C73") (pin "2") (pinfunction "2_2") (pintype "passive"))
      (node (ref "C77") (pin "2") (pinfunction "2_2") (pintype "passive"))
      (node (ref "C78") (pin "2") (pinfunction "2_2") (pintype "passive"))
      (node (ref "C79") (pin "2") (pinfunction "2_2") (pintype "passive"))
      (node (ref "C8") (pin "2") (pinfunction "2_2") (pintype "passive"))
      (node (ref "C80") (pin "N") (pinfunction "N_N") (pintype "passive"))
      (node (ref "C83") (pin "N") (pinfunction "N_N") (pintype "passive"))
      (node (ref "C84") (pin "2") (pinfunction "2_2") (pintype "passive"))
      (node (ref "C85") (pin "2") (pinfunction "2_2") (pintype "passive"))
      (node (ref "C86") (pin "2") (pinfunction "2_2") (pintype "passive"))
      (node (ref "C88") (pin "2") (pinfunction "2_2") (pintype "passive"))
      (node (ref "C9") (pin "2") (pinfunction "2_2") (pintype "passive"))
      (node (ref "C92") (pin "2") (pinfunction "2_2") (pintype "passive"))
      (node (ref "C93") (pin "2") (pinfunction "2_2") (pintype "passive"))
      (node (ref "C94") (pin "2") (pinfunction "2_2") (pintype "passive"))
      (node (ref "C95") (pin "N") (pinfunction "N_N") (pintype "passive"))
      (node (ref "C98") (pin "N") (pinfunction "N_N") (pintype "passive"))
      (node (ref "C99") (pin "2") (pinfunction "2_2") (pintype "passive"))
      (node (ref "CN1") (pin "N") (pinfunction "N_N") (pintype "passive"))
      (node (ref "CN10") (pin "2") (pinfunction "2_2") (pintype "passive"))
      (node (ref "CN11") (pin "1.5") (pinfunction "GND_1.5") (pintype "bidirectional"))
      (node (ref "CN11") (pin "2.1") (pinfunction "GND_2.1") (pintype "bidirectional"))
      (node (ref "CN11") (pin "S1") (pinfunction "S1_S1") (pintype "bidirectional"))
      (node (ref "CN11") (pin "S2") (pinfunction "S2_S2") (pintype "bidirectional"))
      (node (ref "CN12") (pin "2") (pinfunction "2_2") (pintype "passive"))
      (node (ref "CN13") (pin "1.5") (pinfunction "GND_1.5") (pintype "bidirectional"))
      (node (ref "CN13") (pin "2.1") (pinfunction "GND_2.1") (pintype "bidirectional"))
      (node (ref "CN13") (pin "S1") (pinfunction "S1_S1") (pintype "bidirectional"))
      (node (ref "CN13") (pin "S2") (pinfunction "S2_S2") (pintype "bidirectional"))
      (node (ref "CN14") (pin "2") (pinfunction "2_2") (pintype "passive"))
      (node (ref "CN15") (pin "1.5") (pinfunction "GND_1.5") (pintype "bidirectional"))
      (node (ref "CN15") (pin "2.1") (pinfunction "GND_2.1") (pintype "bidirectional"))
      (node (ref "CN15") (pin "S1") (pinfunction "S1_S1") (pintype "bidirectional"))
      (node (ref "CN15") (pin "S2") (pinfunction "S2_S2") (pintype "bidirectional"))
      (node (ref "CN16") (pin "2") (pinfunction "2_2") (pintype "passive"))
      (node (ref "CN17") (pin "5") (pinfunction "5_5") (pintype "passive"))
      (node (ref "CN18") (pin "1") (pinfunction "1_1") (pintype "passive"))
      (node (ref "CN2") (pin "1") (pinfunction "1_1") (pintype "passive"))
      (node (ref "CN2") (pin "3") (pinfunction "3_3") (pintype "passive"))
      (node (ref "CN2") (pin "7") (pinfunction "7_7") (pintype "passive"))
      (node (ref "CN3") (pin "5") (pinfunction "GND_5") (pintype "passive"))
      (node (ref "CN3") (pin "S1") (pinfunction "S1_S1") (pintype "passive"))
      (node (ref "CN3") (pin "S2") (pinfunction "S2_S2") (pintype "passive"))
      (node (ref "CN4") (pin "10") (pinfunction "GND_10") (pintype "passive"))
      (node (ref "CN4") (pin "2") (pinfunction "GND_2") (pintype "passive"))
      (node (ref "CN5") (pin "4") (pinfunction "4_4") (pintype "passive"))
      (node (ref "CN6") (pin "8") (pinfunction "8_8") (pintype "passive"))
      (node (ref "CN7") (pin "10") (pinfunction "GND_10") (pintype "bidirectional"))
      (node (ref "CN8") (pin "2") (pinfunction "2_2") (pintype "passive"))
      (node (ref "CN9") (pin "1.5") (pinfunction "GND_1.5") (pintype "bidirectional"))
      (node (ref "CN9") (pin "2.1") (pinfunction "GND_2.1") (pintype "bidirectional"))
      (node (ref "CN9") (pin "S1") (pinfunction "S1_S1") (pintype "bidirectional"))
      (node (ref "CN9") (pin "S2") (pinfunction "S2_S2") (pintype "bidirectional"))
      (node (ref "D1") (pin "A") (pinfunction "A_A") (pintype "passive"))
      (node (ref "D2") (pin "A") (pinfunction "A_A") (pintype "passive"))
      (node (ref "D4") (pin "A") (pinfunction "A_A") (pintype "passive"))
      (node (ref "J1") (pin "1") (pinfunction "1_1") (pintype "passive"))
      (node (ref "J1") (pin "3") (pinfunction "3_3") (pintype "passive"))
      (node (ref "J1") (pin "5") (pinfunction "5_5") (pintype "passive"))
      (node (ref "J1") (pin "7") (pinfunction "7_7") (pintype "passive"))
      (node (ref "J1") (pin "9") (pinfunction "9_9") (pintype "passive"))
      (node (ref "LED1") (pin "K") (pinfunction "K_K") (pintype "passive"))
      (node (ref "LED10") (pin "K") (pinfunction "K_K") (pintype "passive"))
      (node (ref "LED2") (pin "K") (pinfunction "K_K") (pintype "passive"))
      (node (ref "LED4") (pin "K") (pinfunction "K_K") (pintype "passive"))
      (node (ref "LED5") (pin "K") (pinfunction "K_K") (pintype "passive"))
      (node (ref "LED6") (pin "K") (pinfunction "K_K") (pintype "passive"))
      (node (ref "LED7") (pin "K") (pinfunction "K_K") (pintype "passive"))
      (node (ref "LED8") (pin "K") (pinfunction "K_K") (pintype "passive"))
      (node (ref "LED9") (pin "K") (pinfunction "K_K") (pintype "passive"))
      (node (ref "R10") (pin "1") (pinfunction "1_1") (pintype "passive"))
      (node (ref "R105") (pin "1") (pinfunction "1_1") (pintype "passive"))
      (node (ref "R11") (pin "1") (pinfunction "1_1") (pintype "passive"))
      (node (ref "R110") (pin "1") (pinfunction "1_1") (pintype "passive"))
      (node (ref "R112") (pin "1") (pinfunction "1_1") (pintype "passive"))
      (node (ref "R118") (pin "1") (pinfunction "1_1") (pintype "passive"))
      (node (ref "R12") (pin "1") (pinfunction "1_1") (pintype "passive"))
      (node (ref "R15") (pin "1") (pinfunction "1_1") (pintype "passive"))
      (node (ref "R17") (pin "1") (pinfunction "1_1") (pintype "passive"))
      (node (ref "R19") (pin "1") (pinfunction "1_1") (pintype "passive"))
      (node (ref "R21") (pin "1") (pinfunction "1_1") (pintype "passive"))
      (node (ref "R22") (pin "1") (pinfunction "1_1") (pintype "passive"))
      (node (ref "R25") (pin "1") (pinfunction "1_1") (pintype "passive"))
      (node (ref "R26") (pin "1") (pinfunction "1_1") (pintype "passive"))
      (node (ref "R27") (pin "1") (pinfunction "1_1") (pintype "passive"))
      (node (ref "R28") (pin "1") (pinfunction "1_1") (pintype "passive"))
      (node (ref "R44") (pin "1") (pinfunction "1_1") (pintype "passive"))
      (node (ref "R5") (pin "1") (pinfunction "1_1") (pintype "passive"))
      (node (ref "R53") (pin "1") (pinfunction "1_1") (pintype "passive"))
      (node (ref "R60") (pin "1") (pinfunction "1_1") (pintype "passive"))
      (node (ref "R63") (pin "1") (pinfunction "1_1") (pintype "passive"))
      (node (ref "R67") (pin "1") (pinfunction "1_1") (pintype "passive"))
      (node (ref "R7") (pin "1") (pinfunction "1_1") (pintype "passive"))
      (node (ref "R71") (pin "1") (pinfunction "1_1") (pintype "passive"))
      (node (ref "R75") (pin "1") (pinfunction "1_1") (pintype "passive"))
      (node (ref "R78") (pin "1") (pinfunction "1_1") (pintype "passive"))
      (node (ref "R79") (pin "1") (pinfunction "1_1") (pintype "passive"))
      (node (ref "R80") (pin "1") (pinfunction "1_1") (pintype "passive"))
      (node (ref "R81") (pin "1") (pinfunction "1_1") (pintype "passive"))
      (node (ref "R82") (pin "1") (pinfunction "1_1") (pintype "passive"))
      (node (ref "R83") (pin "1") (pinfunction "1_1") (pintype "passive"))
      (node (ref "R84") (pin "1") (pinfunction "1_1") (pintype "passive"))
      (node (ref "R85") (pin "1") (pinfunction "1_1") (pintype "passive"))
      (node (ref "R86") (pin "1") (pinfunction "1_1") (pintype "passive"))
      (node (ref "R87") (pin "1") (pinfunction "1_1") (pintype "passive"))
      (node (ref "R88") (pin "1") (pinfunction "1_1") (pintype "passive"))
      (node (ref "R89") (pin "1") (pinfunction "1_1") (pintype "passive"))
      (node (ref "R90") (pin "1") (pinfunction "1_1") (pintype "passive"))
      (node (ref "R91") (pin "1") (pinfunction "1_1") (pintype "passive"))
      (node (ref "R92") (pin "1") (pinfunction "1_1") (pintype "passive"))
      (node (ref "R93") (pin "1") (pinfunction "1_1") (pintype "passive"))
      (node (ref "R94") (pin "1") (pinfunction "1_1") (pintype "passive"))
      (node (ref "R95") (pin "1") (pinfunction "1_1") (pintype "passive"))
      (node (ref "R96") (pin "1") (pinfunction "1_1") (pintype "passive"))
      (node (ref "R97") (pin "1") (pinfunction "1_1") (pintype "passive"))
      (node (ref "R98") (pin "1") (pinfunction "1_1") (pintype "passive"))
      (node (ref "SW2") (pin "A1") (pinfunction "A1_A1") (pintype "passive"))
      (node (ref "SW2") (pin "A2") (pinfunction "A2_A2") (pintype "passive"))
      (node (ref "SW3") (pin "A1") (pinfunction "A1_A1") (pintype "passive"))
      (node (ref "SW3") (pin "A2") (pinfunction "A2_A2") (pintype "passive"))
      (node (ref "U10") (pin "3") (pinfunction "GND_3") (pintype "bidirectional"))
      (node (ref "U11") (pin "7") (pinfunction "GND_7") (pintype "bidirectional"))
      (node (ref "U12") (pin "1") (pinfunction "R2_1") (pintype "bidirectional"))
      (node (ref "U13") (pin "2") (pinfunction "GND_2") (pintype "bidirectional"))
      (node (ref "U13") (pin "4") (pinfunction "GND_4") (pintype "bidirectional"))
      (node (ref "U14") (pin "23") (pinfunction "GND_C_23") (pintype "bidirectional"))
      (node (ref "U14") (pin "24") (pinfunction "GND_24") (pintype "bidirectional"))
      (node (ref "U14") (pin "25") (pinfunction "GND_25") (pintype "bidirectional"))
      (node (ref "U14") (pin "31") (pinfunction "GND_B_31") (pintype "bidirectional"))
      (node (ref "U14") (pin "32") (pinfunction "GND_A_32") (pintype "bidirectional"))
      (node (ref "U14") (pin "8") (pinfunction "GND_8") (pintype "bidirectional"))
      (node (ref "U17") (pin "23") (pinfunction "GND_C_23") (pintype "bidirectional"))
      (node (ref "U17") (pin "24") (pinfunction "GND_24") (pintype "bidirectional"))
      (node (ref "U17") (pin "25") (pinfunction "GND_25") (pintype "bidirectional"))
      (node (ref "U17") (pin "31") (pinfunction "GND_B_31") (pintype "bidirectional"))
      (node (ref "U17") (pin "32") (pinfunction "GND_A_32") (pintype "bidirectional"))
      (node (ref "U17") (pin "8") (pinfunction "GND_8") (pintype "bidirectional"))
      (node (ref "U2") (pin "10") (pinfunction "GND_10") (pintype "bidirectional"))
      (node (ref "U2") (pin "18") (pinfunction "GND_18") (pintype "bidirectional"))
      (node (ref "U2") (pin "27") (pinfunction "GND_27") (pintype "bidirectional"))
      (node (ref "U2") (pin "PAD") (pinfunction "PAD_PAD") (pintype "bidirectional"))
      (node (ref "U20") (pin "23") (pinfunction "GND_C_23") (pintype "bidirectional"))
      (node (ref "U20") (pin "24") (pinfunction "GND_24") (pintype "bidirectional"))
      (node (ref "U20") (pin "25") (pinfunction "GND_25") (pintype "bidirectional"))
      (node (ref "U20") (pin "31") (pinfunction "GND_B_31") (pintype "bidirectional"))
      (node (ref "U20") (pin "32") (pinfunction "GND_A_32") (pintype "bidirectional"))
      (node (ref "U20") (pin "8") (pinfunction "GND_8") (pintype "bidirectional"))
      (node (ref "U23") (pin "23") (pinfunction "GND_C_23") (pintype "bidirectional"))
      (node (ref "U23") (pin "24") (pinfunction "GND_24") (pintype "bidirectional"))
      (node (ref "U23") (pin "25") (pinfunction "GND_25") (pintype "bidirectional"))
      (node (ref "U23") (pin "31") (pinfunction "GND_B_31") (pintype "bidirectional"))
      (node (ref "U23") (pin "32") (pinfunction "GND_A_32") (pintype "bidirectional"))
      (node (ref "U23") (pin "8") (pinfunction "GND_8") (pintype "bidirectional"))
      (node (ref "U26") (pin "10") (pinfunction "SI_10") (pintype "bidirectional"))
      (node (ref "U26") (pin "13") (pinfunction "C_13") (pintype "bidirectional"))
      (node (ref "U26") (pin "14") (pinfunction "D_14") (pintype "bidirectional"))
      (node (ref "U26") (pin "15") (pinfunction "CKINH_15") (pintype "bidirectional"))
      (node (ref "U26") (pin "3") (pinfunction "E_3") (pintype "bidirectional"))
      (node (ref "U26") (pin "8") (pinfunction "GND_8") (pintype "bidirectional"))
      (node (ref "U27") (pin "15") (pinfunction "CKINH_15") (pintype "bidirectional"))
      (node (ref "U27") (pin "5") (pinfunction "G_5") (pintype "bidirectional"))
      (node (ref "U27") (pin "6") (pinfunction "H_6") (pintype "bidirectional"))
      (node (ref "U27") (pin "8") (pinfunction "GND_8") (pintype "bidirectional"))
      (node (ref "U3") (pin "2") (pinfunction "GND_2") (pintype "bidirectional"))
      (node (ref "U30") (pin "10") (pinfunction "SI_10") (pintype "bidirectional"))
      (node (ref "U30") (pin "13") (pinfunction "C_13") (pintype "bidirectional"))
      (node (ref "U30") (pin "14") (pinfunction "D_14") (pintype "bidirectional"))
      (node (ref "U30") (pin "15") (pinfunction "CKINH_15") (pintype "bidirectional"))
      (node (ref "U30") (pin "8") (pinfunction "GND_8") (pintype "bidirectional"))
      (node (ref "U31") (pin "15") (pinfunction "CKINH_15") (pintype "bidirectional"))
      (node (ref "U31") (pin "8") (pinfunction "GND_8") (pintype "bidirectional"))
      (node (ref "U34") (pin "1") (pinfunction "R2_1") (pintype "bidirectional"))
      (node (ref "U35") (pin "1") (pinfunction "R2_1") (pintype "bidirectional"))
      (node (ref "U37") (pin "23") (pinfunction "GND_C_23") (pintype "bidirectional"))
      (node (ref "U37") (pin "24") (pinfunction "GND_24") (pintype "bidirectional"))
      (node (ref "U37") (pin "25") (pinfunction "GND_25") (pintype "bidirectional"))
      (node (ref "U37") (pin "31") (pinfunction "GND_B_31") (pintype "bidirectional"))
      (node (ref "U37") (pin "32") (pinfunction "GND_A_32") (pintype "bidirectional"))
      (node (ref "U37") (pin "8") (pinfunction "GND_8") (pintype "bidirectional"))
      (node (ref "U39") (pin "2") (pinfunction "GND_2") (pintype "bidirectional"))
      (node (ref "U4") (pin "2") (pinfunction "V-_2") (pintype "bidirectional"))
      (node (ref "U5") (pin "1") (pinfunction "GND_1") (pintype "bidirectional"))
      (node (ref "U5") (pin "17") (pinfunction "GNDANA_17") (pintype "bidirectional"))
      (node (ref "U5") (pin "23") (pinfunction "GND_23") (pintype "bidirectional"))
      (node (ref "U5") (pin "49") (pinfunction "GND_49") (pintype "bidirectional"))
      (node (ref "U7") (pin "4") (pinfunction "GND_4") (pintype "bidirectional"))
      (node (ref "U8") (pin "3") (pinfunction "GND_3") (pintype "bidirectional"))
      (node (ref "U9") (pin "108") (pinfunction "GND_108") (pintype "bidirectional"))
      (node (ref "U9") (pin "113") (pinfunction "GND_113") (pintype "bidirectional"))
      (node (ref "U9") (pin "13") (pinfunction "GND_13") (pintype "bidirectional"))
      (node (ref "U9") (pin "130") (pinfunction "GND_130") (pintype "bidirectional"))
      (node (ref "U9") (pin "136") (pinfunction "GND_136") (pintype "bidirectional"))
      (node (ref "U9") (pin "25") (pinfunction "GND_25") (pintype "bidirectional"))
      (node (ref "U9") (pin "3") (pinfunction "GND_3") (pintype "bidirectional"))
      (node (ref "U9") (pin "49") (pinfunction "GND_49") (pintype "bidirectional"))
      (node (ref "U9") (pin "54") (pinfunction "GND_54") (pintype "bidirectional"))
      (node (ref "U9") (pin "68") (pinfunction "GND_68") (pintype "bidirectional"))
      (node (ref "U9") (pin "73") (pinfunction "SUSPEND_73") (pintype "bidirectional"))
      (node (ref "U9") (pin "77") (pinfunction "GND_77") (pintype "bidirectional"))
      (node (ref "U9") (pin "91") (pinfunction "GND_91") (pintype "bidirectional"))
      (node (ref "U9") (pin "96") (pinfunction "GND_96") (pintype "bidirectional"))
      (node (ref "X1") (pin "2") (pinfunction "GND_2") (pintype "bidirectional"))
    )
    (net (code "32") (name "LED1") (class "Default")
      (node (ref "R40") (pin "2") (pinfunction "2_2") (pintype "passive"))
      (node (ref "U5") (pin "24") (pinfunction "PB02/TC-A1/USART1-TXD_24") (pintype "bidirectional"))
    )
    (net (code "33") (name "LED2") (class "Default")
      (node (ref "R41") (pin "2") (pinfunction "2_2") (pintype "passive"))
      (node (ref "U5") (pin "25") (pinfunction "PB03/TC-B1/USART1-RXD_25") (pintype "bidirectional"))
    )
    (net (code "34") (name "LED_CLK") (class "Default")
      (node (ref "U11") (pin "8") (pinfunction "CK_8") (pintype "bidirectional"))
      (node (ref "U9") (pin "131") (pinfunction "IO_L35N_GCLK16_0_131") (pintype "bidirectional"))
    )
    (net (code "35") (name "LED_DO") (class "Default")
      (node (ref "U11") (pin "2") (pinfunction "B_2") (pintype "bidirectional"))
      (node (ref "U9") (pin "126") (pinfunction "IO_L36N_GCLK14_0_126") (pintype "bidirectional"))
    )
    (net (code "36") (name "MCU_CLK") (class "Default")
      (node (ref "R31") (pin "2") (pinfunction "2_2") (pintype "passive"))
      (node (ref "U5") (pin "41") (pinfunction "PA28/XIN1/USART0-CLK/PWM4/SPI0-MISO/ABDAC-DATAN0_41") (pintype "bidirectional"))
    )
    (net (code "37") (name "MOT1_2_CLK") (class "Default")
      (node (ref "U26") (pin "2") (pinfunction "CK_2") (pintype "bidirectional"))
      (node (ref "U27") (pin "2") (pinfunction "CK_2") (pintype "bidirectional"))
      (node (ref "U9") (pin "94") (pinfunction "IO_L40N_GCLK10_1_94") (pintype "bidirectional"))
    )
    (net (code "38") (name "MOT1_2_EN_SENSOR") (class "Default")
      (node (ref "R110") (pin "2") (pinfunction "2_2") (pintype "passive"))
      (node (ref "U34") (pin "5") (pinfunction "EN_5") (pintype "bidirectional"))
      (node (ref "U9") (pin "84") (pinfunction "IO_L43N_GCLK4_1_84") (pintype "bidirectional"))
    )
    (net (code "39") (name "MOT1_A_5") (class "Default")
      (node (ref "CN10") (pin "3") (pinfunction "3_3") (pintype "passive"))
      (node (ref "R78") (pin "2") (pinfunction "2_2") (pintype "passive"))
      (node (ref "U26") (pin "12") (pinfunction "B_12") (pintype "bidirectional"))
    )
    (net (code "40") (name "MOT1_B_5") (class "Default")
      (node (ref "CN10") (pin "1") (pinfunction "1_1") (pintype "passive"))
      (node (ref "R79") (pin "2") (pinfunction "2_2") (pintype "passive"))
      (node (ref "U26") (pin "11") (pinfunction "A_11") (pintype "bidirectional"))
    )
    (net (code "41") (name "MOT1_GND") (class "Default")
      (node (ref "C72") (pin "2") (pinfunction "2_2") (pintype "passive"))
      (node (ref "R62") (pin "1") (pinfunction "1_1") (pintype "passive"))
      (node (ref "R63") (pin "2") (pinfunction "2_2") (pintype "passive"))
      (node (ref "U14") (pin "12") (pinfunction "M2_12") (pintype "bidirectional"))
      (node (ref "U14") (pin "9") (pinfunction "AGND_9") (pintype "bidirectional"))
    )
    (net (code "42") (name "MOT1_OUT_U") (class "Default")
      (node (ref "C74") (pin "2") (pinfunction "2_2") (pintype "passive"))
      (node (ref "CN9") (pin "1.10") (pinfunction "U_1.10") (pintype "bidirectional"))
      (node (ref "CN9") (pin "1.11") (pinfunction "U_1.11") (pintype "bidirectional"))
      (node (ref "CN9") (pin "2.5") (pinfunction "U_2.5") (pintype "bidirectional"))
      (node (ref "U14") (pin "33") (pinfunction "OUT_A_33") (pintype "bidirectional"))
    )
    (net (code "43") (name "MOT1_OUT_V") (class "Default")
      (node (ref "C75") (pin "2") (pinfunction "2_2") (pintype "passive"))
      (node (ref "CN9") (pin "1.8") (pinfunction "V_1.8") (pintype "bidirectional"))
      (node (ref "CN9") (pin "1.9") (pinfunction "V_1.9") (pintype "bidirectional"))
      (node (ref "CN9") (pin "2.6") (pinfunction "V_2.6") (pintype "bidirectional"))
      (node (ref "U14") (pin "30") (pinfunction "OUT_B_30") (pintype "bidirectional"))
    )
    (net (code "44") (name "MOT1_OUT_W") (class "Default")
      (node (ref "C76") (pin "2") (pinfunction "2_2") (pintype "passive"))
      (node (ref "CN9") (pin "1.6") (pinfunction "W_1.6") (pintype "bidirectional"))
      (node (ref "CN9") (pin "1.7") (pinfunction "W_1.7") (pintype "bidirectional"))
      (node (ref "CN9") (pin "2.7") (pinfunction "W_2.7") (pintype "bidirectional"))
      (node (ref "U14") (pin "22") (pinfunction "OUT_C_22") (pintype "bidirectional"))
    )
    (net (code "45") (name "MOT1_PWM_A") (class "Default")
      (node (ref "RA2") (pin "C1") (pinfunction "1_C1") (pintype "passive"))
      (node (ref "U9") (pin "102") (pinfunction "IO_L32P_1_102") (pintype "bidirectional"))
    )
    (net (code "46") (name "MOT1_PWM_B") (class "Default")
      (node (ref "RA3") (pin "A1") (pinfunction "1_A1") (pintype "passive"))
      (node (ref "U9") (pin "100") (pinfunction "IO_L33P_1_100") (pintype "bidirectional"))
    )
    (net (code "47") (name "MOT1_PWM_C") (class "Default")
      (node (ref "RA3") (pin "D1") (pinfunction "1_D1") (pintype "passive"))
      (node (ref "U9") (pin "97") (pinfunction "IO_L34N_1_97") (pintype "bidirectional"))
    )
    (net (code "48") (name "MOT2_A_5") (class "Default")
      (node (ref "CN12") (pin "3") (pinfunction "3_3") (pintype "passive"))
      (node (ref "R83") (pin "2") (pinfunction "2_2") (pintype "passive"))
      (node (ref "U27") (pin "4") (pinfunction "F_4") (pintype "bidirectional"))
    )
    (net (code "49") (name "MOT2_B_5") (class "Default")
      (node (ref "CN12") (pin "1") (pinfunction "1_1") (pintype "passive"))
      (node (ref "R84") (pin "2") (pinfunction "2_2") (pintype "passive"))
      (node (ref "U27") (pin "3") (pinfunction "E_3") (pintype "bidirectional"))
    )
    (net (code "50") (name "MOT2_GND") (class "Default")
      (node (ref "C87") (pin "2") (pinfunction "2_2") (pintype "passive"))
      (node (ref "R66") (pin "1") (pinfunction "1_1") (pintype "passive"))
      (node (ref "R67") (pin "2") (pinfunction "2_2") (pintype "passive"))
      (node (ref "U17") (pin "12") (pinfunction "M2_12") (pintype "bidirectional"))
      (node (ref "U17") (pin "9") (pinfunction "AGND_9") (pintype "bidirectional"))
    )
    (net (code "51") (name "MOT2_OUT_U") (class "Default")
      (node (ref "C89") (pin "2") (pinfunction "2_2") (pintype "passive"))
      (node (ref "CN11") (pin "1.10") (pinfunction "U_1.10") (pintype "bidirectional"))
      (node (ref "CN11") (pin "1.11") (pinfunction "U_1.11") (pintype "bidirectional"))
      (node (ref "CN11") (pin "2.5") (pinfunction "U_2.5") (pintype "bidirectional"))
      (node (ref "U17") (pin "33") (pinfunction "OUT_A_33") (pintype "bidirectional"))
    )
    (net (code "52") (name "MOT2_OUT_V") (class "Default")
      (node (ref "C90") (pin "2") (pinfunction "2_2") (pintype "passive"))
      (node (ref "CN11") (pin "1.8") (pinfunction "V_1.8") (pintype "bidirectional"))
      (node (ref "CN11") (pin "1.9") (pinfunction "V_1.9") (pintype "bidirectional"))
      (node (ref "CN11") (pin "2.6") (pinfunction "V_2.6") (pintype "bidirectional"))
      (node (ref "U17") (pin "30") (pinfunction "OUT_B_30") (pintype "bidirectional"))
    )
    (net (code "53") (name "MOT2_OUT_W") (class "Default")
      (node (ref "C91") (pin "2") (pinfunction "2_2") (pintype "passive"))
      (node (ref "CN11") (pin "1.6") (pinfunction "W_1.6") (pintype "bidirectional"))
      (node (ref "CN11") (pin "1.7") (pinfunction "W_1.7") (pintype "bidirectional"))
      (node (ref "CN11") (pin "2.7") (pinfunction "W_2.7") (pintype "bidirectional"))
      (node (ref "U17") (pin "22") (pinfunction "OUT_C_22") (pintype "bidirectional"))
    )
    (net (code "54") (name "MOT2_PWM_A") (class "Default")
      (node (ref "RA4") (pin "C1") (pinfunction "1_C1") (pintype "passive"))
      (node (ref "U9") (pin "81") (pinfunction "IO_L46P_1_81") (pintype "bidirectional"))
    )
    (net (code "55") (name "MOT2_PWM_B") (class "Default")
      (node (ref "RA5") (pin "A1") (pinfunction "1_A1") (pintype "passive"))
      (node (ref "U9") (pin "79") (pinfunction "IO_L47P_1_79") (pintype "bidirectional"))
    )
    (net (code "56") (name "MOT2_PWM_C") (class "Default")
      (node (ref "RA5") (pin "D1") (pinfunction "1_D1") (pintype "passive"))
      (node (ref "U9") (pin "74") (pinfunction "IO_L74N_DOUT_BUSY_1_74") (pintype "bidirectional"))
    )
    (net (code "57") (name "MOT2_TEMP") (class "Default")
      (node (ref "U39") (pin "3") (pinfunction "VOUT_3") (pintype "bidirectional"))
      (node (ref "U5") (pin "15") (pinfunction "PA30/AD6/GCLK2_15") (pintype "bidirectional"))
    )
    (net (code "58") (name "MOT3_4_5_CLK") (class "Default")
      (node (ref "U30") (pin "2") (pinfunction "CK_2") (pintype "bidirectional"))
      (node (ref "U31") (pin "2") (pinfunction "CK_2") (pintype "bidirectional"))
      (node (ref "U9") (pin "22") (pinfunction "IO_L42P_GCLK25_TRDY2_3_22") (pintype "bidirectional"))
    )
    (net (code "59") (name "MOT3_4_5_EN_SENSOR") (class "Default")
      (node (ref "R112") (pin "2") (pinfunction "2_2") (pintype "passive"))
      (node (ref "U35") (pin "5") (pinfunction "EN_5") (pintype "bidirectional"))
      (node (ref "U9") (pin "12") (pinfunction "IO_L49P_3_12") (pintype "bidirectional"))
    )
    (net (code "60") (name "MOT3_A_5") (class "Default")
      (node (ref "CN14") (pin "3") (pinfunction "3_3") (pintype "passive"))
      (node (ref "R88") (pin "2") (pinfunction "2_2") (pintype "passive"))
      (node (ref "U30") (pin "12") (pinfunction "B_12") (pintype "bidirectional"))
    )
    (net (code "61") (name "MOT3_B_5") (class "Default")
      (node (ref "CN14") (pin "1") (pinfunction "1_1") (pintype "passive"))
      (node (ref "R89") (pin "2") (pinfunction "2_2") (pintype "passive"))
      (node (ref "U30") (pin "11") (pinfunction "A_11") (pintype "bidirectional"))
    )
    (net (code "62") (name "MOT3_GND") (class "Default")
      (node (ref "C102") (pin "2") (pinfunction "2_2") (pintype "passive"))
      (node (ref "R70") (pin "1") (pinfunction "1_1") (pintype "passive"))
      (node (ref "R71") (pin "2") (pinfunction "2_2") (pintype "passive"))
      (node (ref "U20") (pin "12") (pinfunction "M2_12") (pintype "bidirectional"))
      (node (ref "U20") (pin "9") (pinfunction "AGND_9") (pintype "bidirectional"))
    )
    (net (code "63") (name "MOT3_OUT_U") (class "Default")
      (node (ref "C104") (pin "2") (pinfunction "2_2") (pintype "passive"))
      (node (ref "CN13") (pin "1.10") (pinfunction "U_1.10") (pintype "bidirectional"))
      (node (ref "CN13") (pin "1.11") (pinfunction "U_1.11") (pintype "bidirectional"))
      (node (ref "CN13") (pin "2.5") (pinfunction "U_2.5") (pintype "bidirectional"))
      (node (ref "U20") (pin "33") (pinfunction "OUT_A_33") (pintype "bidirectional"))
    )
    (net (code "64") (name "MOT3_OUT_V") (class "Default")
      (node (ref "C105") (pin "2") (pinfunction "2_2") (pintype "passive"))
      (node (ref "CN13") (pin "1.8") (pinfunction "V_1.8") (pintype "bidirectional"))
      (node (ref "CN13") (pin "1.9") (pinfunction "V_1.9") (pintype "bidirectional"))
      (node (ref "CN13") (pin "2.6") (pinfunction "V_2.6") (pintype "bidirectional"))
      (node (ref "U20") (pin "30") (pinfunction "OUT_B_30") (pintype "bidirectional"))
    )
    (net (code "65") (name "MOT3_OUT_W") (class "Default")
      (node (ref "C106") (pin "2") (pinfunction "2_2") (pintype "passive"))
      (node (ref "CN13") (pin "1.6") (pinfunction "W_1.6") (pintype "bidirectional"))
      (node (ref "CN13") (pin "1.7") (pinfunction "W_1.7") (pintype "bidirectional"))
      (node (ref "CN13") (pin "2.7") (pinfunction "W_2.7") (pintype "bidirectional"))
      (node (ref "U20") (pin "22") (pinfunction "OUT_C_22") (pintype "bidirectional"))
    )
    (net (code "66") (name "MOT3_PWM_A") (class "Default")
      (node (ref "RA6") (pin "C1") (pinfunction "1_C1") (pintype "passive"))
      (node (ref "U9") (pin "32") (pinfunction "IO_L2N_3_32") (pintype "bidirectional"))
    )
    (net (code "67") (name "MOT3_PWM_B") (class "Default")
      (node (ref "RA7") (pin "A1") (pinfunction "1_A1") (pintype "passive"))
      (node (ref "U9") (pin "29") (pinfunction "IO_L36N_3_29") (pintype "bidirectional"))
    )
    (net (code "68") (name "MOT3_PWM_C") (class "Default")
      (node (ref "RA7") (pin "D1") (pinfunction "1_D1") (pintype "passive"))
      (node (ref "U9") (pin "24") (pinfunction "IO_L41P_GCLK27_3_24") (pintype "bidirectional"))
    )
    (net (code "69") (name "MOT4_A_5") (class "Default")
      (node (ref "CN16") (pin "3") (pinfunction "3_3") (pintype "passive"))
      (node (ref "R93") (pin "2") (pinfunction "2_2") (pintype "passive"))
      (node (ref "U31") (pin "4") (pinfunction "F_4") (pintype "bidirectional"))
    )
    (net (code "70") (name "MOT4_B_5") (class "Default")
      (node (ref "CN16") (pin "1") (pinfunction "1_1") (pintype "passive"))
      (node (ref "R94") (pin "2") (pinfunction "2_2") (pintype "passive"))
      (node (ref "U31") (pin "3") (pinfunction "E_3") (pintype "bidirectional"))
    )
    (net (code "71") (name "MOT4_GND") (class "Default")
      (node (ref "C117") (pin "2") (pinfunction "2_2") (pintype "passive"))
      (node (ref "R74") (pin "1") (pinfunction "1_1") (pintype "passive"))
      (node (ref "R75") (pin "2") (pinfunction "2_2") (pintype "passive"))
      (node (ref "U23") (pin "12") (pinfunction "M2_12") (pintype "bidirectional"))
      (node (ref "U23") (pin "9") (pinfunction "AGND_9") (pintype "bidirectional"))
    )
    (net (code "72") (name "MOT4_OUT_U") (class "Default")
      (node (ref "C119") (pin "2") (pinfunction "2_2") (pintype "passive"))
      (node (ref "CN15") (pin "1.10") (pinfunction "U_1.10") (pintype "bidirectional"))
      (node (ref "CN15") (pin "1.11") (pinfunction "U_1.11") (pintype "bidirectional"))
      (node (ref "CN15") (pin "2.5") (pinfunction "U_2.5") (pintype "bidirectional"))
      (node (ref "U23") (pin "33") (pinfunction "OUT_A_33") (pintype "bidirectional"))
    )
    (net (code "73") (name "MOT4_OUT_V") (class "Default")
      (node (ref "C120") (pin "2") (pinfunction "2_2") (pintype "passive"))
      (node (ref "CN15") (pin "1.8") (pinfunction "V_1.8") (pintype "bidirectional"))
      (node (ref "CN15") (pin "1.9") (pinfunction "V_1.9") (pintype "bidirectional"))
      (node (ref "CN15") (pin "2.6") (pinfunction "V_2.6") (pintype "bidirectional"))
      (node (ref "U23") (pin "30") (pinfunction "OUT_B_30") (pintype "bidirectional"))
    )
    (net (code "74") (name "MOT4_OUT_W") (class "Default")
      (node (ref "C121") (pin "2") (pinfunction "2_2") (pintype "passive"))
      (node (ref "CN15") (pin "1.6") (pinfunction "W_1.6") (pintype "bidirectional"))
      (node (ref "CN15") (pin "1.7") (pinfunction "W_1.7") (pintype "bidirectional"))
      (node (ref "CN15") (pin "2.7") (pinfunction "W_2.7") (pintype "bidirectional"))
      (node (ref "U23") (pin "22") (pinfunction "OUT_C_22") (pintype "bidirectional"))
    )
    (net (code "75") (name "MOT4_PWM_A") (class "Default")
      (node (ref "RA8") (pin "C1") (pinfunction "1_C1") (pintype "passive"))
      (node (ref "U9") (pin "9") (pinfunction "IO_L50N_3_9") (pintype "bidirectional"))
    )
    (net (code "76") (name "MOT4_PWM_B") (class "Default")
      (node (ref "RA9") (pin "A1") (pinfunction "1_A1") (pintype "passive"))
      (node (ref "U9") (pin "7") (pinfunction "IO_L51N_3_7") (pintype "bidirectional"))
    )
    (net (code "77") (name "MOT4_PWM_C") (class "Default")
      (node (ref "RA9") (pin "D1") (pinfunction "1_D1") (pintype "passive"))
      (node (ref "U9") (pin "2") (pinfunction "IO_L83P_3_2") (pintype "bidirectional"))
    )
    (net (code "78") (name "MOT5_GND") (class "Default")
      (node (ref "C153") (pin "2") (pinfunction "2_2") (pintype "passive"))
      (node (ref "R117") (pin "1") (pinfunction "1_1") (pintype "passive"))
      (node (ref "R118") (pin "2") (pinfunction "2_2") (pintype "passive"))
      (node (ref "U37") (pin "12") (pinfunction "M2_12") (pintype "bidirectional"))
      (node (ref "U37") (pin "9") (pinfunction "AGND_9") (pintype "bidirectional"))
    )
    (net (code "79") (name "MOT5_OUT_U") (class "Default")
      (node (ref "C155") (pin "2") (pinfunction "2_2") (pintype "passive"))
      (node (ref "CN17") (pin "1") (pinfunction "1_1") (pintype "passive"))
      (node (ref "U37") (pin "33") (pinfunction "OUT_A_33") (pintype "bidirectional"))
    )
    (net (code "80") (name "MOT5_OUT_V") (class "Default")
      (node (ref "C156") (pin "2") (pinfunction "2_2") (pintype "passive"))
      (node (ref "CN17") (pin "2") (pinfunction "2_2") (pintype "passive"))
      (node (ref "U37") (pin "30") (pinfunction "OUT_B_30") (pintype "bidirectional"))
    )
    (net (code "81") (name "MOT5_OUT_W") (class "Default")
      (node (ref "C157") (pin "2") (pinfunction "2_2") (pintype "passive"))
      (node (ref "CN17") (pin "3") (pinfunction "3_3") (pintype "passive"))
      (node (ref "U37") (pin "22") (pinfunction "OUT_C_22") (pintype "bidirectional"))
    )
    (net (code "82") (name "MOT5_PWM_A") (class "Default")
      (node (ref "RA10") (pin "C1") (pinfunction "1_C1") (pintype "passive"))
      (node (ref "U9") (pin "140") (pinfunction "IO_L3P_0_140") (pintype "bidirectional"))
    )
    (net (code "83") (name "MOT5_PWM_B") (class "Default")
      (node (ref "RA11") (pin "A1") (pinfunction "1_A1") (pintype "passive"))
      (node (ref "U9") (pin "138") (pinfunction "IO_L4P_0_138") (pintype "bidirectional"))
    )
    (net (code "84") (name "MOT5_PWM_C") (class "Default")
      (node (ref "RA11") (pin "D1") (pinfunction "1_D1") (pintype "passive"))
      (node (ref "U9") (pin "133") (pinfunction "IO_L34N_GCLK18_0_133") (pintype "bidirectional"))
    )
    (net (code "85") (name "Net-(C10-Pad2)") (class "Default")
      (node (ref "C10") (pin "2") (pinfunction "2_2") (pintype "passive"))
      (node (ref "C11") (pin "1") (pinfunction "1_1") (pintype "passive"))
      (node (ref "C13") (pin "1") (pinfunction "1_1") (pintype "passive"))
      (node (ref "C7") (pin "P") (pinfunction "P_P") (pintype "passive"))
      (node (ref "C9") (pin "1") (pinfunction "1_1") (pintype "passive"))
      (node (ref "D3") (pin "K") (pinfunction "K_K") (pintype "passive"))
      (node (ref "D4") (pin "K") (pinfunction "K_K") (pintype "passive"))
      (node (ref "L1") (pin "1") (pinfunction "1_1") (pintype "passive"))
      (node (ref "R9") (pin "2") (pinfunction "2_2") (pintype "passive"))
      (node (ref "U2") (pin "11") (pinfunction "VIN_11") (pintype "bidirectional"))
      (node (ref "U2") (pin "26") (pinfunction "VIN_26") (pintype "bidirectional"))
      (node (ref "U2") (pin "28") (pinfunction "VIN_28") (pintype "bidirectional"))
      (node (ref "U2") (pin "9") (pinfunction "VIN_9") (pintype "bidirectional"))
    )
    (net (code "86") (name "Net-(C14-Pad1)") (class "Default")
      (node (ref "C14") (pin "1") (pinfunction "1_1") (pintype "passive"))
      (node (ref "R13") (pin "1") (pinfunction "1_1") (pintype "passive"))
    )
    (net (code "87") (name "Net-(C55-Pad1)") (class "Default")
      (node (ref "C55") (pin "1") (pinfunction "1_1") (pintype "passive"))
      (node (ref "U9") (pin "128") (pinfunction "VCCINT_128") (pintype "bidirectional"))
    )
    (net (code "88") (name "Net-(C56-Pad1)") (class "Default")
      (node (ref "C56") (pin "1") (pinfunction "1_1") (pintype "passive"))
      (node (ref "U9") (pin "89") (pinfunction "VCCINT_89") (pintype "bidirectional"))
    )
    (net (code "89") (name "Net-(C58-Pad1)") (class "Default")
      (node (ref "C58") (pin "1") (pinfunction "1_1") (pintype "passive"))
      (node (ref "U9") (pin "52") (pinfunction "VCCINT_52") (pintype "bidirectional"))
    )
    (net (code "90") (name "Net-(C60-Pad1)") (class "Default")
      (node (ref "C60") (pin "1") (pinfunction "1_1") (pintype "passive"))
      (node (ref "U9") (pin "28") (pinfunction "VCCINT_28") (pintype "bidirectional"))
    )
    (net (code "91") (name "Net-(C62-Pad1)") (class "Default")
      (node (ref "C62") (pin "1") (pinfunction "1_1") (pintype "passive"))
      (node (ref "U9") (pin "19") (pinfunction "VCCINT_19") (pintype "bidirectional"))
    )
    (net (code "92") (name "Net-(C166-Pad1)") (class "Default")
      (node (ref "C166") (pin "1") (pinfunction "1_1") (pintype "passive"))
      (node (ref "F2") (pin "1") (pinfunction "1_1") (pintype "passive"))
      (node (ref "Q3") (pin "5") (pinfunction "D_5") (pintype "passive"))
      (node (ref "Q3") (pin "6") (pinfunction "D_6") (pintype "passive"))
      (node (ref "Q3") (pin "7") (pinfunction "D_7") (pintype "passive"))
      (node (ref "Q3") (pin "8") (pinfunction "D_8") (pintype "passive"))
    )
    (net (code "93") (name "Net-(C167-Pad1)") (class "Default")
      (node (ref "C167") (pin "1") (pinfunction "1_1") (pintype "passive"))
      (node (ref "F3") (pin "1") (pinfunction "1_1") (pintype "passive"))
      (node (ref "Q4") (pin "5") (pinfunction "D_5") (pintype "passive"))
      (node (ref "Q4") (pin "6") (pinfunction "D_6") (pintype "passive"))
      (node (ref "Q4") (pin "7") (pinfunction "D_7") (pintype "passive"))
      (node (ref "Q4") (pin "8") (pinfunction "D_8") (pintype "passive"))
    )
    (net (code "94") (name "Net-(CN1-PadP)") (class "Default")
      (node (ref "CN1") (pin "P") (pinfunction "P_P") (pintype "passive"))
      (node (ref "F1") (pin "1") (pinfunction "1_1") (pintype "passive"))
    )
    (net (code "95") (name "Net-(CN3-D+)") (class "Default")
      (node (ref "CN3") (pin "3") (pinfunction "D+_3") (pintype "passive"))
      (node (ref "U4") (pin "1") (pinfunction "O1_1") (pintype "bidirectional"))
    )
    (net (code "96") (name "Net-(CN3-D-)") (class "Default")
      (node (ref "CN3") (pin "2") (pinfunction "D-_2") (pintype "passive"))
      (node (ref "U4") (pin "6") (pinfunction "O2_6") (pintype "bidirectional"))
    )
    (net (code "97") (name "Net-(CN3-VBUS)") (class "Default")
      (node (ref "C22") (pin "1") (pinfunction "1_1") (pintype "passive"))
      (node (ref "CN3") (pin "1") (pinfunction "VBUS_1") (pintype "passive"))
      (node (ref "R33") (pin "2") (pinfunction "2_2") (pintype "passive"))
      (node (ref "U4") (pin "5") (pinfunction "V+_5") (pintype "bidirectional"))
    )
    (net (code "98") (name "Net-(CN4-TCK)") (class "Default")
      (node (ref "CN4") (pin "1") (pinfunction "TCK_1") (pintype "passive"))
      (node (ref "R37") (pin "1") (pinfunction "1_1") (pintype "passive"))
      (node (ref "U5") (pin "2") (pinfunction "TCK_2") (pintype "bidirectional"))
    )
    (net (code "99") (name "Net-(CN4-TDI)") (class "Default")
      (node (ref "CN4") (pin "9") (pinfunction "TDI_9") (pintype "passive"))
      (node (ref "U5") (pin "3") (pinfunction "PA00/TDI_3") (pintype "bidirectional"))
    )
    (net (code "100") (name "Net-(CN4-TDO)") (class "Default")
      (node (ref "CN4") (pin "3") (pinfunction "TDO_3") (pintype "passive"))
      (node (ref "U5") (pin "4") (pinfunction "PA01/TDO_4") (pintype "bidirectional"))
    )
    (net (code "101") (name "Net-(CN4-TMS)") (class "Default")
      (node (ref "CN4") (pin "5") (pinfunction "TMS_5") (pintype "passive"))
      (node (ref "U5") (pin "5") (pinfunction "PA02/TMS_5") (pintype "bidirectional"))
    )
    (net (code "102") (name "Net-(CN7-VCC)") (class "Default")
      (node (ref "C66") (pin "1") (pinfunction "1_1") (pintype "passive"))
      (node (ref "CN7") (pin "1") (pinfunction "VCC_1") (pintype "bidirectional"))
      (node (ref "FB1") (pin "2") (pinfunction "2_2") (pintype "passive"))
    )
    (net (code "103") (name "Net-(CN8-Pad1)") (class "Default")
      (node (ref "CN8") (pin "1") (pinfunction "1_1") (pintype "passive"))
      (node (ref "R54") (pin "1") (pinfunction "1_1") (pintype "passive"))
      (node (ref "R56") (pin "1") (pinfunction "1_1") (pintype "passive"))
    )
    (net (code "104") (name "Net-(CN8-Pad3)") (class "Default")
      (node (ref "CN8") (pin "3") (pinfunction "3_3") (pintype "passive"))
      (node (ref "R55") (pin "1") (pinfunction "1_1") (pintype "passive"))
      (node (ref "R57") (pin "1") (pinfunction "1_1") (pintype "passive"))
      (node (ref "VR1") (pin "A") (pinfunction "A_A") (pintype "passive"))
    )
    (net (code "105") (name "Net-(CN8-Pad4)") (class "Default")
      (node (ref "CN8") (pin "4") (pinfunction "4_4") (pintype "passive"))
      (node (ref "U12") (pin "2") (pinfunction "OUT_2") (pintype "bidirectional"))
      (node (ref "U12") (pin "3") (pinfunction "OUT_3") (pintype "bidirectional"))
    )
    (net (code "106") (name "Net-(LED1-PadA)") (class "Default")
      (node (ref "LED1") (pin "A") (pinfunction "A_A") (pintype "passive"))
      (node (ref "R40") (pin "1") (pinfunction "1_1") (pintype "passive"))
    )
    (net (code "107") (name "Net-(LED2-PadA)") (class "Default")
      (node (ref "LED2") (pin "A") (pinfunction "A_A") (pintype "passive"))
      (node (ref "R41") (pin "1") (pinfunction "1_1") (pintype "passive"))
    )
    (net (code "108") (name "Net-(LED3-PadA)") (class "Default")
      (node (ref "LED3") (pin "A") (pinfunction "A_A") (pintype "passive"))
      (node (ref "R42") (pin "1") (pinfunction "1_1") (pintype "passive"))
    )
    (net (code "109") (name "Net-(LED4-PadA)") (class "Default")
      (node (ref "LED4") (pin "A") (pinfunction "A_A") (pintype "passive"))
      (node (ref "R46") (pin "1") (pinfunction "1_1") (pintype "passive"))
    )
    (net (code "110") (name "Net-(LED5-PadA)") (class "Default")
      (node (ref "LED5") (pin "A") (pinfunction "A_A") (pintype "passive"))
      (node (ref "R47") (pin "1") (pinfunction "1_1") (pintype "passive"))
    )
    (net (code "111") (name "Net-(LED6-PadA)") (class "Default")
      (node (ref "LED6") (pin "A") (pinfunction "A_A") (pintype "passive"))
      (node (ref "R48") (pin "1") (pinfunction "1_1") (pintype "passive"))
    )
    (net (code "112") (name "Net-(LED7-PadA)") (class "Default")
      (node (ref "LED7") (pin "A") (pinfunction "A_A") (pintype "passive"))
      (node (ref "R49") (pin "1") (pinfunction "1_1") (pintype "passive"))
    )
    (net (code "113") (name "Net-(LED8-PadA)") (class "Default")
      (node (ref "LED8") (pin "A") (pinfunction "A_A") (pintype "passive"))
      (node (ref "R50") (pin "1") (pinfunction "1_1") (pintype "passive"))
    )
    (net (code "114") (name "Net-(LED9-PadA)") (class "Default")
      (node (ref "LED9") (pin "A") (pinfunction "A_A") (pintype "passive"))
      (node (ref "R51") (pin "1") (pinfunction "1_1") (pintype "passive"))
    )
    (net (code "115") (name "Net-(LED10-PadA)") (class "Default")
      (node (ref "LED10") (pin "A") (pinfunction "A_A") (pintype "passive"))
      (node (ref "R52") (pin "1") (pinfunction "1_1") (pintype "passive"))
    )
    (net (code "116") (name "Net-(Q1-D)") (class "Default")
      (node (ref "C166") (pin "2") (pinfunction "2_2") (pintype "passive"))
      (node (ref "Q1") (pin "3") (pinfunction "D_3") (pintype "passive"))
      (node (ref "Q3") (pin "4") (pinfunction "G_4") (pintype "passive"))
      (node (ref "R23") (pin "1") (pinfunction "1_1") (pintype "passive"))
    )
    (net (code "117") (name "Net-(Q1-G)") (class "Default")
      (node (ref "Q1") (pin "1") (pinfunction "G_1") (pintype "passive"))
      (node (ref "R29") (pin "1") (pinfunction "1_1") (pintype "passive"))
    )
    (net (code "118") (name "Net-(Q1-S)") (class "Default")
      (node (ref "Q1") (pin "2") (pinfunction "S_2") (pintype "passive"))
      (node (ref "R25") (pin "2") (pinfunction "2_2") (pintype "passive"))
    )
    (net (code "119") (name "Net-(Q2-D)") (class "Default")
      (node (ref "C167") (pin "2") (pinfunction "2_2") (pintype "passive"))
      (node (ref "Q2") (pin "3") (pinfunction "D_3") (pintype "passive"))
      (node (ref "Q4") (pin "4") (pinfunction "G_4") (pintype "passive"))
      (node (ref "R24") (pin "1") (pinfunction "1_1") (pintype "passive"))
    )
    (net (code "120") (name "Net-(Q2-G)") (class "Default")
      (node (ref "Q2") (pin "1") (pinfunction "G_1") (pintype "passive"))
      (node (ref "R30") (pin "1") (pinfunction "1_1") (pintype "passive"))
    )
    (net (code "121") (name "Net-(Q2-S)") (class "Default")
      (node (ref "Q2") (pin "2") (pinfunction "S_2") (pintype "passive"))
      (node (ref "R26") (pin "2") (pinfunction "2_2") (pintype "passive"))
    )
    (net (code "122") (name "Net-(R58-Pad1)") (class "Default")
      (node (ref "R58") (pin "1") (pinfunction "1_1") (pintype "passive"))
      (node (ref "R59") (pin "1") (pinfunction "1_1") (pintype "passive"))
      (node (ref "VR1") (pin "B") (pinfunction "B_B") (pintype "passive"))
      (node (ref "VR1") (pin "W") (pinfunction "W_W") (pintype "passive"))
    )
    (net (code "123") (name "Net-(R122-Pad1)") (class "Default")
      (node (ref "R122") (pin "1") (pinfunction "1_1") (pintype "passive"))
      (node (ref "R4") (pin "1") (pinfunction "1_1") (pintype "passive"))
      (node (ref "R5") (pin "2") (pinfunction "2_2") (pintype "passive"))
    )
    (net (code "124") (name "Net-(R123-Pad1)") (class "Default")
      (node (ref "R123") (pin "1") (pinfunction "1_1") (pintype "passive"))
      (node (ref "R6") (pin "1") (pinfunction "1_1") (pintype "passive"))
      (node (ref "R7") (pin "2") (pinfunction "2_2") (pintype "passive"))
    )
    (net (code "125") (name "Net-(RA1A-1)") (class "Default")
      (node (ref "RA1") (pin "A1") (pinfunction "1_A1") (pintype "passive"))
      (node (ref "U5") (pin "58") (pinfunction "PB11/SSC-TXFRM/TC-B2/USART0-TXD_58") (pintype "bidirectional"))
    )
    (net (code "126") (name "Net-(RA1C-1)") (class "Default")
      (node (ref "RA1") (pin "C1") (pinfunction "1_C1") (pintype "passive"))
      (node (ref "U5") (pin "57") (pinfunction "PB10/SSC-TXDAT/TC-A2/USART0-RXD_57") (pintype "bidirectional"))
    )
    (net (code "127") (name "Net-(RA2A-2)") (class "Default")
      (node (ref "RA2") (pin "A2") (pinfunction "2_A2") (pintype "passive"))
      (node (ref "U14") (pin "2") (pinfunction "~{OTW}_2") (pintype "bidirectional"))
    )
    (net (code "128") (name "Net-(RA2B-2)") (class "Default")
      (node (ref "RA2") (pin "B2") (pinfunction "2_B2") (pintype "passive"))
      (node (ref "U14") (pin "3") (pinfunction "~{FAULT}_3") (pintype "bidirectional"))
    )
    (net (code "129") (name "Net-(RA2C-2)") (class "Default")
      (node (ref "RA2") (pin "C2") (pinfunction "2_C2") (pintype "passive"))
      (node (ref "U14") (pin "4") (pinfunction "PWM_A_4") (pintype "bidirectional"))
    )
    (net (code "130") (name "Net-(RA2D-2)") (class "Default")
      (node (ref "RA2") (pin "D2") (pinfunction "2_D2") (pintype "passive"))
      (node (ref "U14") (pin "5") (pinfunction "~{RESET_A}_5") (pintype "bidirectional"))
    )
    (net (code "131") (name "Net-(RA3A-2)") (class "Default")
      (node (ref "RA3") (pin "A2") (pinfunction "2_A2") (pintype "passive"))
      (node (ref "U14") (pin "6") (pinfunction "PWM_B_6") (pintype "bidirectional"))
    )
    (net (code "132") (name "Net-(RA3B-2)") (class "Default")
      (node (ref "RA3") (pin "B2") (pinfunction "2_B2") (pintype "passive"))
      (node (ref "U14") (pin "14") (pinfunction "~{RESET_B}_14") (pintype "bidirectional"))
    )
    (net (code "133") (name "Net-(RA3C-2)") (class "Default")
      (node (ref "RA3") (pin "C2") (pinfunction "2_C2") (pintype "passive"))
      (node (ref "U14") (pin "15") (pinfunction "~{RESET_C}_15") (pintype "bidirectional"))
    )
    (net (code "134") (name "Net-(RA3D-2)") (class "Default")
      (node (ref "RA3") (pin "D2") (pinfunction "2_D2") (pintype "passive"))
      (node (ref "U14") (pin "16") (pinfunction "PWM_C_16") (pintype "bidirectional"))
    )
    (net (code "135") (name "Net-(RA4A-2)") (class "Default")
      (node (ref "RA4") (pin "A2") (pinfunction "2_A2") (pintype "passive"))
      (node (ref "U17") (pin "2") (pinfunction "~{OTW}_2") (pintype "bidirectional"))
    )
    (net (code "136") (name "Net-(RA4B-2)") (class "Default")
      (node (ref "RA4") (pin "B2") (pinfunction "2_B2") (pintype "passive"))
      (node (ref "U17") (pin "3") (pinfunction "~{FAULT}_3") (pintype "bidirectional"))
    )
    (net (code "137") (name "Net-(RA4C-2)") (class "Default")
      (node (ref "RA4") (pin "C2") (pinfunction "2_C2") (pintype "passive"))
      (node (ref "U17") (pin "4") (pinfunction "PWM_A_4") (pintype "bidirectional"))
    )
    (net (code "138") (name "Net-(RA4D-2)") (class "Default")
      (node (ref "RA4") (pin "D2") (pinfunction "2_D2") (pintype "passive"))
      (node (ref "U17") (pin "5") (pinfunction "~{RESET_A}_5") (pintype "bidirectional"))
    )
    (net (code "139") (name "Net-(RA5A-2)") (class "Default")
      (node (ref "RA5") (pin "A2") (pinfunction "2_A2") (pintype "passive"))
      (node (ref "U17") (pin "6") (pinfunction "PWM_B_6") (pintype "bidirectional"))
    )
    (net (code "140") (name "Net-(RA5B-2)") (class "Default")
      (node (ref "RA5") (pin "B2") (pinfunction "2_B2") (pintype "passive"))
      (node (ref "U17") (pin "14") (pinfunction "~{RESET_B}_14") (pintype "bidirectional"))
    )
    (net (code "141") (name "Net-(RA5C-2)") (class "Default")
      (node (ref "RA5") (pin "C2") (pinfunction "2_C2") (pintype "passive"))
      (node (ref "U17") (pin "15") (pinfunction "~{RESET_C}_15") (pintype "bidirectional"))
    )
    (net (code "142") (name "Net-(RA5D-2)") (class "Default")
      (node (ref "RA5") (pin "D2") (pinfunction "2_D2") (pintype "passive"))
      (node (ref "U17") (pin "16") (pinfunction "PWM_C_16") (pintype "bidirectional"))
    )
    (net (code "143") (name "Net-(RA6A-2)") (class "Default")
      (node (ref "RA6") (pin "A2") (pinfunction "2_A2") (pintype "passive"))
      (node (ref "U20") (pin "2") (pinfunction "~{OTW}_2") (pintype "bidirectional"))
    )
    (net (code "144") (name "Net-(RA6B-2)") (class "Default")
      (node (ref "RA6") (pin "B2") (pinfunction "2_B2") (pintype "passive"))
      (node (ref "U20") (pin "3") (pinfunction "~{FAULT}_3") (pintype "bidirectional"))
    )
    (net (code "145") (name "Net-(RA6C-2)") (class "Default")
      (node (ref "RA6") (pin "C2") (pinfunction "2_C2") (pintype "passive"))
      (node (ref "U20") (pin "4") (pinfunction "PWM_A_4") (pintype "bidirectional"))
    )
    (net (code "146") (name "Net-(RA6D-2)") (class "Default")
      (node (ref "RA6") (pin "D2") (pinfunction "2_D2") (pintype "passive"))
      (node (ref "U20") (pin "5") (pinfunction "~{RESET_A}_5") (pintype "bidirectional"))
    )
    (net (code "147") (name "Net-(RA7A-2)") (class "Default")
      (node (ref "RA7") (pin "A2") (pinfunction "2_A2") (pintype "passive"))
      (node (ref "U20") (pin "6") (pinfunction "PWM_B_6") (pintype "bidirectional"))
    )
    (net (code "148") (name "Net-(RA7B-2)") (class "Default")
      (node (ref "RA7") (pin "B2") (pinfunction "2_B2") (pintype "passive"))
      (node (ref "U20") (pin "14") (pinfunction "~{RESET_B}_14") (pintype "bidirectional"))
    )
    (net (code "149") (name "Net-(RA7C-2)") (class "Default")
      (node (ref "RA7") (pin "C2") (pinfunction "2_C2") (pintype "passive"))
      (node (ref "U20") (pin "15") (pinfunction "~{RESET_C}_15") (pintype "bidirectional"))
    )
    (net (code "150") (name "Net-(RA7D-2)") (class "Default")
      (node (ref "RA7") (pin "D2") (pinfunction "2_D2") (pintype "passive"))
      (node (ref "U20") (pin "16") (pinfunction "PWM_C_16") (pintype "bidirectional"))
    )
    (net (code "151") (name "Net-(RA8A-2)") (class "Default")
      (node (ref "RA8") (pin "A2") (pinfunction "2_A2") (pintype "passive"))
      (node (ref "U23") (pin "2") (pinfunction "~{OTW}_2") (pintype "bidirectional"))
    )
    (net (code "152") (name "Net-(RA8B-2)") (class "Default")
      (node (ref "RA8") (pin "B2") (pinfunction "2_B2") (pintype "passive"))
      (node (ref "U23") (pin "3") (pinfunction "~{FAULT}_3") (pintype "bidirectional"))
    )
    (net (code "153") (name "Net-(RA8C-2)") (class "Default")
      (node (ref "RA8") (pin "C2") (pinfunction "2_C2") (pintype "passive"))
      (node (ref "U23") (pin "4") (pinfunction "PWM_A_4") (pintype "bidirectional"))
    )
    (net (code "154") (name "Net-(RA8D-2)") (class "Default")
      (node (ref "RA8") (pin "D2") (pinfunction "2_D2") (pintype "passive"))
      (node (ref "U23") (pin "5") (pinfunction "~{RESET_A}_5") (pintype "bidirectional"))
    )
    (net (code "155") (name "Net-(RA9A-2)") (class "Default")
      (node (ref "RA9") (pin "A2") (pinfunction "2_A2") (pintype "passive"))
      (node (ref "U23") (pin "6") (pinfunction "PWM_B_6") (pintype "bidirectional"))
    )
    (net (code "156") (name "Net-(RA9B-2)") (class "Default")
      (node (ref "RA9") (pin "B2") (pinfunction "2_B2") (pintype "passive"))
      (node (ref "U23") (pin "14") (pinfunction "~{RESET_B}_14") (pintype "bidirectional"))
    )
    (net (code "157") (name "Net-(RA9C-2)") (class "Default")
      (node (ref "RA9") (pin "C2") (pinfunction "2_C2") (pintype "passive"))
      (node (ref "U23") (pin "15") (pinfunction "~{RESET_C}_15") (pintype "bidirectional"))
    )
    (net (code "158") (name "Net-(RA9D-2)") (class "Default")
      (node (ref "RA9") (pin "D2") (pinfunction "2_D2") (pintype "passive"))
      (node (ref "U23") (pin "16") (pinfunction "PWM_C_16") (pintype "bidirectional"))
    )
    (net (code "159") (name "Net-(RA10A-2)") (class "Default")
      (node (ref "RA10") (pin "A2") (pinfunction "2_A2") (pintype "passive"))
      (node (ref "U37") (pin "2") (pinfunction "~{OTW}_2") (pintype "bidirectional"))
    )
    (net (code "160") (name "Net-(RA10B-2)") (class "Default")
      (node (ref "RA10") (pin "B2") (pinfunction "2_B2") (pintype "passive"))
      (node (ref "U37") (pin "3") (pinfunction "~{FAULT}_3") (pintype "bidirectional"))
    )
    (net (code "161") (name "Net-(RA10C-2)") (class "Default")
      (node (ref "RA10") (pin "C2") (pinfunction "2_C2") (pintype "passive"))
      (node (ref "U37") (pin "4") (pinfunction "PWM_A_4") (pintype "bidirectional"))
    )
    (net (code "162") (name "Net-(RA10D-2)") (class "Default")
      (node (ref "RA10") (pin "D2") (pinfunction "2_D2") (pintype "passive"))
      (node (ref "U37") (pin "5") (pinfunction "~{RESET_A}_5") (pintype "bidirectional"))
    )
    (net (code "163") (name "Net-(RA11A-2)") (class "Default")
      (node (ref "RA11") (pin "A2") (pinfunction "2_A2") (pintype "passive"))
      (node (ref "U37") (pin "6") (pinfunction "PWM_B_6") (pintype "bidirectional"))
    )
    (net (code "164") (name "Net-(RA11B-2)") (class "Default")
      (node (ref "RA11") (pin "B2") (pinfunction "2_B2") (pintype "passive"))
      (node (ref "U37") (pin "14") (pinfunction "~{RESET_B}_14") (pintype "bidirectional"))
    )
    (net (code "165") (name "Net-(RA11C-2)") (class "Default")
      (node (ref "RA11") (pin "C2") (pinfunction "2_C2") (pintype "passive"))
      (node (ref "U37") (pin "15") (pinfunction "~{RESET_C}_15") (pintype "bidirectional"))
    )
    (net (code "166") (name "Net-(RA11D-2)") (class "Default")
      (node (ref "RA11") (pin "D2") (pinfunction "2_D2") (pintype "passive"))
      (node (ref "U37") (pin "16") (pinfunction "PWM_C_16") (pintype "bidirectional"))
    )
    (net (code "167") (name "Net-(RF3-Pad2)") (class "Default")
      (node (ref "RF3") (pin "2") (pinfunction "2_2") (pintype "passive"))
      (node (ref "U34") (pin "2") (pinfunction "OUT_2") (pintype "bidirectional"))
      (node (ref "U34") (pin "3") (pinfunction "OUT_3") (pintype "bidirectional"))
    )
    (net (code "168") (name "Net-(RF4-Pad2)") (class "Default")
      (node (ref "RF4") (pin "2") (pinfunction "2_2") (pintype "passive"))
      (node (ref "U35") (pin "2") (pinfunction "OUT_2") (pintype "bidirectional"))
      (node (ref "U35") (pin "3") (pinfunction "OUT_3") (pintype "bidirectional"))
    )
    (net (code "169") (name "Net-(SW1-A)") (class "Default")
      (node (ref "D1") (pin "K") (pinfunction "K_K") (pintype "passive"))
      (node (ref "F1") (pin "2") (pinfunction "2_2") (pintype "passive"))
      (node (ref "SW1") (pin "P") (pinfunction "A_P") (pintype "passive"))
    )
    (net (code "170") (name "Net-(U2-DA1)") (class "Default")
      (node (ref "D5") (pin "A") (pinfunction "A_A") (pintype "passive"))
      (node (ref "U2") (pin "6") (pinfunction "DA1_6") (pintype "bidirectional"))
    )
    (net (code "171") (name "Net-(U2-DA2)") (class "Default")
      (node (ref "D6") (pin "A") (pinfunction "A_A") (pintype "passive"))
      (node (ref "U2") (pin "1") (pinfunction "DA2_1") (pintype "bidirectional"))
    )
    (net (code "172") (name "Net-(U2-DA3)") (class "Default")
      (node (ref "D7") (pin "A") (pinfunction "A_A") (pintype "passive"))
      (node (ref "U2") (pin "3") (pinfunction "DA3_3") (pintype "bidirectional"))
    )
    (net (code "173") (name "Net-(U2-DA4)") (class "Default")
      (node (ref "D8") (pin "A") (pinfunction "A_A") (pintype "passive"))
      (node (ref "U2") (pin "8") (pinfunction "DA4_8") (pintype "bidirectional"))
    )
    (net (code "174") (name "Net-(U2-EN{slash}UVLO)") (class "Default")
      (node (ref "R10") (pin "2") (pinfunction "2_2") (pintype "passive"))
      (node (ref "R9") (pin "1") (pinfunction "1_1") (pintype "passive"))
      (node (ref "U2") (pin "16") (pinfunction "EN/UVLO_16") (pintype "bidirectional"))
    )
    (net (code "175") (name "Net-(U2-FB1)") (class "Default")
      (node (ref "R14") (pin "1") (pinfunction "1_1") (pintype "passive"))
      (node (ref "R15") (pin "2") (pinfunction "2_2") (pintype "passive"))
      (node (ref "U2") (pin "20") (pinfunction "FB1_20") (pintype "bidirectional"))
    )
    (net (code "176") (name "Net-(U2-FB2)") (class "Default")
      (node (ref "R16") (pin "1") (pinfunction "1_1") (pintype "passive"))
      (node (ref "R17") (pin "2") (pinfunction "2_2") (pintype "passive"))
      (node (ref "U2") (pin "22") (pinfunction "FB2_22") (pintype "bidirectional"))
    )
    (net (code "177") (name "Net-(U2-FB3)") (class "Default")
      (node (ref "R18") (pin "1") (pinfunction "1_1") (pintype "passive"))
      (node (ref "R19") (pin "2") (pinfunction "2_2") (pintype "passive"))
      (node (ref "U2") (pin "21") (pinfunction "FB3_21") (pintype "bidirectional"))
    )
    (net (code "178") (name "Net-(U2-FB4)") (class "Default")
      (node (ref "R20") (pin "1") (pinfunction "1_1") (pintype "passive"))
      (node (ref "R21") (pin "2") (pinfunction "2_2") (pintype "passive"))
      (node (ref "U2") (pin "19") (pinfunction "FB4_19") (pintype "bidirectional"))
    )
    (net (code "179") (name "Net-(U2-RT{slash}SYNC)") (class "Default")
      (node (ref "R12") (pin "2") (pinfunction "2_2") (pintype "passive"))
      (node (ref "U2") (pin "17") (pinfunction "RT/SYNC_17") (pintype "bidirectional"))
    )
    (net (code "180") (name "Net-(U2-RUN{slash}SS1)") (class "Default")
      (node (ref "C12") (pin "1") (pinfunction "1_1") (pintype "passive"))
      (node (ref "U2") (pin "12") (pinfunction "RUN/SS4_12") (pintype "bidirectional"))
      (node (ref "U2") (pin "13") (pinfunction "RUN/SS1_13") (pintype "bidirectional"))
      (node (ref "U2") (pin "15") (pinfunction "RUN/SS3_15") (pintype "bidirectional"))
    )
    (net (code "181") (name "Net-(U2-RUN{slash}SS2)") (class "Default")
      (node (ref "C8") (pin "1") (pinfunction "1_1") (pintype "passive"))
      (node (ref "R11") (pin "2") (pinfunction "2_2") (pintype "passive"))
      (node (ref "R8") (pin "2") (pinfunction "2_2") (pintype "passive"))
      (node (ref "U2") (pin "14") (pinfunction "RUN/SS2_14") (pintype "bidirectional"))
    )
    (net (code "182") (name "Net-(U2-SKY)") (class "Default")
      (node (ref "C10") (pin "1") (pinfunction "1_1") (pintype "passive"))
      (node (ref "U2") (pin "25") (pinfunction "SKY_25") (pintype "bidirectional"))
    )
    (net (code "183") (name "Net-(U2-SW1)") (class "Default")
      (node (ref "D5") (pin "K") (pinfunction "K_K") (pintype "passive"))
      (node (ref "L2") (pin "1") (pinfunction "1_1") (pintype "passive"))
      (node (ref "U2") (pin "5") (pinfunction "SW1_5") (pintype "bidirectional"))
    )
    (net (code "184") (name "Net-(U2-SW2)") (class "Default")
      (node (ref "D6") (pin "K") (pinfunction "K_K") (pintype "passive"))
      (node (ref "L3") (pin "1") (pinfunction "1_1") (pintype "passive"))
      (node (ref "R13") (pin "2") (pinfunction "2_2") (pintype "passive"))
      (node (ref "U2") (pin "2") (pinfunction "SW2_2") (pintype "bidirectional"))
    )
    (net (code "185") (name "Net-(U2-SW3)") (class "Default")
      (node (ref "D7") (pin "K") (pinfunction "K_K") (pintype "passive"))
      (node (ref "L4") (pin "1") (pinfunction "1_1") (pintype "passive"))
      (node (ref "U2") (pin "4") (pinfunction "SW3_4") (pintype "bidirectional"))
    )
    (net (code "186") (name "Net-(U2-SW4)") (class "Default")
      (node (ref "D8") (pin "K") (pinfunction "K_K") (pintype "passive"))
      (node (ref "L5") (pin "1") (pinfunction "1_1") (pintype "passive"))
      (node (ref "U2") (pin "7") (pinfunction "SW4_7") (pintype "bidirectional"))
    )
    (net (code "187") (name "Net-(U2-SW5)") (class "Default")
      (node (ref "L1") (pin "2") (pinfunction "2_2") (pintype "passive"))
      (node (ref "U2") (pin "24") (pinfunction "SW5_24") (pintype "bidirectional"))
    )
    (net (code "188") (name "Net-(U3-IN)") (class "Default")
      (node (ref "C17") (pin "1") (pinfunction "1_1") (pintype "passive"))
      (node (ref "C19") (pin "1") (pinfunction "1_1") (pintype "passive"))
      (node (ref "L4") (pin "2") (pinfunction "2_2") (pintype "passive"))
      (node (ref "R18") (pin "2") (pinfunction "2_2") (pintype "passive"))
      (node (ref "U3") (pin "1") (pinfunction "IN_1") (pintype "bidirectional"))
    )
    (net (code "189") (name "Net-(U3-NR)") (class "Default")
      (node (ref "C20") (pin "1") (pinfunction "1_1") (pintype "passive"))
      (node (ref "U3") (pin "4") (pinfunction "NR_4") (pintype "bidirectional"))
    )
    (net (code "190") (name "Net-(U4-I1)") (class "Default")
      (node (ref "R34") (pin "1") (pinfunction "1_1") (pintype "passive"))
      (node (ref "U4") (pin "3") (pinfunction "I1_3") (pintype "bidirectional"))
    )
    (net (code "191") (name "Net-(U4-I2)") (class "Default")
      (node (ref "R35") (pin "1") (pinfunction "1_1") (pintype "passive"))
      (node (ref "U4") (pin "4") (pinfunction "I2_4") (pintype "bidirectional"))
    )
    (net (code "192") (name "Net-(U5-DM)") (class "Default")
      (node (ref "R35") (pin "2") (pinfunction "2_2") (pintype "passive"))
      (node (ref "U5") (pin "51") (pinfunction "DM_51") (pintype "bidirectional"))
    )
    (net (code "193") (name "Net-(U5-DP)") (class "Default")
      (node (ref "R34") (pin "2") (pinfunction "2_2") (pintype "passive"))
      (node (ref "U5") (pin "50") (pinfunction "DP_50") (pintype "bidirectional"))
    )
    (net (code "194") (name "Net-(U5-PA26{slash}TC-A0{slash}USB_ID{slash}USART2-TXD{slash}ABDAC-DATA1)") (class "Default")
      (node (ref "R38") (pin "1") (pinfunction "1_1") (pintype "passive"))
      (node (ref "U5") (pin "61") (pinfunction "PA26/TC-A0/USB_ID/USART2-TXD/ABDAC-DATA1_61") (pintype "bidirectional"))
    )
    (net (code "195") (name "Net-(U5-PA27{slash}TC-B0{slash}USB_VBOF{slash}USART2-RXD{slash}ABDAC-DATAN1)") (class "Default")
      (node (ref "R39") (pin "1") (pinfunction "1_1") (pintype "passive"))
      (node (ref "U5") (pin "62") (pinfunction "PA27/TC-B0/USB_VBOF/USART2-RXD/ABDAC-DATAN1_62") (pintype "bidirectional"))
    )
    (net (code "196") (name "Net-(U5-VBUS)") (class "Default")
      (node (ref "R33") (pin "1") (pinfunction "1_1") (pintype "passive"))
      (node (ref "U5") (pin "52") (pinfunction "VBUS_52") (pintype "bidirectional"))
    )
    (net (code "197") (name "Net-(U5-VDDOUT)") (class "Default")
      (node (ref "C25") (pin "1") (pinfunction "1_1") (pintype "passive"))
      (node (ref "C27") (pin "1") (pinfunction "1_1") (pintype "passive"))
      (node (ref "C29") (pin "1") (pinfunction "1_1") (pintype "passive"))
      (node (ref "C31") (pin "1") (pinfunction "1_1") (pintype "passive"))
      (node (ref "C32") (pin "1") (pinfunction "1_1") (pintype "passive"))
      (node (ref "C34") (pin "1") (pinfunction "1_1") (pintype "passive"))
      (node (ref "U5") (pin "20") (pinfunction "VDDOUT_20") (pintype "bidirectional"))
      (node (ref "U5") (pin "22") (pinfunction "VDDCORE_22") (pintype "bidirectional"))
      (node (ref "U5") (pin "53") (pinfunction "VDDPLL_53") (pintype "bidirectional"))
      (node (ref "U5") (pin "56") (pinfunction "VDDCORE_56") (pintype "bidirectional"))
      (node (ref "U5") (pin "8") (pinfunction "VDDCORE_8") (pintype "bidirectional"))
    )
    (net (code "198") (name "Net-(U8A-Y)") (class "Default")
      (node (ref "U8") (pin "4") (pinfunction "Y_4") (pintype "bidirectional"))
      (node (ref "U9") (pin "37") (pinfunction "PROGRAM_B_2_37") (pintype "bidirectional"))
    )
    (net (code "199") (name "Net-(U10A-Y)") (class "Default")
      (node (ref "U10") (pin "4") (pinfunction "Y_4") (pintype "bidirectional"))
      (node (ref "U9") (pin "70") (pinfunction "IO_L1P_CCLK_2_70") (pintype "bidirectional"))
    )
    (net (code "200") (name "Net-(U11-QA)") (class "Default")
      (node (ref "R45") (pin "2") (pinfunction "2_2") (pintype "passive"))
      (node (ref "U11") (pin "3") (pinfunction "QA_3") (pintype "bidirectional"))
    )
    (net (code "201") (name "Net-(U11-QB)") (class "Default")
      (node (ref "R52") (pin "2") (pinfunction "2_2") (pintype "passive"))
      (node (ref "U11") (pin "4") (pinfunction "QB_4") (pintype "bidirectional"))
    )
    (net (code "202") (name "Net-(U11-QC)") (class "Default")
      (node (ref "R51") (pin "2") (pinfunction "2_2") (pintype "passive"))
      (node (ref "U11") (pin "5") (pinfunction "QC_5") (pintype "bidirectional"))
    )
    (net (code "203") (name "Net-(U11-QD)") (class "Default")
      (node (ref "R50") (pin "2") (pinfunction "2_2") (pintype "passive"))
      (node (ref "U11") (pin "6") (pinfunction "QD_6") (pintype "bidirectional"))
    )
    (net (code "204") (name "Net-(U11-QE)") (class "Default")
      (node (ref "R49") (pin "2") (pinfunction "2_2") (pintype "passive"))
      (node (ref "U11") (pin "10") (pinfunction "QE_10") (pintype "bidirectional"))
    )
    (net (code "205") (name "Net-(U11-QF)") (class "Default")
      (node (ref "R48") (pin "2") (pinfunction "2_2") (pintype "passive"))
      (node (ref "U11") (pin "11") (pinfunction "QF_11") (pintype "bidirectional"))
    )
    (net (code "206") (name "Net-(U11-QG)") (class "Default")
      (node (ref "R47") (pin "2") (pinfunction "2_2") (pintype "passive"))
      (node (ref "U11") (pin "12") (pinfunction "QG_12") (pintype "bidirectional"))
    )
    (net (code "207") (name "Net-(U11-QH)") (class "Default")
      (node (ref "R46") (pin "2") (pinfunction "2_2") (pintype "passive"))
      (node (ref "U11") (pin "13") (pinfunction "QH_13") (pintype "bidirectional"))
    )
    (net (code "208") (name "Net-(U12-IN)") (class "Default")
      (node (ref "R61") (pin "2") (pinfunction "2_2") (pintype "passive"))
      (node (ref "RF1") (pin "1") (pinfunction "1_1") (pintype "passive"))
      (node (ref "RF2") (pin "1") (pinfunction "1_1") (pintype "passive"))
      (node (ref "U12") (pin "4") (pinfunction "IN_4") (pintype "bidirectional"))
    )
    (net (code "209") (name "Net-(U12-R1)") (class "Default")
      (node (ref "R61") (pin "1") (pinfunction "1_1") (pintype "passive"))
      (node (ref "U12") (pin "6") (pinfunction "R1_6") (pintype "bidirectional"))
    )
    (net (code "210") (name "Net-(U13-VO1)") (class "Default")
      (node (ref "BZ1") (pin "1") (pinfunction "1_1") (pintype "passive"))
      (node (ref "U13") (pin "8") (pinfunction "VO1_8") (pintype "bidirectional"))
    )
    (net (code "211") (name "Net-(U13-VO2)") (class "Default")
      (node (ref "BZ1") (pin "2") (pinfunction "2_2") (pintype "passive"))
      (node (ref "U13") (pin "7") (pinfunction "VO2_7") (pintype "bidirectional"))
    )
    (net (code "212") (name "Net-(U14-BST_A)") (class "Default")
      (node (ref "C74") (pin "1") (pinfunction "1_1") (pintype "passive"))
      (node (ref "U14") (pin "35") (pinfunction "BST_A_35") (pintype "bidirectional"))
    )
    (net (code "213") (name "Net-(U14-BST_B)") (class "Default")
      (node (ref "C75") (pin "1") (pinfunction "1_1") (pintype "passive"))
      (node (ref "U14") (pin "28") (pinfunction "BST_B_28") (pintype "bidirectional"))
    )
    (net (code "214") (name "Net-(U14-BST_C)") (class "Default")
      (node (ref "C76") (pin "1") (pinfunction "1_1") (pintype "passive"))
      (node (ref "U14") (pin "20") (pinfunction "BST_C_20") (pintype "bidirectional"))
    )
    (net (code "215") (name "Net-(U14-M1)") (class "Default")
      (node (ref "C72") (pin "1") (pinfunction "1_1") (pintype "passive"))
      (node (ref "U14") (pin "10") (pinfunction "VREG_10") (pintype "bidirectional"))
      (node (ref "U14") (pin "11") (pinfunction "M3_11") (pintype "bidirectional"))
      (node (ref "U14") (pin "13") (pinfunction "M1_13") (pintype "bidirectional"))
    )
    (net (code "216") (name "Net-(U14-OC_ADJ)") (class "Default")
      (node (ref "R62") (pin "2") (pinfunction "2_2") (pintype "passive"))
      (node (ref "U14") (pin "7") (pinfunction "OC_ADJ_7") (pintype "bidirectional"))
    )
    (net (code "217") (name "Net-(U17-BST_A)") (class "Default")
      (node (ref "C89") (pin "1") (pinfunction "1_1") (pintype "passive"))
      (node (ref "U17") (pin "35") (pinfunction "BST_A_35") (pintype "bidirectional"))
    )
    (net (code "218") (name "Net-(U17-BST_B)") (class "Default")
      (node (ref "C90") (pin "1") (pinfunction "1_1") (pintype "passive"))
      (node (ref "U17") (pin "28") (pinfunction "BST_B_28") (pintype "bidirectional"))
    )
    (net (code "219") (name "Net-(U17-BST_C)") (class "Default")
      (node (ref "C91") (pin "1") (pinfunction "1_1") (pintype "passive"))
      (node (ref "U17") (pin "20") (pinfunction "BST_C_20") (pintype "bidirectional"))
    )
    (net (code "220") (name "Net-(U17-M1)") (class "Default")
      (node (ref "C87") (pin "1") (pinfunction "1_1") (pintype "passive"))
      (node (ref "U17") (pin "10") (pinfunction "VREG_10") (pintype "bidirectional"))
      (node (ref "U17") (pin "11") (pinfunction "M3_11") (pintype "bidirectional"))
      (node (ref "U17") (pin "13") (pinfunction "M1_13") (pintype "bidirectional"))
    )
    (net (code "221") (name "Net-(U17-OC_ADJ)") (class "Default")
      (node (ref "R66") (pin "2") (pinfunction "2_2") (pintype "passive"))
      (node (ref "U17") (pin "7") (pinfunction "OC_ADJ_7") (pintype "bidirectional"))
    )
    (net (code "222") (name "Net-(U20-BST_A)") (class "Default")
      (node (ref "C104") (pin "1") (pinfunction "1_1") (pintype "passive"))
      (node (ref "U20") (pin "35") (pinfunction "BST_A_35") (pintype "bidirectional"))
    )
    (net (code "223") (name "Net-(U20-BST_B)") (class "Default")
      (node (ref "C105") (pin "1") (pinfunction "1_1") (pintype "passive"))
      (node (ref "U20") (pin "28") (pinfunction "BST_B_28") (pintype "bidirectional"))
    )
    (net (code "224") (name "Net-(U20-BST_C)") (class "Default")
      (node (ref "C106") (pin "1") (pinfunction "1_1") (pintype "passive"))
      (node (ref "U20") (pin "20") (pinfunction "BST_C_20") (pintype "bidirectional"))
    )
    (net (code "225") (name "Net-(U20-M1)") (class "Default")
      (node (ref "C102") (pin "1") (pinfunction "1_1") (pintype "passive"))
      (node (ref "U20") (pin "10") (pinfunction "VREG_10") (pintype "bidirectional"))
      (node (ref "U20") (pin "11") (pinfunction "M3_11") (pintype "bidirectional"))
      (node (ref "U20") (pin "13") (pinfunction "M1_13") (pintype "bidirectional"))
    )
    (net (code "226") (name "Net-(U20-OC_ADJ)") (class "Default")
      (node (ref "R70") (pin "2") (pinfunction "2_2") (pintype "passive"))
      (node (ref "U20") (pin "7") (pinfunction "OC_ADJ_7") (pintype "bidirectional"))
    )
    (net (code "227") (name "Net-(U23-BST_A)") (class "Default")
      (node (ref "C119") (pin "1") (pinfunction "1_1") (pintype "passive"))
      (node (ref "U23") (pin "35") (pinfunction "BST_A_35") (pintype "bidirectional"))
    )
    (net (code "228") (name "Net-(U23-BST_B)") (class "Default")
      (node (ref "C120") (pin "1") (pinfunction "1_1") (pintype "passive"))
      (node (ref "U23") (pin "28") (pinfunction "BST_B_28") (pintype "bidirectional"))
    )
    (net (code "229") (name "Net-(U23-BST_C)") (class "Default")
      (node (ref "C121") (pin "1") (pinfunction "1_1") (pintype "passive"))
      (node (ref "U23") (pin "20") (pinfunction "BST_C_20") (pintype "bidirectional"))
    )
    (net (code "230") (name "Net-(U23-M1)") (class "Default")
      (node (ref "C117") (pin "1") (pinfunction "1_1") (pintype "passive"))
      (node (ref "U23") (pin "10") (pinfunction "VREG_10") (pintype "bidirectional"))
      (node (ref "U23") (pin "11") (pinfunction "M3_11") (pintype "bidirectional"))
      (node (ref "U23") (pin "13") (pinfunction "M1_13") (pintype "bidirectional"))
    )
    (net (code "231") (name "Net-(U23-OC_ADJ)") (class "Default")
      (node (ref "R74") (pin "2") (pinfunction "2_2") (pintype "passive"))
      (node (ref "U23") (pin "7") (pinfunction "OC_ADJ_7") (pintype "bidirectional"))
    )
    (net (code "232") (name "Net-(U26-QH)") (class "Default")
      (node (ref "U26") (pin "9") (pinfunction "QH_9") (pintype "bidirectional"))
      (node (ref "U27") (pin "10") (pinfunction "SI_10") (pintype "bidirectional"))
    )
    (net (code "233") (name "Net-(U27-A)") (class "Default")
      (node (ref "R98") (pin "2") (pinfunction "2_2") (pintype "passive"))
      (node (ref "R99") (pin "1") (pinfunction "1_1") (pintype "passive"))
      (node (ref "U27") (pin "11") (pinfunction "A_11") (pintype "bidirectional"))
    )
    (net (code "234") (name "Net-(U30-E)") (class "Default")
      (node (ref "R104") (pin "2") (pinfunction "2_2") (pintype "passive"))
      (node (ref "R105") (pin "2") (pinfunction "2_2") (pintype "passive"))
      (node (ref "U30") (pin "3") (pinfunction "E_3") (pintype "bidirectional"))
    )
    (net (code "235") (name "Net-(U30-QH)") (class "Default")
      (node (ref "U30") (pin "9") (pinfunction "QH_9") (pintype "bidirectional"))
      (node (ref "U31") (pin "10") (pinfunction "SI_10") (pintype "bidirectional"))
    )
    (net (code "236") (name "Net-(U34-R1)") (class "Default")
      (node (ref "R111") (pin "1") (pinfunction "1_1") (pintype "passive"))
      (node (ref "U34") (pin "6") (pinfunction "R1_6") (pintype "bidirectional"))
    )
    (net (code "237") (name "Net-(U35-R1)") (class "Default")
      (node (ref "R113") (pin "1") (pinfunction "1_1") (pintype "passive"))
      (node (ref "U35") (pin "6") (pinfunction "R1_6") (pintype "bidirectional"))
    )
    (net (code "238") (name "Net-(U37-BST_A)") (class "Default")
      (node (ref "C155") (pin "1") (pinfunction "1_1") (pintype "passive"))
      (node (ref "U37") (pin "35") (pinfunction "BST_A_35") (pintype "bidirectional"))
    )
    (net (code "239") (name "Net-(U37-BST_B)") (class "Default")
      (node (ref "C156") (pin "1") (pinfunction "1_1") (pintype "passive"))
      (node (ref "U37") (pin "28") (pinfunction "BST_B_28") (pintype "bidirectional"))
    )
    (net (code "240") (name "Net-(U37-BST_C)") (class "Default")
      (node (ref "C157") (pin "1") (pinfunction "1_1") (pintype "passive"))
      (node (ref "U37") (pin "20") (pinfunction "BST_C_20") (pintype "bidirectional"))
    )
    (net (code "241") (name "Net-(U37-M1)") (class "Default")
      (node (ref "C153") (pin "1") (pinfunction "1_1") (pintype "passive"))
      (node (ref "U37") (pin "10") (pinfunction "VREG_10") (pintype "bidirectional"))
      (node (ref "U37") (pin "11") (pinfunction "M3_11") (pintype "bidirectional"))
      (node (ref "U37") (pin "13") (pinfunction "M1_13") (pintype "bidirectional"))
    )
    (net (code "242") (name "Net-(U37-OC_ADJ)") (class "Default")
      (node (ref "R117") (pin "2") (pinfunction "2_2") (pintype "passive"))
      (node (ref "U37") (pin "7") (pinfunction "OC_ADJ_7") (pintype "bidirectional"))
    )
    (net (code "243") (name "Net-(X1-OUT)") (class "Default")
      (node (ref "R31") (pin "1") (pinfunction "1_1") (pintype "passive"))
      (node (ref "R32") (pin "1") (pinfunction "1_1") (pintype "passive"))
      (node (ref "X1") (pin "3") (pinfunction "OUT_3") (pintype "bidirectional"))
    )
    (net (code "244") (name "PWR_5V") (class "Default")
      (node (ref "R22") (pin "2") (pinfunction "2_2") (pintype "passive"))
      (node (ref "U3") (pin "3") (pinfunction "EN_3") (pintype "bidirectional"))
      (node (ref "U9") (pin "40") (pinfunction "IO_L64N_D9_2_40") (pintype "bidirectional"))
    )
    (net (code "245") (name "PWR_12V") (class "Default")
      (node (ref "R8") (pin "1") (pinfunction "1_1") (pintype "passive"))
      (node (ref "U5") (pin "43") (pinfunction "PB07/SSC-RXDAT/USART1-DSR/ABDAC-DATAN0_43") (pintype "bidirectional"))
    )
    (net (code "246") (name "PWR_MOTOR1") (class "Default")
      (node (ref "R27") (pin "2") (pinfunction "2_2") (pintype "passive"))
      (node (ref "R29") (pin "2") (pinfunction "2_2") (pintype "passive"))
      (node (ref "U5") (pin "6") (pinfunction "PB00/TC-A0/USART2-CTS_6") (pintype "bidirectional"))
    )
    (net (code "247") (name "PWR_MOTOR2") (class "Default")
      (node (ref "R28") (pin "2") (pinfunction "2_2") (pintype "passive"))
      (node (ref "R30") (pin "2") (pinfunction "2_2") (pintype "passive"))
      (node (ref "U5") (pin "44") (pinfunction "PA20/TC-CLK0/USART1-CLK/USART2-RXD/SSC-TXDAT_44") (pintype "bidirectional"))
    )
    (net (code "248") (name "SPI_MISO") (class "Default")
      (node (ref "CN18") (pin "7") (pinfunction "7_7") (pintype "passive"))
      (node (ref "U5") (pin "39") (pinfunction "PA18/XIN0/PWM5/USART0-RXD/SPI0-MISO/SSC-RXFRM_39") (pintype "bidirectional"))
      (node (ref "U7") (pin "2") (pinfunction "SO/SIO1_2") (pintype "bidirectional"))
      (node (ref "U9") (pin "66") (pinfunction "IO_L2N_CMPMOSI_2_66") (pintype "bidirectional"))
    )
    (net (code "249") (name "SPI_MOSI") (class "Default")
      (node (ref "CN18") (pin "6") (pinfunction "6_6") (pintype "passive"))
      (node (ref "U5") (pin "34") (pinfunction "PA14/PWM3/INT2/SPI0-MOSI/GCLK2_34") (pintype "bidirectional"))
      (node (ref "U7") (pin "5") (pinfunction "SI/SIO0_5") (pintype "bidirectional"))
      (node (ref "U9") (pin "65") (pinfunction "IO_L3P_D0_DIN_MISO_MISO1_2_65") (pintype "bidirectional"))
    )
    (net (code "250") (name "SPI_SCLK") (class "Default")
      (node (ref "CN18") (pin "5") (pinfunction "5_5") (pintype "passive"))
      (node (ref "U10") (pin "2") (pinfunction "B_2") (pintype "bidirectional"))
      (node (ref "U5") (pin "35") (pinfunction "PA15/PWM4/USART2-CLK/SPI0-SCK_35") (pintype "bidirectional"))
      (node (ref "U7") (pin "6") (pinfunction "SCLK_6") (pintype "bidirectional"))
      (node (ref "U9") (pin "56") (pinfunction "IO_L30P_GCLK1_D13_2_56") (pintype "bidirectional"))
    )
    (net (code "251") (name "VBAT") (class "Default")
      (node (ref "C2") (pin "1") (pinfunction "1_1") (pintype "passive"))
      (node (ref "C3") (pin "P") (pinfunction "P_P") (pintype "passive"))
      (node (ref "C4") (pin "P") (pinfunction "P_P") (pintype "passive"))
      (node (ref "CN2") (pin "4") (pinfunction "4_4") (pintype "passive"))
      (node (ref "CN2") (pin "8") (pinfunction "8_8") (pintype "passive"))
      (node (ref "D2") (pin "K") (pinfunction "K_K") (pintype "passive"))
      (node (ref "D3") (pin "A") (pinfunction "A_A") (pintype "passive"))
      (node (ref "Q3") (pin "1") (pinfunction "S_1") (pintype "passive"))
      (node (ref "Q3") (pin "2") (pinfunction "S_2") (pintype "passive"))
      (node (ref "Q3") (pin "3") (pinfunction "S_3") (pintype "passive"))
      (node (ref "Q4") (pin "1") (pinfunction "S_1") (pintype "passive"))
      (node (ref "Q4") (pin "2") (pinfunction "S_2") (pintype "passive"))
      (node (ref "Q4") (pin "3") (pinfunction "S_3") (pintype "passive"))
      (node (ref "R23") (pin "2") (pinfunction "2_2") (pintype "passive"))
      (node (ref "R24") (pin "2") (pinfunction "2_2") (pintype "passive"))
      (node (ref "R4") (pin "2") (pinfunction "2_2") (pintype "passive"))
      (node (ref "SW1") (pin "1") (pinfunction "B_1") (pintype "passive"))
    )
    (net (code "252") (name "VCC{slash}1") (class "Default")
      (node (ref "C77") (pin "1") (pinfunction "1_1") (pintype "passive"))
      (node (ref "C78") (pin "1") (pinfunction "1_1") (pintype "passive"))
      (node (ref "C79") (pin "1") (pinfunction "1_1") (pintype "passive"))
      (node (ref "C80") (pin "P") (pinfunction "P_P") (pintype "passive"))
      (node (ref "C92") (pin "1") (pinfunction "1_1") (pintype "passive"))
      (node (ref "C93") (pin "1") (pinfunction "1_1") (pintype "passive"))
      (node (ref "C94") (pin "1") (pinfunction "1_1") (pintype "passive"))
      (node (ref "C95") (pin "P") (pinfunction "P_P") (pintype "passive"))
      (node (ref "F2") (pin "2") (pinfunction "2_2") (pintype "passive"))
      (node (ref "R99") (pin "2") (pinfunction "2_2") (pintype "passive"))
      (node (ref "U14") (pin "21") (pinfunction "PVDD_C_21") (pintype "bidirectional"))
      (node (ref "U14") (pin "29") (pinfunction "PVDD_B_29") (pintype "bidirectional"))
      (node (ref "U14") (pin "34") (pinfunction "PVDD_A_34") (pintype "bidirectional"))
      (node (ref "U17") (pin "21") (pinfunction "PVDD_C_21") (pintype "bidirectional"))
      (node (ref "U17") (pin "29") (pinfunction "PVDD_B_29") (pintype "bidirectional"))
      (node (ref "U17") (pin "34") (pinfunction "PVDD_A_34") (pintype "bidirectional"))
    )
    (net (code "253") (name "VCC{slash}2") (class "Default")
      (node (ref "C107") (pin "1") (pinfunction "1_1") (pintype "passive"))
      (node (ref "C108") (pin "1") (pinfunction "1_1") (pintype "passive"))
      (node (ref "C109") (pin "1") (pinfunction "1_1") (pintype "passive"))
      (node (ref "C110") (pin "P") (pinfunction "P_P") (pintype "passive"))
      (node (ref "C122") (pin "1") (pinfunction "1_1") (pintype "passive"))
      (node (ref "C123") (pin "1") (pinfunction "1_1") (pintype "passive"))
      (node (ref "C124") (pin "1") (pinfunction "1_1") (pintype "passive"))
      (node (ref "C125") (pin "P") (pinfunction "P_P") (pintype "passive"))
      (node (ref "C158") (pin "1") (pinfunction "1_1") (pintype "passive"))
      (node (ref "C159") (pin "1") (pinfunction "1_1") (pintype "passive"))
      (node (ref "C160") (pin "1") (pinfunction "1_1") (pintype "passive"))
      (node (ref "C161") (pin "P") (pinfunction "P_P") (pintype "passive"))
      (node (ref "F3") (pin "2") (pinfunction "2_2") (pintype "passive"))
      (node (ref "R104") (pin "1") (pinfunction "1_1") (pintype "passive"))
      (node (ref "U20") (pin "21") (pinfunction "PVDD_C_21") (pintype "bidirectional"))
      (node (ref "U20") (pin "29") (pinfunction "PVDD_B_29") (pintype "bidirectional"))
      (node (ref "U20") (pin "34") (pinfunction "PVDD_A_34") (pintype "bidirectional"))
      (node (ref "U23") (pin "21") (pinfunction "PVDD_C_21") (pintype "bidirectional"))
      (node (ref "U23") (pin "29") (pinfunction "PVDD_B_29") (pintype "bidirectional"))
      (node (ref "U23") (pin "34") (pinfunction "PVDD_A_34") (pintype "bidirectional"))
      (node (ref "U37") (pin "21") (pinfunction "PVDD_C_21") (pintype "bidirectional"))
      (node (ref "U37") (pin "29") (pinfunction "PVDD_B_29") (pintype "bidirectional"))
      (node (ref "U37") (pin "34") (pinfunction "PVDD_A_34") (pintype "bidirectional"))
    )
    (net (code "254") (name "VOLT_12V") (class "Default")
      (node (ref "C6") (pin "1") (pinfunction "1_1") (pintype "passive"))
      (node (ref "R123") (pin "2") (pinfunction "2_2") (pintype "passive"))
      (node (ref "U5") (pin "14") (pinfunction "PA08/AD5/PWM1/USART1-RI/SSC-RXCLK_14") (pintype "bidirectional"))
    )
    (net (code "255") (name "VOLT_BAT") (class "Default")
      (node (ref "C5") (pin "1") (pinfunction "1_1") (pintype "passive"))
      (node (ref "R122") (pin "2") (pinfunction "2_2") (pintype "passive"))
      (node (ref "U5") (pin "9") (pinfunction "PA03/AD0/GCLK0/USB_ID/ABDAC-DATA0_9") (pintype "bidirectional"))
    )
    (net (code "256") (name "XBEE_RX") (class "Default")
      (node (ref "CN7") (pin "2") (pinfunction "DOUT_2") (pintype "bidirectional"))
      (node (ref "U9") (pin "118") (pinfunction "IO_L63N_SCP6_0_118") (pintype "bidirectional"))
    )
    (net (code "257") (name "XBEE_TX") (class "Default")
      (node (ref "CN7") (pin "3") (pinfunction "DIN/~{CONFIG}_3") (pintype "bidirectional"))
      (node (ref "U9") (pin "120") (pinfunction "IO_L62N_VREF_0_120") (pintype "bidirectional"))
    )
    (net (code "258") (name "unconnected-(CN3-ID-Pad4)") (class "Default")
      (node (ref "CN3") (pin "4") (pinfunction "ID_4") (pintype "passive"))
    )
    (net (code "259") (name "unconnected-(CN4-ASDO-Pad7)") (class "Default")
      (node (ref "CN4") (pin "7") (pinfunction "ASDO_7") (pintype "bidirectional"))
    )
    (net (code "260") (name "unconnected-(CN4-~{CE}-Pad6)") (class "Default")
      (node (ref "CN4") (pin "6") (pinfunction "~{CE}_6") (pintype "bidirectional"))
    )
    (net (code "261") (name "unconnected-(CN4-~{CS}-Pad8)") (class "Default")
      (node (ref "CN4") (pin "8") (pinfunction "~{CS}_8") (pintype "bidirectional"))
    )
    (net (code "262") (name "unconnected-(CN7-AD1{slash}DIO1-Pad19)") (class "Default")
      (node (ref "CN7") (pin "19") (pinfunction "AD1/DIO1_19") (pintype "bidirectional"))
    )
    (net (code "263") (name "unconnected-(CN7-AD2{slash}DIO2-Pad18)") (class "Default")
      (node (ref "CN7") (pin "18") (pinfunction "AD2/DIO2_18") (pintype "bidirectional"))
    )
    (net (code "264") (name "unconnected-(CN7-AD3{slash}DIO3-Pad17)") (class "Default")
      (node (ref "CN7") (pin "17") (pinfunction "AD3/DIO3_17") (pintype "bidirectional"))
    )
    (net (code "265") (name "unconnected-(CN7-ASSOC{slash}DIO5-Pad15)") (class "Default")
      (node (ref "CN7") (pin "15") (pinfunction "ASSOC/DIO5_15") (pintype "bidirectional"))
    )
    (net (code "266") (name "unconnected-(CN7-COM_BTN{slash}AD0{slash}DIO0-Pad20)") (class "Default")
      (node (ref "CN7") (pin "20") (pinfunction "COM_BTN/AD0/DIO0_20") (pintype "bidirectional"))
    )
    (net (code "267") (name "unconnected-(CN7-DIO4-Pad11)") (class "Default")
      (node (ref "CN7") (pin "11") (pinfunction "DIO4_11") (pintype "bidirectional"))
    )
    (net (code "268") (name "unconnected-(CN7-DIO11-Pad7)") (class "Default")
      (node (ref "CN7") (pin "7") (pinfunction "DIO11_7") (pintype "bidirectional"))
    )
    (net (code "269") (name "unconnected-(CN7-DIO12-Pad4)") (class "Default")
      (node (ref "CN7") (pin "4") (pinfunction "DIO12_4") (pintype "bidirectional"))
    )
    (net (code "270") (name "unconnected-(CN7-ON{slash}~{SLEEP}-Pad13)") (class "Default")
      (node (ref "CN7") (pin "13") (pinfunction "ON/~{SLEEP}_13") (pintype "bidirectional"))
    )
    (net (code "271") (name "unconnected-(CN7-RSSI{slash}PWM{slash}DIO10-Pad6)") (class "Default")
      (node (ref "CN7") (pin "6") (pinfunction "RSSI/PWM/DIO10_6") (pintype "bidirectional"))
    )
    (net (code "272") (name "unconnected-(CN7-RSVD-Pad8)") (class "Default")
      (node (ref "CN7") (pin "8") (pinfunction "RSVD_8") (pintype "bidirectional"))
    )
    (net (code "273") (name "unconnected-(CN7-VREF-Pad14)") (class "Default")
      (node (ref "CN7") (pin "14") (pinfunction "VREF_14") (pintype "bidirectional"))
    )
    (net (code "274") (name "unconnected-(CN7-~{DTR}{slash}SLEEP_RQ{slash}DIO8-Pad9)") (class "Default")
      (node (ref "CN7") (pin "9") (pinfunction "~{DTR}/SLEEP_RQ/DIO8_9") (pintype "bidirectional"))
    )
    (net (code "275") (name "unconnected-(CN7-~{RTS}{slash}DIO6-Pad16)") (class "Default")
      (node (ref "CN7") (pin "16") (pinfunction "~{RTS}/DIO6_16") (pintype "bidirectional"))
    )
    (net (code "276") (name "unconnected-(SW2-PadB1)") (class "Default")
      (node (ref "SW2") (pin "B1") (pinfunction "B1_B1") (pintype "passive"))
    )
    (net (code "277") (name "unconnected-(SW3-PadB1)") (class "Default")
      (node (ref "SW3") (pin "B1") (pinfunction "B1_B1") (pintype "passive"))
    )
    (net (code "278") (name "unconnected-(U2-PG-Pad23)") (class "Default")
      (node (ref "U2") (pin "23") (pinfunction "PG_23") (pintype "bidirectional"))
    )
    (net (code "279") (name "unconnected-(U5-PA09{slash}SCL{slash}SPI0-NPCS2{slash}USART1-CTS-Pad28)") (class "Default")
      (node (ref "U5") (pin "28") (pinfunction "PA09/SCL/SPI0-NPCS2/USART1-CTS_28") (pintype "bidirectional"))
    )
    (net (code "280") (name "unconnected-(U5-PA10{slash}SDA{slash}SPI0-NPCS3{slash}USART1-RTS-Pad29)") (class "Default")
      (node (ref "U5") (pin "29") (pinfunction "PA10/SDA/SPI0-NPCS3/USART1-RTS_29") (pintype "bidirectional"))
    )
    (net (code "281") (name "unconnected-(U5-PA21{slash}TC-A1{slash}PWM2{slash}USART2-TXD{slash}SSC-TXFRM-Pad45)") (class "Default")
      (node (ref "U5") (pin "45") (pinfunction "PA21/TC-A1/PWM2/USART2-TXD/SSC-TXFRM_45") (pintype "bidirectional"))
    )
    (net (code "282") (name "unconnected-(U5-PA22{slash}TC-B1{slash}PWM6{slash}TRIGGER{slash}ABDAC-DATA0-Pad46)") (class "Default")
      (node (ref "U5") (pin "46") (pinfunction "PA22/TC-B1/PWM6/TRIGGER/ABDAC-DATA0_46") (pintype "bidirectional"))
    )
    (net (code "283") (name "unconnected-(U5-PA23{slash}INT3{slash}USART1-TXD{slash}SPI0-NPCS1{slash}PWM0-Pad47)") (class "Default")
      (node (ref "U5") (pin "47") (pinfunction "PA23/INT3/USART1-TXD/SPI0-NPCS1/PWM0_47") (pintype "bidirectional"))
    )
    (net (code "284") (name "unconnected-(U5-PA24{slash}INT4{slash}USART1-RXD{slash}SPI0-NPCS0{slash}PWM1-Pad59)") (class "Default")
      (node (ref "U5") (pin "59") (pinfunction "PA24/INT4/USART1-RXD/SPI0-NPCS0/PWM1_59") (pintype "bidirectional"))
    )
    (net (code "285") (name "unconnected-(U5-PA25{slash}INT5{slash}PWM3{slash}SPI0-MISO-Pad60)") (class "Default")
      (node (ref "U5") (pin "60") (pinfunction "PA25/INT5/PWM3/SPI0-MISO_60") (pintype "bidirectional"))
    )
    (net (code "286") (name "unconnected-(U5-PA29{slash}XOUT1{slash}TC-CLK0{slash}TC-CLK1{slash}SPI0-MOSI-Pad42)") (class "Default")
      (node (ref "U5") (pin "42") (pinfunction "PA29/XOUT1/TC-CLK0/TC-CLK1/SPI0-MOSI_42") (pintype "bidirectional"))
    )
    (net (code "287") (name "unconnected-(U5-PB08{slash}SSC-RXFRM{slash}USART1-DTR{slash}ABDAC-DATA1-Pad54)") (class "Default")
      (node (ref "U5") (pin "54") (pinfunction "PB08/SSC-RXFRM/USART1-DTR/ABDAC-DATA1_54") (pintype "bidirectional"))
    )
    (net (code "288") (name "unconnected-(U7-NC{slash}SIO3-Pad7)") (class "Default")
      (node (ref "U7") (pin "7") (pinfunction "NC/SIO3_7") (pintype "bidirectional"))
    )
    (net (code "289") (name "unconnected-(U9A-IO_L12N_D2_MISO3_2-Pad61)") (class "Default")
      (node (ref "U9") (pin "61") (pinfunction "IO_L12N_D2_MISO3_2_61") (pintype "bidirectional"))
    )
    (net (code "290") (name "unconnected-(U9A-IO_L12P_D1_MISO2_2-Pad62)") (class "Default")
      (node (ref "U9") (pin "62") (pinfunction "IO_L12P_D1_MISO2_2_62") (pintype "bidirectional"))
    )
    (net (code "291") (name "unconnected-(U9A-IO_L13N_D10_2-Pad59)") (class "Default")
      (node (ref "U9") (pin "59") (pinfunction "IO_L13N_D10_2_59") (pintype "bidirectional"))
    )
    (net (code "292") (name "unconnected-(U9A-IO_L13P_M1_2-Pad60)") (class "Default")
      (node (ref "U9") (pin "60") (pinfunction "IO_L13P_M1_2_60") (pintype "bidirectional"))
    )
    (net (code "293") (name "unconnected-(U9A-IO_L14N_D12_2-Pad57)") (class "Default")
      (node (ref "U9") (pin "57") (pinfunction "IO_L14N_D12_2_57") (pintype "bidirectional"))
    )
    (net (code "294") (name "unconnected-(U9A-IO_L14P_D11_2-Pad58)") (class "Default")
      (node (ref "U9") (pin "58") (pinfunction "IO_L14P_D11_2_58") (pintype "bidirectional"))
    )
    (net (code "295") (name "unconnected-(U9A-IO_L30N_GCLK0_USERCCLK_2-Pad55)") (class "Default")
      (node (ref "U9") (pin "55") (pinfunction "IO_L30N_GCLK0_USERCCLK_2_55") (pintype "bidirectional"))
    )
    (net (code "296") (name "unconnected-(U9A-IO_L31P_GCLK31_D14_2-Pad51)") (class "Default")
      (node (ref "U9") (pin "51") (pinfunction "IO_L31P_GCLK31_D14_2_51") (pintype "bidirectional"))
    )
    (net (code "297") (name "unconnected-(U9A-IO_L48N_RDWR_B_VREF_2-Pad47)") (class "Default")
      (node (ref "U9") (pin "47") (pinfunction "IO_L48N_RDWR_B_VREF_2_47") (pintype "bidirectional"))
    )
    (net (code "298") (name "unconnected-(U9A-IO_L49N_D4_2-Pad45)") (class "Default")
      (node (ref "U9") (pin "45") (pinfunction "IO_L49N_D4_2_45") (pintype "bidirectional"))
    )
    (net (code "299") (name "unconnected-(U9A-IO_L49P_D3_2-Pad46)") (class "Default")
      (node (ref "U9") (pin "46") (pinfunction "IO_L49P_D3_2_46") (pintype "bidirectional"))
    )
    (net (code "300") (name "unconnected-(U9A-IO_L62N_D6_2-Pad43)") (class "Default")
      (node (ref "U9") (pin "43") (pinfunction "IO_L62N_D6_2_43") (pintype "bidirectional"))
    )
    (net (code "301") (name "unconnected-(U9A-IO_L62P_D5_2-Pad44)") (class "Default")
      (node (ref "U9") (pin "44") (pinfunction "IO_L62P_D5_2_44") (pintype "bidirectional"))
    )
    (net (code "302") (name "unconnected-(U9A-IO_L64P_D8_2-Pad41)") (class "Default")
      (node (ref "U9") (pin "41") (pinfunction "IO_L64P_D8_2_41") (pintype "bidirectional"))
    )
    (net (code "303") (name "unconnected-(U9A-IO_L65N_CSO_B_2-Pad38)") (class "Default")
      (node (ref "U9") (pin "38") (pinfunction "IO_L65N_CSO_B_2_38") (pintype "bidirectional"))
    )
    (net (code "304") (name "unconnected-(U9B-IO_L1P_3-Pad35)") (class "Default")
      (node (ref "U9") (pin "35") (pinfunction "IO_L1P_3_35") (pintype "bidirectional"))
    )
    (net (code "305") (name "unconnected-(U9B-IO_L43N_GCLK22_IRDY2_3-Pad16)") (class "Default")
      (node (ref "U9") (pin "16") (pinfunction "IO_L43N_GCLK22_IRDY2_3_16") (pintype "bidirectional"))
    )
    (net (code "306") (name "unconnected-(U9B-IO_L43P_GCLK23_3-Pad17)") (class "Default")
      (node (ref "U9") (pin "17") (pinfunction "IO_L43P_GCLK23_3_17") (pintype "bidirectional"))
    )
    (net (code "307") (name "unconnected-(U9B-IO_L44N_GCLK20_3-Pad14)") (class "Default")
      (node (ref "U9") (pin "14") (pinfunction "IO_L44N_GCLK20_3_14") (pintype "bidirectional"))
    )
    (net (code "308") (name "unconnected-(U9B-IO_L44P_GCLK21_3-Pad15)") (class "Default")
      (node (ref "U9") (pin "15") (pinfunction "IO_L44P_GCLK21_3_15") (pintype "bidirectional"))
    )
    (net (code "309") (name "unconnected-(U9B-IO_L83N_VREF_3-Pad1)") (class "Default")
      (node (ref "U9") (pin "1") (pinfunction "IO_L83N_VREF_3_1") (pintype "bidirectional"))
    )
    (net (code "310") (name "unconnected-(U9D-IO_L41N_GCLK8_1-Pad92)") (class "Default")
      (node (ref "U9") (pin "92") (pinfunction "IO_L41N_GCLK8_1_92") (pintype "bidirectional"))
    )
    (net (code "311") (name "unconnected-(U9D-IO_L42N_GCLK6_TRDY1_1-Pad87)") (class "Default")
      (node (ref "U9") (pin "87") (pinfunction "IO_L42N_GCLK6_TRDY1_1_87") (pintype "bidirectional"))
    )
    (net (code "312") (name "unconnected-(U9D-IO_L42P_GCLK7_1-Pad88)") (class "Default")
      (node (ref "U9") (pin "88") (pinfunction "IO_L42P_GCLK7_1_88") (pintype "bidirectional"))
    )
    (net (code "313") (name "unconnected-(U9D-IO_L43P_GCLK5_1-Pad85)") (class "Default")
      (node (ref "U9") (pin "85") (pinfunction "IO_L43P_GCLK5_1_85") (pintype "bidirectional"))
    )
    (net (code "314") (name "unconnected-(U9E-IO_L1N_VREF_0-Pad143)") (class "Default")
      (node (ref "U9") (pin "143") (pinfunction "IO_L1N_VREF_0_143") (pintype "bidirectional"))
    )
    (net (code "315") (name "unconnected-(U9E-IO_L1P_HSWAPEN_0-Pad144)") (class "Default")
      (node (ref "U9") (pin "144") (pinfunction "IO_L1P_HSWAPEN_0_144") (pintype "bidirectional"))
    )
    (net (code "316") (name "unconnected-(U9E-IO_L66N_SCP0_0-Pad111)") (class "Default")
      (node (ref "U9") (pin "111") (pinfunction "IO_L66N_SCP0_0_111") (pintype "bidirectional"))
    )
    (net (code "317") (name "unconnected-(U26-~{QH}-Pad7)") (class "Default")
      (node (ref "U26") (pin "7") (pinfunction "~{QH}_7") (pintype "bidirectional"))
    )
    (net (code "318") (name "unconnected-(U27-QH-Pad9)") (class "Default")
      (node (ref "U27") (pin "9") (pinfunction "QH_9") (pintype "bidirectional"))
    )
    (net (code "319") (name "unconnected-(U30-~{QH}-Pad7)") (class "Default")
      (node (ref "U30") (pin "7") (pinfunction "~{QH}_7") (pintype "bidirectional"))
    )
    (net (code "320") (name "unconnected-(U31-QH-Pad9)") (class "Default")
      (node (ref "U31") (pin "9") (pinfunction "QH_9") (pintype "bidirectional"))
    )
    (net (code "321") (name "~{FLASH_CS}") (class "Default")
      (node (ref "U5") (pin "37") (pinfunction "PA17/TC-CLK2/SPI0-SCK/SPI0-NPCS1/USART1-RXD_37") (pintype "bidirectional"))
      (node (ref "U7") (pin "1") (pinfunction "~{CS}_1") (pintype "bidirectional"))
    )
    (net (code "322") (name "~{FPGA_CS}") (class "Default")
      (node (ref "U5") (pin "27") (pinfunction "PB05/USART1-RTS/SPI0-NPCS2/PWM5_27") (pintype "bidirectional"))
      (node (ref "U9") (pin "67") (pinfunction "IO_L2P_CMPCLK_2_67") (pintype "bidirectional"))
    )
    (net (code "323") (name "~{FPGA_INIT}") (class "Default")
      (node (ref "U5") (pin "38") (pinfunction "PB06/SSC-RXCLK/USART1-DCD/ABDAC-DATA0_38") (pintype "bidirectional"))
      (node (ref "U9") (pin "39") (pinfunction "IO_L65P_INIT_B_2_39") (pintype "bidirectional"))
    )
    (net (code "324") (name "~{FPGA_PROG}") (class "Default")
      (node (ref "R44") (pin "2") (pinfunction "2_2") (pintype "passive"))
      (node (ref "U5") (pin "36") (pinfunction "PA16/PWM4/TC-CLK1/SPI0-NPCS0_36") (pintype "bidirectional"))
      (node (ref "U8") (pin "1") (pinfunction "A_1") (pintype "bidirectional"))
      (node (ref "U8") (pin "2") (pinfunction "B_2") (pintype "bidirectional"))
    )
    (net (code "325") (name "~{LED3}") (class "Default")
      (node (ref "LED3") (pin "K") (pinfunction "K_K") (pintype "passive"))
      (node (ref "U5") (pin "55") (pinfunction "PB09/SSC-TXCLK/USART1-RI/ABDAC-DATAN1_55") (pintype "bidirectional"))
    )
    (net (code "326") (name "~{MCU_RESET}") (class "Default")
      (node (ref "R36") (pin "1") (pinfunction "1_1") (pintype "passive"))
      (node (ref "SW2") (pin "B2") (pinfunction "B2_B2") (pintype "passive"))
      (node (ref "U5") (pin "63") (pinfunction "~{RESET}_63") (pintype "bidirectional"))
    )
    (net (code "327") (name "~{MOT1_2_DO}") (class "Default")
      (node (ref "U27") (pin "7") (pinfunction "~{QH}_7") (pintype "bidirectional"))
      (node (ref "U9") (pin "93") (pinfunction "IO_L41P_GCLK9_IRDY1_1_93") (pintype "bidirectional"))
    )
    (net (code "328") (name "~{MOT1_2_LATCH}") (class "Default")
      (node (ref "U26") (pin "1") (pinfunction "S/~{L}_1") (pintype "bidirectional"))
      (node (ref "U27") (pin "1") (pinfunction "S/~{L}_1") (pintype "bidirectional"))
      (node (ref "U9") (pin "95") (pinfunction "IO_L40P_GCLK11_1_95") (pintype "bidirectional"))
    )
    (net (code "329") (name "~{MOT1_FAULT}") (class "Default")
      (node (ref "RA2") (pin "B1") (pinfunction "1_B1") (pintype "passive"))
      (node (ref "U9") (pin "104") (pinfunction "IO_L1N__VREF_1_104") (pintype "bidirectional"))
    )
    (net (code "330") (name "~{MOT1_HU_5}") (class "Default")
      (node (ref "CN9") (pin "1.3") (pinfunction "HU_1.3") (pintype "bidirectional"))
      (node (ref "CN9") (pin "2.2") (pinfunction "HU_2.2") (pintype "bidirectional"))
      (node (ref "R80") (pin "2") (pinfunction "2_2") (pintype "passive"))
      (node (ref "U26") (pin "5") (pinfunction "G_5") (pintype "bidirectional"))
    )
    (net (code "331") (name "~{MOT1_HV_5}") (class "Default")
      (node (ref "CN9") (pin "1.4") (pinfunction "HV_1.4") (pintype "bidirectional"))
      (node (ref "CN9") (pin "2.3") (pinfunction "HV_2.3") (pintype "bidirectional"))
      (node (ref "R81") (pin "2") (pinfunction "2_2") (pintype "passive"))
      (node (ref "U26") (pin "6") (pinfunction "H_6") (pintype "bidirectional"))
    )
    (net (code "332") (name "~{MOT1_HW_5}") (class "Default")
      (node (ref "CN9") (pin "1.2") (pinfunction "HW_1.2") (pintype "bidirectional"))
      (node (ref "CN9") (pin "2.4") (pinfunction "HW_2.4") (pintype "bidirectional"))
      (node (ref "R82") (pin "2") (pinfunction "2_2") (pintype "passive"))
      (node (ref "U26") (pin "4") (pinfunction "F_4") (pintype "bidirectional"))
    )
    (net (code "333") (name "~{MOT1_OTW}") (class "Default")
      (node (ref "RA2") (pin "A1") (pinfunction "1_A1") (pintype "passive"))
      (node (ref "U9") (pin "105") (pinfunction "IO_L1P_1_105") (pintype "bidirectional"))
    )
    (net (code "334") (name "~{MOT1_RESET_A}") (class "Default")
      (node (ref "RA2") (pin "D1") (pinfunction "1_D1") (pintype "passive"))
      (node (ref "U9") (pin "101") (pinfunction "IO_L32N_1_101") (pintype "bidirectional"))
    )
    (net (code "335") (name "~{MOT1_RESET_B}") (class "Default")
      (node (ref "RA3") (pin "B1") (pinfunction "1_B1") (pintype "passive"))
      (node (ref "U9") (pin "99") (pinfunction "IO_L33N_1_99") (pintype "bidirectional"))
    )
    (net (code "336") (name "~{MOT1_RESET_C}") (class "Default")
      (node (ref "RA3") (pin "C1") (pinfunction "1_C1") (pintype "passive"))
      (node (ref "U9") (pin "98") (pinfunction "IO_L34P_1_98") (pintype "bidirectional"))
    )
    (net (code "337") (name "~{MOT2_FAULT}") (class "Default")
      (node (ref "RA4") (pin "B1") (pinfunction "1_B1") (pintype "passive"))
      (node (ref "U9") (pin "82") (pinfunction "IO_L45N_1_82") (pintype "bidirectional"))
    )
    (net (code "338") (name "~{MOT2_HU_5}") (class "Default")
      (node (ref "CN11") (pin "1.3") (pinfunction "HU_1.3") (pintype "bidirectional"))
      (node (ref "CN11") (pin "2.2") (pinfunction "HU_2.2") (pintype "bidirectional"))
      (node (ref "R85") (pin "2") (pinfunction "2_2") (pintype "passive"))
      (node (ref "U27") (pin "13") (pinfunction "C_13") (pintype "bidirectional"))
    )
    (net (code "339") (name "~{MOT2_HV_5}") (class "Default")
      (node (ref "CN11") (pin "1.4") (pinfunction "HV_1.4") (pintype "bidirectional"))
      (node (ref "CN11") (pin "2.3") (pinfunction "HV_2.3") (pintype "bidirectional"))
      (node (ref "R86") (pin "2") (pinfunction "2_2") (pintype "passive"))
      (node (ref "U27") (pin "12") (pinfunction "B_12") (pintype "bidirectional"))
    )
    (net (code "340") (name "~{MOT2_HW_5}") (class "Default")
      (node (ref "CN11") (pin "1.2") (pinfunction "HW_1.2") (pintype "bidirectional"))
      (node (ref "CN11") (pin "2.4") (pinfunction "HW_2.4") (pintype "bidirectional"))
      (node (ref "R87") (pin "2") (pinfunction "2_2") (pintype "passive"))
      (node (ref "U27") (pin "14") (pinfunction "D_14") (pintype "bidirectional"))
    )
    (net (code "341") (name "~{MOT2_OTW}") (class "Default")
      (node (ref "RA4") (pin "A1") (pinfunction "1_A1") (pintype "passive"))
      (node (ref "U9") (pin "83") (pinfunction "IO_L45P_1_83") (pintype "bidirectional"))
    )
    (net (code "342") (name "~{MOT2_RESET_A}") (class "Default")
      (node (ref "RA4") (pin "D1") (pinfunction "1_D1") (pintype "passive"))
      (node (ref "U9") (pin "80") (pinfunction "IO_L46N_1_80") (pintype "bidirectional"))
    )
    (net (code "343") (name "~{MOT2_RESET_B}") (class "Default")
      (node (ref "RA5") (pin "B1") (pinfunction "1_B1") (pintype "passive"))
      (node (ref "U9") (pin "78") (pinfunction "IO_L47N_1_78") (pintype "bidirectional"))
    )
    (net (code "344") (name "~{MOT2_RESET_C}") (class "Default")
      (node (ref "RA5") (pin "C1") (pinfunction "1_C1") (pintype "passive"))
      (node (ref "U9") (pin "75") (pinfunction "IO_L74P_AWAKE_1_75") (pintype "bidirectional"))
    )
    (net (code "345") (name "~{MOT3_4_5_DO}") (class "Default")
      (node (ref "U31") (pin "7") (pinfunction "~{QH}_7") (pintype "bidirectional"))
      (node (ref "U9") (pin "21") (pinfunction "IO_L42N_GCLK24_3_21") (pintype "bidirectional"))
    )
    (net (code "346") (name "~{MOT3_4_5_LATCH}") (class "Default")
      (node (ref "U30") (pin "1") (pinfunction "S/~{L}_1") (pintype "bidirectional"))
      (node (ref "U31") (pin "1") (pinfunction "S/~{L}_1") (pintype "bidirectional"))
      (node (ref "U9") (pin "23") (pinfunction "IO_L41N_GCLK26_3_23") (pintype "bidirectional"))
    )
    (net (code "347") (name "~{MOT3_FAULT}") (class "Default")
      (node (ref "RA6") (pin "B1") (pinfunction "1_B1") (pintype "passive"))
      (node (ref "U9") (pin "33") (pinfunction "IO_L2P_3_33") (pintype "bidirectional"))
    )
    (net (code "348") (name "~{MOT3_HU_5}") (class "Default")
      (node (ref "CN13") (pin "1.3") (pinfunction "HU_1.3") (pintype "bidirectional"))
      (node (ref "CN13") (pin "2.2") (pinfunction "HU_2.2") (pintype "bidirectional"))
      (node (ref "R90") (pin "2") (pinfunction "2_2") (pintype "passive"))
      (node (ref "U30") (pin "5") (pinfunction "G_5") (pintype "bidirectional"))
    )
    (net (code "349") (name "~{MOT3_HV_5}") (class "Default")
      (node (ref "CN13") (pin "1.4") (pinfunction "HV_1.4") (pintype "bidirectional"))
      (node (ref "CN13") (pin "2.3") (pinfunction "HV_2.3") (pintype "bidirectional"))
      (node (ref "R91") (pin "2") (pinfunction "2_2") (pintype "passive"))
      (node (ref "U30") (pin "6") (pinfunction "H_6") (pintype "bidirectional"))
    )
    (net (code "350") (name "~{MOT3_HW_5}") (class "Default")
      (node (ref "CN13") (pin "1.2") (pinfunction "HW_1.2") (pintype "bidirectional"))
      (node (ref "CN13") (pin "2.4") (pinfunction "HW_2.4") (pintype "bidirectional"))
      (node (ref "R92") (pin "2") (pinfunction "2_2") (pintype "passive"))
      (node (ref "U30") (pin "4") (pinfunction "F_4") (pintype "bidirectional"))
    )
    (net (code "351") (name "~{MOT3_OTW}") (class "Default")
      (node (ref "RA6") (pin "A1") (pinfunction "1_A1") (pintype "passive"))
      (node (ref "U9") (pin "34") (pinfunction "IO_L1N_VREF_3_34") (pintype "bidirectional"))
    )
    (net (code "352") (name "~{MOT3_RESET_A}") (class "Default")
      (node (ref "RA6") (pin "D1") (pinfunction "1_D1") (pintype "passive"))
      (node (ref "U9") (pin "30") (pinfunction "IO_L36P_3_30") (pintype "bidirectional"))
    )
    (net (code "353") (name "~{MOT3_RESET_B}") (class "Default")
      (node (ref "RA7") (pin "B1") (pinfunction "1_B1") (pintype "passive"))
      (node (ref "U9") (pin "27") (pinfunction "IO_L37P_3_27") (pintype "bidirectional"))
    )
    (net (code "354") (name "~{MOT3_RESET_C}") (class "Default")
      (node (ref "RA7") (pin "C1") (pinfunction "1_C1") (pintype "passive"))
      (node (ref "U9") (pin "26") (pinfunction "IO_L37N_3_26") (pintype "bidirectional"))
    )
    (net (code "355") (name "~{MOT4_FAULT}") (class "Default")
      (node (ref "RA8") (pin "B1") (pinfunction "1_B1") (pintype "passive"))
      (node (ref "U9") (pin "10") (pinfunction "IO_L50P_3_10") (pintype "bidirectional"))
    )
    (net (code "356") (name "~{MOT4_HU_5}") (class "Default")
      (node (ref "CN15") (pin "1.3") (pinfunction "HU_1.3") (pintype "bidirectional"))
      (node (ref "CN15") (pin "2.2") (pinfunction "HU_2.2") (pintype "bidirectional"))
      (node (ref "R95") (pin "2") (pinfunction "2_2") (pintype "passive"))
      (node (ref "U31") (pin "12") (pinfunction "B_12") (pintype "bidirectional"))
    )
    (net (code "357") (name "~{MOT4_HV_5}") (class "Default")
      (node (ref "CN15") (pin "1.4") (pinfunction "HV_1.4") (pintype "bidirectional"))
      (node (ref "CN15") (pin "2.3") (pinfunction "HV_2.3") (pintype "bidirectional"))
      (node (ref "R96") (pin "2") (pinfunction "2_2") (pintype "passive"))
      (node (ref "U31") (pin "11") (pinfunction "A_11") (pintype "bidirectional"))
    )
    (net (code "358") (name "~{MOT4_HW_5}") (class "Default")
      (node (ref "CN15") (pin "1.2") (pinfunction "HW_1.2") (pintype "bidirectional"))
      (node (ref "CN15") (pin "2.4") (pinfunction "HW_2.4") (pintype "bidirectional"))
      (node (ref "R97") (pin "2") (pinfunction "2_2") (pintype "passive"))
      (node (ref "U31") (pin "13") (pinfunction "C_13") (pintype "bidirectional"))
    )
    (net (code "359") (name "~{MOT4_OTW}") (class "Default")
      (node (ref "RA8") (pin "A1") (pinfunction "1_A1") (pintype "passive"))
      (node (ref "U9") (pin "11") (pinfunction "IO_L49N_3_11") (pintype "bidirectional"))
    )
    (net (code "360") (name "~{MOT4_RESET_A}") (class "Default")
      (node (ref "RA8") (pin "D1") (pinfunction "1_D1") (pintype "passive"))
      (node (ref "U9") (pin "8") (pinfunction "IO_L51P_3_8") (pintype "bidirectional"))
    )
    (net (code "361") (name "~{MOT4_RESET_B}") (class "Default")
      (node (ref "RA9") (pin "B1") (pinfunction "1_B1") (pintype "passive"))
      (node (ref "U9") (pin "6") (pinfunction "IO_L52P_3_6") (pintype "bidirectional"))
    )
    (net (code "362") (name "~{MOT4_RESET_C}") (class "Default")
      (node (ref "RA9") (pin "C1") (pinfunction "1_C1") (pintype "passive"))
      (node (ref "U9") (pin "5") (pinfunction "IO_L52N_3_5") (pintype "bidirectional"))
    )
    (net (code "363") (name "~{MOT5_FAULT}") (class "Default")
      (node (ref "RA10") (pin "B1") (pinfunction "1_B1") (pintype "passive"))
      (node (ref "U9") (pin "141") (pinfunction "IO_L2N_0_141") (pintype "bidirectional"))
    )
    (net (code "364") (name "~{MOT5_HU_5}") (class "Default")
      (node (ref "CN17") (pin "6") (pinfunction "6_6") (pintype "passive"))
      (node (ref "R119") (pin "1") (pinfunction "1_1") (pintype "passive"))
      (node (ref "U31") (pin "5") (pinfunction "G_5") (pintype "bidirectional"))
    )
    (net (code "365") (name "~{MOT5_HV_5}") (class "Default")
      (node (ref "CN17") (pin "7") (pinfunction "7_7") (pintype "passive"))
      (node (ref "R120") (pin "1") (pinfunction "1_1") (pintype "passive"))
      (node (ref "U31") (pin "6") (pinfunction "H_6") (pintype "bidirectional"))
    )
    (net (code "366") (name "~{MOT5_HW_5}") (class "Default")
      (node (ref "CN17") (pin "8") (pinfunction "8_8") (pintype "passive"))
      (node (ref "R121") (pin "1") (pinfunction "1_1") (pintype "passive"))
      (node (ref "U31") (pin "14") (pinfunction "D_14") (pintype "bidirectional"))
    )
    (net (code "367") (name "~{MOT5_OTW}") (class "Default")
      (node (ref "RA10") (pin "A1") (pinfunction "1_A1") (pintype "passive"))
      (node (ref "U9") (pin "142") (pinfunction "IO_L2P_0_142") (pintype "bidirectional"))
    )
    (net (code "368") (name "~{MOT5_RESET_A}") (class "Default")
      (node (ref "RA10") (pin "D1") (pinfunction "1_D1") (pintype "passive"))
      (node (ref "U9") (pin "139") (pinfunction "IO_L3N_0_139") (pintype "bidirectional"))
    )
    (net (code "369") (name "~{MOT5_RESET_B}") (class "Default")
      (node (ref "RA11") (pin "B1") (pinfunction "1_B1") (pintype "passive"))
      (node (ref "U9") (pin "137") (pinfunction "IO_L4N_0_137") (pintype "bidirectional"))
    )
    (net (code "370") (name "~{MOT5_RESET_C}") (class "Default")
      (node (ref "RA11") (pin "C1") (pinfunction "1_C1") (pintype "passive"))
      (node (ref "U9") (pin "134") (pinfunction "IO_L34P_GCLK19_0_134") (pintype "bidirectional"))
    )
    (net (code "371") (name "~{SETTING_BOOTLOADER}") (class "Default")
      (node (ref "J1") (pin "2") (pinfunction "2_2") (pintype "passive"))
      (node (ref "U5") (pin "10") (pinfunction "PA04/AD1/GCLK1/USB_VBOF/ABDAC-DATAN0_10") (pintype "bidirectional"))
    )
    (net (code "372") (name "~{SETTING_CHARGER}") (class "Default")
      (node (ref "J1") (pin "4") (pinfunction "4_4") (pintype "passive"))
      (node (ref "U5") (pin "7") (pinfunction "PB01/TC-B0/USART2-RTS_7") (pintype "bidirectional"))
    )
    (net (code "373") (name "~{SETTING_ID0}") (class "Default")
      (node (ref "J1") (pin "6") (pinfunction "6_6") (pintype "passive"))
      (node (ref "U5") (pin "11") (pinfunction "PA05/AD2/INT0/USART1-DCD/ABDAC-DATA1_11") (pintype "bidirectional"))
    )
    (net (code "374") (name "~{SETTING_ID1}") (class "Default")
      (node (ref "J1") (pin "8") (pinfunction "8_8") (pintype "passive"))
      (node (ref "U5") (pin "12") (pinfunction "PA06/AD3/INT1/USART1-DSR/ABDAC-DATAN1_12") (pintype "bidirectional"))
    )
    (net (code "375") (name "~{SETTING_ID2}") (class "Default")
      (node (ref "J1") (pin "10") (pinfunction "10_10") (pintype "passive"))
      (node (ref "U5") (pin "13") (pinfunction "PA07/AD4/PWM0/USART1-DTR/SSC-RXFRM_13") (pintype "bidirectional"))
    )
    (net (code "376") (name "~{SW1}") (class "Default")
      (node (ref "SW3") (pin "B2") (pinfunction "B2_B2") (pintype "passive"))
      (node (ref "U5") (pin "16") (pinfunction "PA31/AD7/PWM6_16") (pintype "bidirectional"))
    )
    (net (code "377") (name "~{XBEE_CTS}") (class "Default")
      (node (ref "CN7") (pin "12") (pinfunction "~{CTS}/DIO7_12") (pintype "bidirectional"))
      (node (ref "U9") (pin "115") (pinfunction "IO_L65P_SCP3_0_115") (pintype "bidirectional"))
    )
    (net (code "378") (name "~{XBEE_RST}") (class "Default")
      (node (ref "CN7") (pin "5") (pinfunction "~{RESET}_5") (pintype "bidirectional"))
      (node (ref "R53") (pin "2") (pinfunction "2_2") (pintype "passive"))
      (node (ref "U9") (pin "123") (pinfunction "IO_L37N_GCLK12_0_123") (pintype "bidirectional"))
    )
  )
)
